# haasoscope_pro_fpga_board_-_v1_0.net
KiCad netlist of a schematic drawn in EAGLE
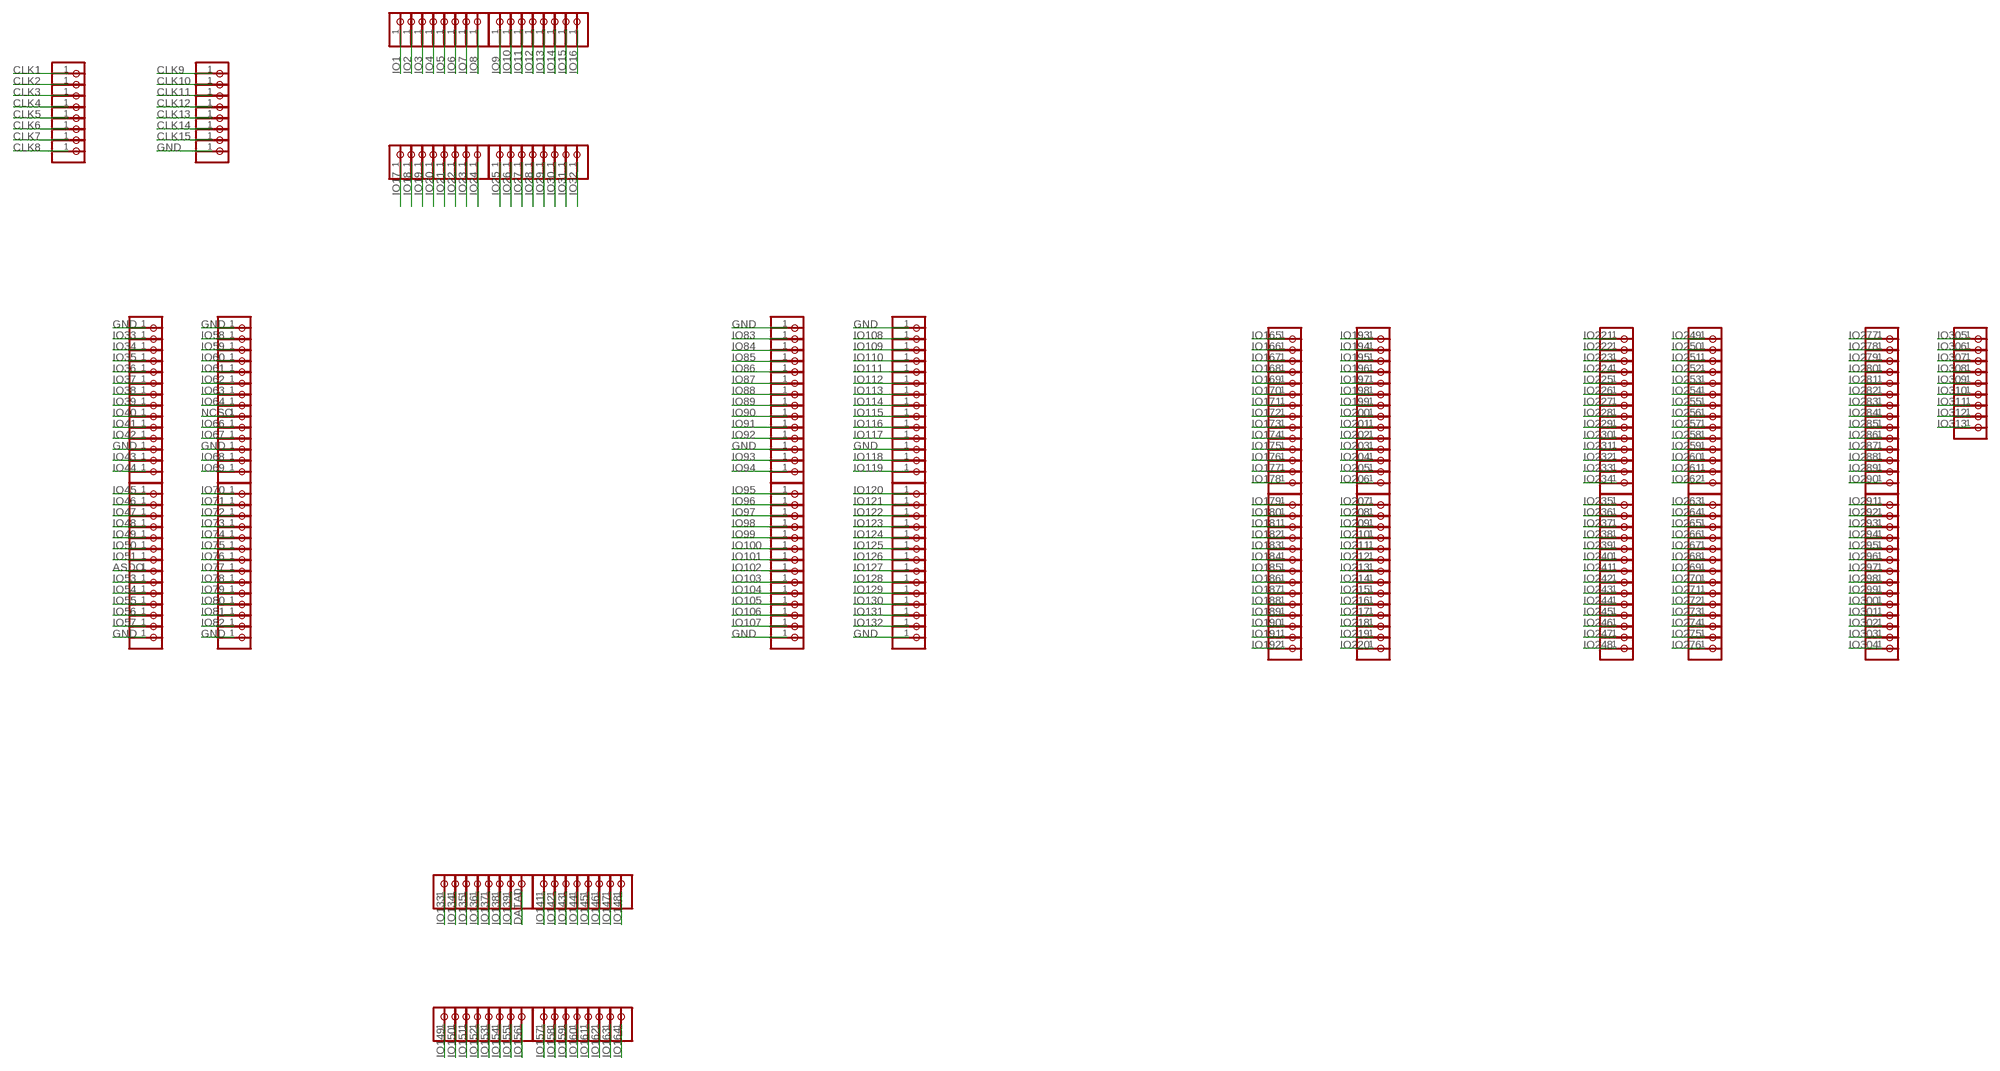
[diagram p0: schematic, sheet 1]
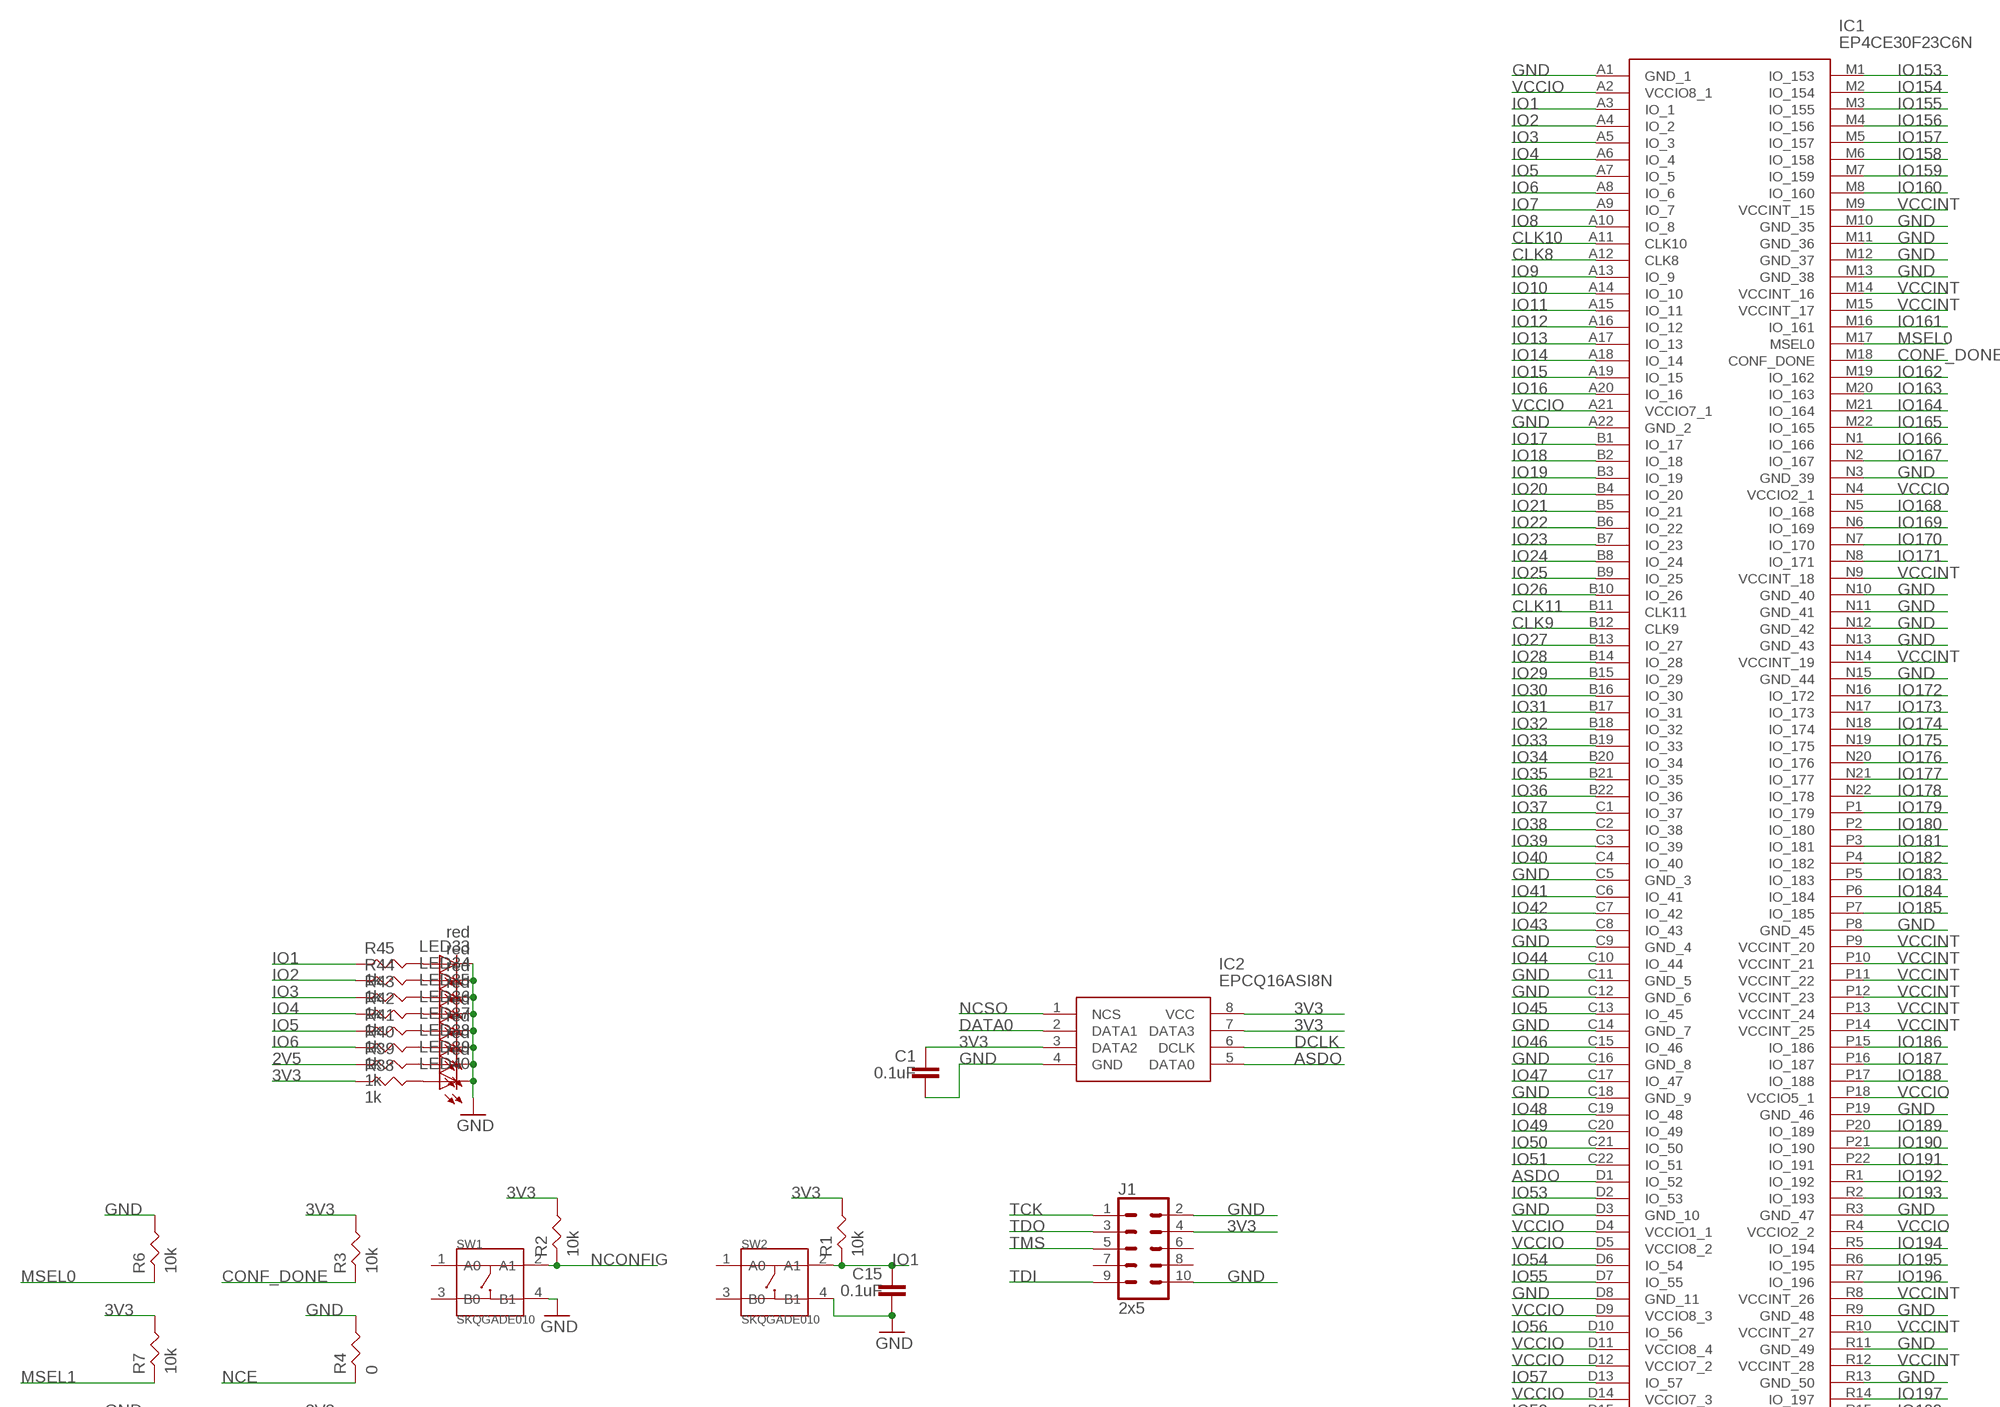
[diagram p1: schematic, sheet 2, part 1 of 2]
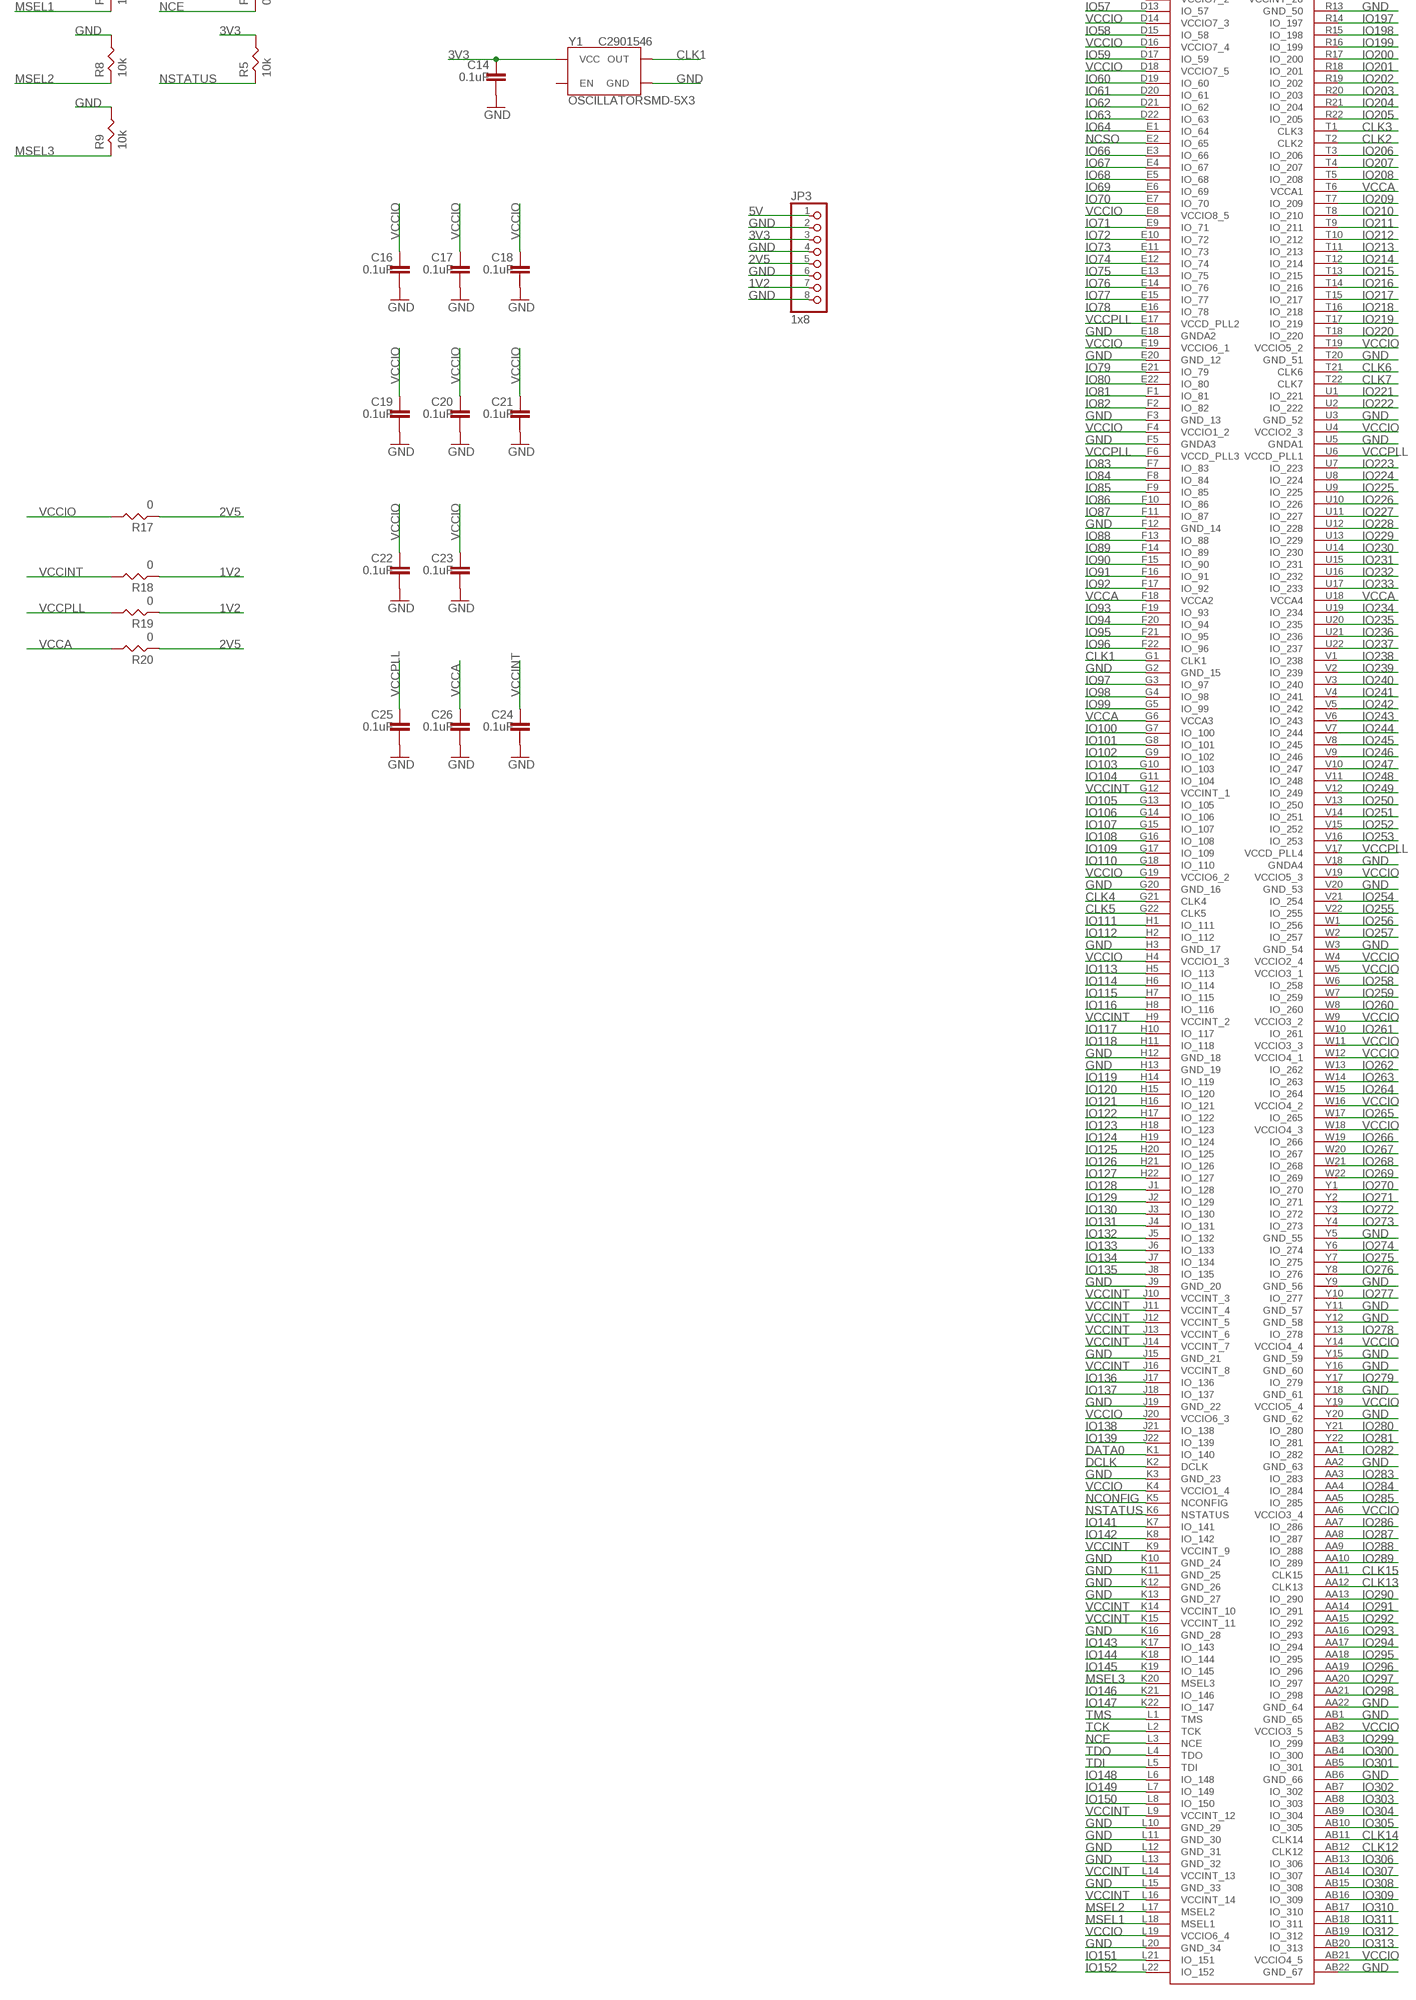
[diagram p2: schematic, sheet 2, part 2 of 2]
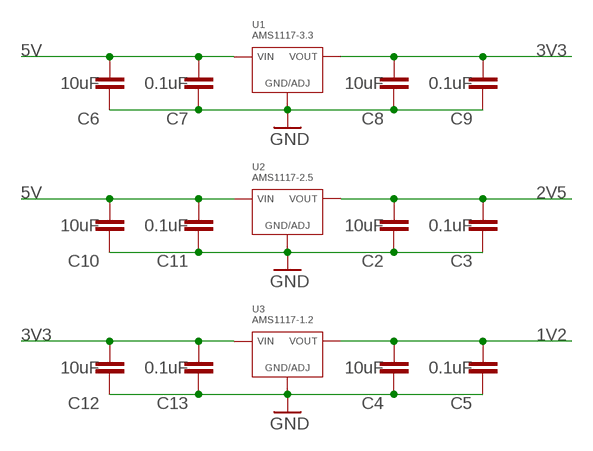
[diagram p3: schematic, sheet 3]

(export (version "E")
  (design (tool "Eeschema 10.0.6"))
  (components
    (comp (ref "JP1")
      (value "1")
      (footprint "eagle-import:1X01")
      (libsource (lib "eagle-import") (part "PINHD-1X1"))
    )
    (comp (ref "JP2")
      (value "1")
      (footprint "eagle-import:1X01")
      (libsource (lib "eagle-import") (part "PINHD-1X1"))
    )
    (comp (ref "JP4")
      (value "1")
      (footprint "eagle-import:1X01")
      (libsource (lib "eagle-import") (part "PINHD-1X1"))
    )
    (comp (ref "JP5")
      (value "1")
      (footprint "eagle-import:1X01")
      (libsource (lib "eagle-import") (part "PINHD-1X1"))
    )
    (comp (ref "JP6")
      (value "1")
      (footprint "eagle-import:1X01")
      (libsource (lib "eagle-import") (part "PINHD-1X1"))
    )
    (comp (ref "JP7")
      (value "1")
      (footprint "eagle-import:1X01")
      (libsource (lib "eagle-import") (part "PINHD-1X1"))
    )
    (comp (ref "JP8")
      (value "1")
      (footprint "eagle-import:1X01")
      (libsource (lib "eagle-import") (part "PINHD-1X1"))
    )
    (comp (ref "JP9")
      (value "1")
      (footprint "eagle-import:1X01")
      (libsource (lib "eagle-import") (part "PINHD-1X1"))
    )
    (comp (ref "JP10")
      (value "1")
      (footprint "eagle-import:1X01")
      (libsource (lib "eagle-import") (part "PINHD-1X1"))
    )
    (comp (ref "JP11")
      (value "1")
      (footprint "eagle-import:1X01")
      (libsource (lib "eagle-import") (part "PINHD-1X1"))
    )
    (comp (ref "JP12")
      (value "1")
      (footprint "eagle-import:1X01")
      (libsource (lib "eagle-import") (part "PINHD-1X1"))
    )
    (comp (ref "JP13")
      (value "1")
      (footprint "eagle-import:1X01")
      (libsource (lib "eagle-import") (part "PINHD-1X1"))
    )
    (comp (ref "JP14")
      (value "1")
      (footprint "eagle-import:1X01")
      (libsource (lib "eagle-import") (part "PINHD-1X1"))
    )
    (comp (ref "JP15")
      (value "1")
      (footprint "eagle-import:1X01")
      (libsource (lib "eagle-import") (part "PINHD-1X1"))
    )
    (comp (ref "JP16")
      (value "1")
      (footprint "eagle-import:1X01")
      (libsource (lib "eagle-import") (part "PINHD-1X1"))
    )
    (comp (ref "JP17")
      (value "1")
      (footprint "eagle-import:1X01")
      (libsource (lib "eagle-import") (part "PINHD-1X1"))
    )
    (comp (ref "JP18")
      (value "1")
      (footprint "eagle-import:1X01")
      (libsource (lib "eagle-import") (part "PINHD-1X1"))
    )
    (comp (ref "JP19")
      (value "1")
      (footprint "eagle-import:1X01")
      (libsource (lib "eagle-import") (part "PINHD-1X1"))
    )
    (comp (ref "JP20")
      (value "1")
      (footprint "eagle-import:1X01")
      (libsource (lib "eagle-import") (part "PINHD-1X1"))
    )
    (comp (ref "JP21")
      (value "1")
      (footprint "eagle-import:1X01")
      (libsource (lib "eagle-import") (part "PINHD-1X1"))
    )
    (comp (ref "JP22")
      (value "1")
      (footprint "eagle-import:1X01")
      (libsource (lib "eagle-import") (part "PINHD-1X1"))
    )
    (comp (ref "JP23")
      (value "1")
      (footprint "eagle-import:1X01")
      (libsource (lib "eagle-import") (part "PINHD-1X1"))
    )
    (comp (ref "JP24")
      (value "1")
      (footprint "eagle-import:1X01")
      (libsource (lib "eagle-import") (part "PINHD-1X1"))
    )
    (comp (ref "JP25")
      (value "1")
      (footprint "eagle-import:1X01")
      (libsource (lib "eagle-import") (part "PINHD-1X1"))
    )
    (comp (ref "JP26")
      (value "1")
      (footprint "eagle-import:1X01")
      (libsource (lib "eagle-import") (part "PINHD-1X1"))
    )
    (comp (ref "JP27")
      (value "1")
      (footprint "eagle-import:1X01")
      (libsource (lib "eagle-import") (part "PINHD-1X1"))
    )
    (comp (ref "JP28")
      (value "1")
      (footprint "eagle-import:1X01")
      (libsource (lib "eagle-import") (part "PINHD-1X1"))
    )
    (comp (ref "JP29")
      (value "1")
      (footprint "eagle-import:1X01")
      (libsource (lib "eagle-import") (part "PINHD-1X1"))
    )
    (comp (ref "JP30")
      (value "1")
      (footprint "eagle-import:1X01")
      (libsource (lib "eagle-import") (part "PINHD-1X1"))
    )
    (comp (ref "JP31")
      (value "1")
      (footprint "eagle-import:1X01")
      (libsource (lib "eagle-import") (part "PINHD-1X1"))
    )
    (comp (ref "JP32")
      (value "1")
      (footprint "eagle-import:1X01")
      (libsource (lib "eagle-import") (part "PINHD-1X1"))
    )
    (comp (ref "JP33")
      (value "1")
      (footprint "eagle-import:1X01")
      (libsource (lib "eagle-import") (part "PINHD-1X1"))
    )
    (comp (ref "JP34")
      (value "1")
      (footprint "eagle-import:1X01")
      (libsource (lib "eagle-import") (part "PINHD-1X1"))
    )
    (comp (ref "JP35")
      (value "1")
      (footprint "eagle-import:1X01")
      (libsource (lib "eagle-import") (part "PINHD-1X1"))
    )
    (comp (ref "JP36")
      (value "1")
      (footprint "eagle-import:1X01")
      (libsource (lib "eagle-import") (part "PINHD-1X1"))
    )
    (comp (ref "JP37")
      (value "1")
      (footprint "eagle-import:1X01")
      (libsource (lib "eagle-import") (part "PINHD-1X1"))
    )
    (comp (ref "JP38")
      (value "1")
      (footprint "eagle-import:1X01")
      (libsource (lib "eagle-import") (part "PINHD-1X1"))
    )
    (comp (ref "JP39")
      (value "1")
      (footprint "eagle-import:1X01")
      (libsource (lib "eagle-import") (part "PINHD-1X1"))
    )
    (comp (ref "JP40")
      (value "1")
      (footprint "eagle-import:1X01")
      (libsource (lib "eagle-import") (part "PINHD-1X1"))
    )
    (comp (ref "JP41")
      (value "1")
      (footprint "eagle-import:1X01")
      (libsource (lib "eagle-import") (part "PINHD-1X1"))
    )
    (comp (ref "JP42")
      (value "1")
      (footprint "eagle-import:1X01")
      (libsource (lib "eagle-import") (part "PINHD-1X1"))
    )
    (comp (ref "JP43")
      (value "1")
      (footprint "eagle-import:1X01")
      (libsource (lib "eagle-import") (part "PINHD-1X1"))
    )
    (comp (ref "JP44")
      (value "1")
      (footprint "eagle-import:1X01")
      (libsource (lib "eagle-import") (part "PINHD-1X1"))
    )
    (comp (ref "JP45")
      (value "1")
      (footprint "eagle-import:1X01")
      (libsource (lib "eagle-import") (part "PINHD-1X1"))
    )
    (comp (ref "JP46")
      (value "1")
      (footprint "eagle-import:1X01")
      (libsource (lib "eagle-import") (part "PINHD-1X1"))
    )
    (comp (ref "JP47")
      (value "1")
      (footprint "eagle-import:1X01")
      (libsource (lib "eagle-import") (part "PINHD-1X1"))
    )
    (comp (ref "JP48")
      (value "1")
      (footprint "eagle-import:1X01")
      (libsource (lib "eagle-import") (part "PINHD-1X1"))
    )
    (comp (ref "JP49")
      (value "1")
      (footprint "eagle-import:1X01")
      (libsource (lib "eagle-import") (part "PINHD-1X1"))
    )
    (comp (ref "JP50")
      (value "1")
      (footprint "eagle-import:1X01")
      (libsource (lib "eagle-import") (part "PINHD-1X1"))
    )
    (comp (ref "JP51")
      (value "1")
      (footprint "eagle-import:1X01")
      (libsource (lib "eagle-import") (part "PINHD-1X1"))
    )
    (comp (ref "JP52")
      (value "1")
      (footprint "eagle-import:1X01")
      (libsource (lib "eagle-import") (part "PINHD-1X1"))
    )
    (comp (ref "JP53")
      (value "1")
      (footprint "eagle-import:1X01")
      (libsource (lib "eagle-import") (part "PINHD-1X1"))
    )
    (comp (ref "JP54")
      (value "1")
      (footprint "eagle-import:1X01")
      (libsource (lib "eagle-import") (part "PINHD-1X1"))
    )
    (comp (ref "JP55")
      (value "1")
      (footprint "eagle-import:1X01")
      (libsource (lib "eagle-import") (part "PINHD-1X1"))
    )
    (comp (ref "JP56")
      (value "1")
      (footprint "eagle-import:1X01")
      (libsource (lib "eagle-import") (part "PINHD-1X1"))
    )
    (comp (ref "JP57")
      (value "1")
      (footprint "eagle-import:1X01")
      (libsource (lib "eagle-import") (part "PINHD-1X1"))
    )
    (comp (ref "JP58")
      (value "1")
      (footprint "eagle-import:1X01")
      (libsource (lib "eagle-import") (part "PINHD-1X1"))
    )
    (comp (ref "JP59")
      (value "1")
      (footprint "eagle-import:1X01")
      (libsource (lib "eagle-import") (part "PINHD-1X1"))
    )
    (comp (ref "JP60")
      (value "1")
      (footprint "eagle-import:1X01")
      (libsource (lib "eagle-import") (part "PINHD-1X1"))
    )
    (comp (ref "JP61")
      (value "1")
      (footprint "eagle-import:1X01")
      (libsource (lib "eagle-import") (part "PINHD-1X1"))
    )
    (comp (ref "JP62")
      (value "1")
      (footprint "eagle-import:1X01")
      (libsource (lib "eagle-import") (part "PINHD-1X1"))
    )
    (comp (ref "JP63")
      (value "1")
      (footprint "eagle-import:1X01")
      (libsource (lib "eagle-import") (part "PINHD-1X1"))
    )
    (comp (ref "JP64")
      (value "1")
      (footprint "eagle-import:1X01")
      (libsource (lib "eagle-import") (part "PINHD-1X1"))
    )
    (comp (ref "JP65")
      (value "1")
      (footprint "eagle-import:1X01")
      (libsource (lib "eagle-import") (part "PINHD-1X1"))
    )
    (comp (ref "JP66")
      (value "1")
      (footprint "eagle-import:1X01")
      (libsource (lib "eagle-import") (part "PINHD-1X1"))
    )
    (comp (ref "JP67")
      (value "1")
      (footprint "eagle-import:1X01")
      (libsource (lib "eagle-import") (part "PINHD-1X1"))
    )
    (comp (ref "JP68")
      (value "1")
      (footprint "eagle-import:1X01")
      (libsource (lib "eagle-import") (part "PINHD-1X1"))
    )
    (comp (ref "JP69")
      (value "1")
      (footprint "eagle-import:1X01")
      (libsource (lib "eagle-import") (part "PINHD-1X1"))
    )
    (comp (ref "JP70")
      (value "1")
      (footprint "eagle-import:1X01")
      (libsource (lib "eagle-import") (part "PINHD-1X1"))
    )
    (comp (ref "JP71")
      (value "1")
      (footprint "eagle-import:1X01")
      (libsource (lib "eagle-import") (part "PINHD-1X1"))
    )
    (comp (ref "JP72")
      (value "1")
      (footprint "eagle-import:1X01")
      (libsource (lib "eagle-import") (part "PINHD-1X1"))
    )
    (comp (ref "JP73")
      (value "1")
      (footprint "eagle-import:1X01")
      (libsource (lib "eagle-import") (part "PINHD-1X1"))
    )
    (comp (ref "JP74")
      (value "1")
      (footprint "eagle-import:1X01")
      (libsource (lib "eagle-import") (part "PINHD-1X1"))
    )
    (comp (ref "JP75")
      (value "1")
      (footprint "eagle-import:1X01")
      (libsource (lib "eagle-import") (part "PINHD-1X1"))
    )
    (comp (ref "JP76")
      (value "1")
      (footprint "eagle-import:1X01")
      (libsource (lib "eagle-import") (part "PINHD-1X1"))
    )
    (comp (ref "JP77")
      (value "1")
      (footprint "eagle-import:1X01")
      (libsource (lib "eagle-import") (part "PINHD-1X1"))
    )
    (comp (ref "JP78")
      (value "1")
      (footprint "eagle-import:1X01")
      (libsource (lib "eagle-import") (part "PINHD-1X1"))
    )
    (comp (ref "JP79")
      (value "1")
      (footprint "eagle-import:1X01")
      (libsource (lib "eagle-import") (part "PINHD-1X1"))
    )
    (comp (ref "JP80")
      (value "1")
      (footprint "eagle-import:1X01")
      (libsource (lib "eagle-import") (part "PINHD-1X1"))
    )
    (comp (ref "JP81")
      (value "1")
      (footprint "eagle-import:1X01")
      (libsource (lib "eagle-import") (part "PINHD-1X1"))
    )
    (comp (ref "JP82")
      (value "1")
      (footprint "eagle-import:1X01")
      (libsource (lib "eagle-import") (part "PINHD-1X1"))
    )
    (comp (ref "JP83")
      (value "1")
      (footprint "eagle-import:1X01")
      (libsource (lib "eagle-import") (part "PINHD-1X1"))
    )
    (comp (ref "JP84")
      (value "1")
      (footprint "eagle-import:1X01")
      (libsource (lib "eagle-import") (part "PINHD-1X1"))
    )
    (comp (ref "JP85")
      (value "1")
      (footprint "eagle-import:1X01")
      (libsource (lib "eagle-import") (part "PINHD-1X1"))
    )
    (comp (ref "JP86")
      (value "1")
      (footprint "eagle-import:1X01")
      (libsource (lib "eagle-import") (part "PINHD-1X1"))
    )
    (comp (ref "JP87")
      (value "1")
      (footprint "eagle-import:1X01")
      (libsource (lib "eagle-import") (part "PINHD-1X1"))
    )
    (comp (ref "JP88")
      (value "1")
      (footprint "eagle-import:1X01")
      (libsource (lib "eagle-import") (part "PINHD-1X1"))
    )
    (comp (ref "JP89")
      (value "1")
      (footprint "eagle-import:1X01")
      (libsource (lib "eagle-import") (part "PINHD-1X1"))
    )
    (comp (ref "JP90")
      (value "1")
      (footprint "eagle-import:1X01")
      (libsource (lib "eagle-import") (part "PINHD-1X1"))
    )
    (comp (ref "JP91")
      (value "1")
      (footprint "eagle-import:1X01")
      (libsource (lib "eagle-import") (part "PINHD-1X1"))
    )
    (comp (ref "JP92")
      (value "1")
      (footprint "eagle-import:1X01")
      (libsource (lib "eagle-import") (part "PINHD-1X1"))
    )
    (comp (ref "JP93")
      (value "1")
      (footprint "eagle-import:1X01")
      (libsource (lib "eagle-import") (part "PINHD-1X1"))
    )
    (comp (ref "JP94")
      (value "1")
      (footprint "eagle-import:1X01")
      (libsource (lib "eagle-import") (part "PINHD-1X1"))
    )
    (comp (ref "JP95")
      (value "1")
      (footprint "eagle-import:1X01")
      (libsource (lib "eagle-import") (part "PINHD-1X1"))
    )
    (comp (ref "JP96")
      (value "1")
      (footprint "eagle-import:1X01")
      (libsource (lib "eagle-import") (part "PINHD-1X1"))
    )
    (comp (ref "JP97")
      (value "1")
      (footprint "eagle-import:1X01")
      (libsource (lib "eagle-import") (part "PINHD-1X1"))
    )
    (comp (ref "JP98")
      (value "1")
      (footprint "eagle-import:1X01")
      (libsource (lib "eagle-import") (part "PINHD-1X1"))
    )
    (comp (ref "JP99")
      (value "1")
      (footprint "eagle-import:1X01")
      (libsource (lib "eagle-import") (part "PINHD-1X1"))
    )
    (comp (ref "JP100")
      (value "1")
      (footprint "eagle-import:1X01")
      (libsource (lib "eagle-import") (part "PINHD-1X1"))
    )
    (comp (ref "JP101")
      (value "1")
      (footprint "eagle-import:1X01")
      (libsource (lib "eagle-import") (part "PINHD-1X1"))
    )
    (comp (ref "JP102")
      (value "1")
      (footprint "eagle-import:1X01")
      (libsource (lib "eagle-import") (part "PINHD-1X1"))
    )
    (comp (ref "JP103")
      (value "1")
      (footprint "eagle-import:1X01")
      (libsource (lib "eagle-import") (part "PINHD-1X1"))
    )
    (comp (ref "JP104")
      (value "1")
      (footprint "eagle-import:1X01")
      (libsource (lib "eagle-import") (part "PINHD-1X1"))
    )
    (comp (ref "JP105")
      (value "1")
      (footprint "eagle-import:1X01")
      (libsource (lib "eagle-import") (part "PINHD-1X1"))
    )
    (comp (ref "JP106")
      (value "1")
      (footprint "eagle-import:1X01")
      (libsource (lib "eagle-import") (part "PINHD-1X1"))
    )
    (comp (ref "JP107")
      (value "1")
      (footprint "eagle-import:1X01")
      (libsource (lib "eagle-import") (part "PINHD-1X1"))
    )
    (comp (ref "JP108")
      (value "1")
      (footprint "eagle-import:1X01")
      (libsource (lib "eagle-import") (part "PINHD-1X1"))
    )
    (comp (ref "JP109")
      (value "1")
      (footprint "eagle-import:1X01")
      (libsource (lib "eagle-import") (part "PINHD-1X1"))
    )
    (comp (ref "JP110")
      (value "1")
      (footprint "eagle-import:1X01")
      (libsource (lib "eagle-import") (part "PINHD-1X1"))
    )
    (comp (ref "JP111")
      (value "1")
      (footprint "eagle-import:1X01")
      (libsource (lib "eagle-import") (part "PINHD-1X1"))
    )
    (comp (ref "JP112")
      (value "1")
      (footprint "eagle-import:1X01")
      (libsource (lib "eagle-import") (part "PINHD-1X1"))
    )
    (comp (ref "JP113")
      (value "1")
      (footprint "eagle-import:1X01")
      (libsource (lib "eagle-import") (part "PINHD-1X1"))
    )
    (comp (ref "JP114")
      (value "1")
      (footprint "eagle-import:1X01")
      (libsource (lib "eagle-import") (part "PINHD-1X1"))
    )
    (comp (ref "JP115")
      (value "1")
      (footprint "eagle-import:1X01")
      (libsource (lib "eagle-import") (part "PINHD-1X1"))
    )
    (comp (ref "JP116")
      (value "1")
      (footprint "eagle-import:1X01")
      (libsource (lib "eagle-import") (part "PINHD-1X1"))
    )
    (comp (ref "JP117")
      (value "1")
      (footprint "eagle-import:1X01")
      (libsource (lib "eagle-import") (part "PINHD-1X1"))
    )
    (comp (ref "JP118")
      (value "1")
      (footprint "eagle-import:1X01")
      (libsource (lib "eagle-import") (part "PINHD-1X1"))
    )
    (comp (ref "JP119")
      (value "1")
      (footprint "eagle-import:1X01")
      (libsource (lib "eagle-import") (part "PINHD-1X1"))
    )
    (comp (ref "JP120")
      (value "1")
      (footprint "eagle-import:1X01")
      (libsource (lib "eagle-import") (part "PINHD-1X1"))
    )
    (comp (ref "JP121")
      (value "1")
      (footprint "eagle-import:1X01")
      (libsource (lib "eagle-import") (part "PINHD-1X1"))
    )
    (comp (ref "JP122")
      (value "1")
      (footprint "eagle-import:1X01")
      (libsource (lib "eagle-import") (part "PINHD-1X1"))
    )
    (comp (ref "JP123")
      (value "1")
      (footprint "eagle-import:1X01")
      (libsource (lib "eagle-import") (part "PINHD-1X1"))
    )
    (comp (ref "JP124")
      (value "1")
      (footprint "eagle-import:1X01")
      (libsource (lib "eagle-import") (part "PINHD-1X1"))
    )
    (comp (ref "JP125")
      (value "1")
      (footprint "eagle-import:1X01")
      (libsource (lib "eagle-import") (part "PINHD-1X1"))
    )
    (comp (ref "JP126")
      (value "1")
      (footprint "eagle-import:1X01")
      (libsource (lib "eagle-import") (part "PINHD-1X1"))
    )
    (comp (ref "JP127")
      (value "1")
      (footprint "eagle-import:1X01")
      (libsource (lib "eagle-import") (part "PINHD-1X1"))
    )
    (comp (ref "JP128")
      (value "1")
      (footprint "eagle-import:1X01")
      (libsource (lib "eagle-import") (part "PINHD-1X1"))
    )
    (comp (ref "JP129")
      (value "1")
      (footprint "eagle-import:1X01")
      (libsource (lib "eagle-import") (part "PINHD-1X1"))
    )
    (comp (ref "JP130")
      (value "1")
      (footprint "eagle-import:1X01")
      (libsource (lib "eagle-import") (part "PINHD-1X1"))
    )
    (comp (ref "JP131")
      (value "1")
      (footprint "eagle-import:1X01")
      (libsource (lib "eagle-import") (part "PINHD-1X1"))
    )
    (comp (ref "JP132")
      (value "1")
      (footprint "eagle-import:1X01")
      (libsource (lib "eagle-import") (part "PINHD-1X1"))
    )
    (comp (ref "JP133")
      (value "1")
      (footprint "eagle-import:1X01")
      (libsource (lib "eagle-import") (part "PINHD-1X1"))
    )
    (comp (ref "JP134")
      (value "1")
      (footprint "eagle-import:1X01")
      (libsource (lib "eagle-import") (part "PINHD-1X1"))
    )
    (comp (ref "JP135")
      (value "1")
      (footprint "eagle-import:1X01")
      (libsource (lib "eagle-import") (part "PINHD-1X1"))
    )
    (comp (ref "JP136")
      (value "1")
      (footprint "eagle-import:1X01")
      (libsource (lib "eagle-import") (part "PINHD-1X1"))
    )
    (comp (ref "JP137")
      (value "1")
      (footprint "eagle-import:1X01")
      (libsource (lib "eagle-import") (part "PINHD-1X1"))
    )
    (comp (ref "JP138")
      (value "1")
      (footprint "eagle-import:1X01")
      (libsource (lib "eagle-import") (part "PINHD-1X1"))
    )
    (comp (ref "JP139")
      (value "1")
      (footprint "eagle-import:1X01")
      (libsource (lib "eagle-import") (part "PINHD-1X1"))
    )
    (comp (ref "JP140")
      (value "1")
      (footprint "eagle-import:1X01")
      (libsource (lib "eagle-import") (part "PINHD-1X1"))
    )
    (comp (ref "JP141")
      (value "1")
      (footprint "eagle-import:1X01")
      (libsource (lib "eagle-import") (part "PINHD-1X1"))
    )
    (comp (ref "JP142")
      (value "1")
      (footprint "eagle-import:1X01")
      (libsource (lib "eagle-import") (part "PINHD-1X1"))
    )
    (comp (ref "JP143")
      (value "1")
      (footprint "eagle-import:1X01")
      (libsource (lib "eagle-import") (part "PINHD-1X1"))
    )
    (comp (ref "JP144")
      (value "1")
      (footprint "eagle-import:1X01")
      (libsource (lib "eagle-import") (part "PINHD-1X1"))
    )
    (comp (ref "JP145")
      (value "1")
      (footprint "eagle-import:1X01")
      (libsource (lib "eagle-import") (part "PINHD-1X1"))
    )
    (comp (ref "JP146")
      (value "1")
      (footprint "eagle-import:1X01")
      (libsource (lib "eagle-import") (part "PINHD-1X1"))
    )
    (comp (ref "JP147")
      (value "1")
      (footprint "eagle-import:1X01")
      (libsource (lib "eagle-import") (part "PINHD-1X1"))
    )
    (comp (ref "JP148")
      (value "1")
      (footprint "eagle-import:1X01")
      (libsource (lib "eagle-import") (part "PINHD-1X1"))
    )
    (comp (ref "JP149")
      (value "1")
      (footprint "eagle-import:1X01")
      (libsource (lib "eagle-import") (part "PINHD-1X1"))
    )
    (comp (ref "JP150")
      (value "1")
      (footprint "eagle-import:1X01")
      (libsource (lib "eagle-import") (part "PINHD-1X1"))
    )
    (comp (ref "JP151")
      (value "1")
      (footprint "eagle-import:1X01")
      (libsource (lib "eagle-import") (part "PINHD-1X1"))
    )
    (comp (ref "JP152")
      (value "1")
      (footprint "eagle-import:1X01")
      (libsource (lib "eagle-import") (part "PINHD-1X1"))
    )
    (comp (ref "JP153")
      (value "1")
      (footprint "eagle-import:1X01")
      (libsource (lib "eagle-import") (part "PINHD-1X1"))
    )
    (comp (ref "JP154")
      (value "1")
      (footprint "eagle-import:1X01")
      (libsource (lib "eagle-import") (part "PINHD-1X1"))
    )
    (comp (ref "JP155")
      (value "1")
      (footprint "eagle-import:1X01")
      (libsource (lib "eagle-import") (part "PINHD-1X1"))
    )
    (comp (ref "JP156")
      (value "1")
      (footprint "eagle-import:1X01")
      (libsource (lib "eagle-import") (part "PINHD-1X1"))
    )
    (comp (ref "JP157")
      (value "1")
      (footprint "eagle-import:1X01")
      (libsource (lib "eagle-import") (part "PINHD-1X1"))
    )
    (comp (ref "JP158")
      (value "1")
      (footprint "eagle-import:1X01")
      (libsource (lib "eagle-import") (part "PINHD-1X1"))
    )
    (comp (ref "JP159")
      (value "1")
      (footprint "eagle-import:1X01")
      (libsource (lib "eagle-import") (part "PINHD-1X1"))
    )
    (comp (ref "JP160")
      (value "1")
      (footprint "eagle-import:1X01")
      (libsource (lib "eagle-import") (part "PINHD-1X1"))
    )
    (comp (ref "JP161")
      (value "1")
      (footprint "eagle-import:1X01")
      (libsource (lib "eagle-import") (part "PINHD-1X1"))
    )
    (comp (ref "JP162")
      (value "1")
      (footprint "eagle-import:1X01")
      (libsource (lib "eagle-import") (part "PINHD-1X1"))
    )
    (comp (ref "JP163")
      (value "1")
      (footprint "eagle-import:1X01")
      (libsource (lib "eagle-import") (part "PINHD-1X1"))
    )
    (comp (ref "JP164")
      (value "1")
      (footprint "eagle-import:1X01")
      (libsource (lib "eagle-import") (part "PINHD-1X1"))
    )
    (comp (ref "JP165")
      (value "1")
      (footprint "eagle-import:1X01")
      (libsource (lib "eagle-import") (part "PINHD-1X1"))
    )
    (comp (ref "JP166")
      (value "1")
      (footprint "eagle-import:1X01")
      (libsource (lib "eagle-import") (part "PINHD-1X1"))
    )
    (comp (ref "JP167")
      (value "1")
      (footprint "eagle-import:1X01")
      (libsource (lib "eagle-import") (part "PINHD-1X1"))
    )
    (comp (ref "JP168")
      (value "1")
      (footprint "eagle-import:1X01")
      (libsource (lib "eagle-import") (part "PINHD-1X1"))
    )
    (comp (ref "JP169")
      (value "1")
      (footprint "eagle-import:1X01")
      (libsource (lib "eagle-import") (part "PINHD-1X1"))
    )
    (comp (ref "JP170")
      (value "1")
      (footprint "eagle-import:1X01")
      (libsource (lib "eagle-import") (part "PINHD-1X1"))
    )
    (comp (ref "JP171")
      (value "1")
      (footprint "eagle-import:1X01")
      (libsource (lib "eagle-import") (part "PINHD-1X1"))
    )
    (comp (ref "JP172")
      (value "1")
      (footprint "eagle-import:1X01")
      (libsource (lib "eagle-import") (part "PINHD-1X1"))
    )
    (comp (ref "JP173")
      (value "1")
      (footprint "eagle-import:1X01")
      (libsource (lib "eagle-import") (part "PINHD-1X1"))
    )
    (comp (ref "JP174")
      (value "1")
      (footprint "eagle-import:1X01")
      (libsource (lib "eagle-import") (part "PINHD-1X1"))
    )
    (comp (ref "JP175")
      (value "1")
      (footprint "eagle-import:1X01")
      (libsource (lib "eagle-import") (part "PINHD-1X1"))
    )
    (comp (ref "JP176")
      (value "1")
      (footprint "eagle-import:1X01")
      (libsource (lib "eagle-import") (part "PINHD-1X1"))
    )
    (comp (ref "JP177")
      (value "1")
      (footprint "eagle-import:1X01")
      (libsource (lib "eagle-import") (part "PINHD-1X1"))
    )
    (comp (ref "JP178")
      (value "1")
      (footprint "eagle-import:1X01")
      (libsource (lib "eagle-import") (part "PINHD-1X1"))
    )
    (comp (ref "JP179")
      (value "1")
      (footprint "eagle-import:1X01")
      (libsource (lib "eagle-import") (part "PINHD-1X1"))
    )
    (comp (ref "JP180")
      (value "1")
      (footprint "eagle-import:1X01")
      (libsource (lib "eagle-import") (part "PINHD-1X1"))
    )
    (comp (ref "JP181")
      (value "1")
      (footprint "eagle-import:1X01")
      (libsource (lib "eagle-import") (part "PINHD-1X1"))
    )
    (comp (ref "JP182")
      (value "1")
      (footprint "eagle-import:1X01")
      (libsource (lib "eagle-import") (part "PINHD-1X1"))
    )
    (comp (ref "JP183")
      (value "1")
      (footprint "eagle-import:1X01")
      (libsource (lib "eagle-import") (part "PINHD-1X1"))
    )
    (comp (ref "JP184")
      (value "1")
      (footprint "eagle-import:1X01")
      (libsource (lib "eagle-import") (part "PINHD-1X1"))
    )
    (comp (ref "JP185")
      (value "1")
      (footprint "eagle-import:1X01")
      (libsource (lib "eagle-import") (part "PINHD-1X1"))
    )
    (comp (ref "JP186")
      (value "1")
      (footprint "eagle-import:1X01")
      (libsource (lib "eagle-import") (part "PINHD-1X1"))
    )
    (comp (ref "JP187")
      (value "1")
      (footprint "eagle-import:1X01")
      (libsource (lib "eagle-import") (part "PINHD-1X1"))
    )
    (comp (ref "JP188")
      (value "1")
      (footprint "eagle-import:1X01")
      (libsource (lib "eagle-import") (part "PINHD-1X1"))
    )
    (comp (ref "JP189")
      (value "1")
      (footprint "eagle-import:1X01")
      (libsource (lib "eagle-import") (part "PINHD-1X1"))
    )
    (comp (ref "JP190")
      (value "1")
      (footprint "eagle-import:1X01")
      (libsource (lib "eagle-import") (part "PINHD-1X1"))
    )
    (comp (ref "JP191")
      (value "1")
      (footprint "eagle-import:1X01")
      (libsource (lib "eagle-import") (part "PINHD-1X1"))
    )
    (comp (ref "JP192")
      (value "1")
      (footprint "eagle-import:1X01")
      (libsource (lib "eagle-import") (part "PINHD-1X1"))
    )
    (comp (ref "JP193")
      (value "1")
      (footprint "eagle-import:1X01")
      (libsource (lib "eagle-import") (part "PINHD-1X1"))
    )
    (comp (ref "JP194")
      (value "1")
      (footprint "eagle-import:1X01")
      (libsource (lib "eagle-import") (part "PINHD-1X1"))
    )
    (comp (ref "JP195")
      (value "1")
      (footprint "eagle-import:1X01")
      (libsource (lib "eagle-import") (part "PINHD-1X1"))
    )
    (comp (ref "JP196")
      (value "1")
      (footprint "eagle-import:1X01")
      (libsource (lib "eagle-import") (part "PINHD-1X1"))
    )
    (comp (ref "JP197")
      (value "1")
      (footprint "eagle-import:1X01")
      (libsource (lib "eagle-import") (part "PINHD-1X1"))
    )
    (comp (ref "JP198")
      (value "1")
      (footprint "eagle-import:1X01")
      (libsource (lib "eagle-import") (part "PINHD-1X1"))
    )
    (comp (ref "JP199")
      (value "1")
      (footprint "eagle-import:1X01")
      (libsource (lib "eagle-import") (part "PINHD-1X1"))
    )
    (comp (ref "JP200")
      (value "1")
      (footprint "eagle-import:1X01")
      (libsource (lib "eagle-import") (part "PINHD-1X1"))
    )
    (comp (ref "JP201")
      (value "1")
      (footprint "eagle-import:1X01")
      (libsource (lib "eagle-import") (part "PINHD-1X1"))
    )
    (comp (ref "JP202")
      (value "1")
      (footprint "eagle-import:1X01")
      (libsource (lib "eagle-import") (part "PINHD-1X1"))
    )
    (comp (ref "JP203")
      (value "1")
      (footprint "eagle-import:1X01")
      (libsource (lib "eagle-import") (part "PINHD-1X1"))
    )
    (comp (ref "JP204")
      (value "1")
      (footprint "eagle-import:1X01")
      (libsource (lib "eagle-import") (part "PINHD-1X1"))
    )
    (comp (ref "JP205")
      (value "1")
      (footprint "eagle-import:1X01")
      (libsource (lib "eagle-import") (part "PINHD-1X1"))
    )
    (comp (ref "JP206")
      (value "1")
      (footprint "eagle-import:1X01")
      (libsource (lib "eagle-import") (part "PINHD-1X1"))
    )
    (comp (ref "JP207")
      (value "1")
      (footprint "eagle-import:1X01")
      (libsource (lib "eagle-import") (part "PINHD-1X1"))
    )
    (comp (ref "JP208")
      (value "1")
      (footprint "eagle-import:1X01")
      (libsource (lib "eagle-import") (part "PINHD-1X1"))
    )
    (comp (ref "JP209")
      (value "1")
      (footprint "eagle-import:1X01")
      (libsource (lib "eagle-import") (part "PINHD-1X1"))
    )
    (comp (ref "JP210")
      (value "1")
      (footprint "eagle-import:1X01")
      (libsource (lib "eagle-import") (part "PINHD-1X1"))
    )
    (comp (ref "JP211")
      (value "1")
      (footprint "eagle-import:1X01")
      (libsource (lib "eagle-import") (part "PINHD-1X1"))
    )
    (comp (ref "JP212")
      (value "1")
      (footprint "eagle-import:1X01")
      (libsource (lib "eagle-import") (part "PINHD-1X1"))
    )
    (comp (ref "JP213")
      (value "1")
      (footprint "eagle-import:1X01")
      (libsource (lib "eagle-import") (part "PINHD-1X1"))
    )
    (comp (ref "JP214")
      (value "1")
      (footprint "eagle-import:1X01")
      (libsource (lib "eagle-import") (part "PINHD-1X1"))
    )
    (comp (ref "JP215")
      (value "1")
      (footprint "eagle-import:1X01")
      (libsource (lib "eagle-import") (part "PINHD-1X1"))
    )
    (comp (ref "JP216")
      (value "1")
      (footprint "eagle-import:1X01")
      (libsource (lib "eagle-import") (part "PINHD-1X1"))
    )
    (comp (ref "JP217")
      (value "1")
      (footprint "eagle-import:1X01")
      (libsource (lib "eagle-import") (part "PINHD-1X1"))
    )
    (comp (ref "JP218")
      (value "1")
      (footprint "eagle-import:1X01")
      (libsource (lib "eagle-import") (part "PINHD-1X1"))
    )
    (comp (ref "JP219")
      (value "1")
      (footprint "eagle-import:1X01")
      (libsource (lib "eagle-import") (part "PINHD-1X1"))
    )
    (comp (ref "JP220")
      (value "1")
      (footprint "eagle-import:1X01")
      (libsource (lib "eagle-import") (part "PINHD-1X1"))
    )
    (comp (ref "JP221")
      (value "1")
      (footprint "eagle-import:1X01")
      (libsource (lib "eagle-import") (part "PINHD-1X1"))
    )
    (comp (ref "JP222")
      (value "1")
      (footprint "eagle-import:1X01")
      (libsource (lib "eagle-import") (part "PINHD-1X1"))
    )
    (comp (ref "JP223")
      (value "1")
      (footprint "eagle-import:1X01")
      (libsource (lib "eagle-import") (part "PINHD-1X1"))
    )
    (comp (ref "JP224")
      (value "1")
      (footprint "eagle-import:1X01")
      (libsource (lib "eagle-import") (part "PINHD-1X1"))
    )
    (comp (ref "JP225")
      (value "1")
      (footprint "eagle-import:1X01")
      (libsource (lib "eagle-import") (part "PINHD-1X1"))
    )
    (comp (ref "JP226")
      (value "1")
      (footprint "eagle-import:1X01")
      (libsource (lib "eagle-import") (part "PINHD-1X1"))
    )
    (comp (ref "JP227")
      (value "1")
      (footprint "eagle-import:1X01")
      (libsource (lib "eagle-import") (part "PINHD-1X1"))
    )
    (comp (ref "JP228")
      (value "1")
      (footprint "eagle-import:1X01")
      (libsource (lib "eagle-import") (part "PINHD-1X1"))
    )
    (comp (ref "JP229")
      (value "1")
      (footprint "eagle-import:1X01")
      (libsource (lib "eagle-import") (part "PINHD-1X1"))
    )
    (comp (ref "JP230")
      (value "1")
      (footprint "eagle-import:1X01")
      (libsource (lib "eagle-import") (part "PINHD-1X1"))
    )
    (comp (ref "JP231")
      (value "1")
      (footprint "eagle-import:1X01")
      (libsource (lib "eagle-import") (part "PINHD-1X1"))
    )
    (comp (ref "JP232")
      (value "1")
      (footprint "eagle-import:1X01")
      (libsource (lib "eagle-import") (part "PINHD-1X1"))
    )
    (comp (ref "JP233")
      (value "1")
      (footprint "eagle-import:1X01")
      (libsource (lib "eagle-import") (part "PINHD-1X1"))
    )
    (comp (ref "JP234")
      (value "1")
      (footprint "eagle-import:1X01")
      (libsource (lib "eagle-import") (part "PINHD-1X1"))
    )
    (comp (ref "JP235")
      (value "1")
      (footprint "eagle-import:1X01")
      (libsource (lib "eagle-import") (part "PINHD-1X1"))
    )
    (comp (ref "JP236")
      (value "1")
      (footprint "eagle-import:1X01")
      (libsource (lib "eagle-import") (part "PINHD-1X1"))
    )
    (comp (ref "JP237")
      (value "1")
      (footprint "eagle-import:1X01")
      (libsource (lib "eagle-import") (part "PINHD-1X1"))
    )
    (comp (ref "JP238")
      (value "1")
      (footprint "eagle-import:1X01")
      (libsource (lib "eagle-import") (part "PINHD-1X1"))
    )
    (comp (ref "JP239")
      (value "1")
      (footprint "eagle-import:1X01")
      (libsource (lib "eagle-import") (part "PINHD-1X1"))
    )
    (comp (ref "JP240")
      (value "1")
      (footprint "eagle-import:1X01")
      (libsource (lib "eagle-import") (part "PINHD-1X1"))
    )
    (comp (ref "JP241")
      (value "1")
      (footprint "eagle-import:1X01")
      (libsource (lib "eagle-import") (part "PINHD-1X1"))
    )
    (comp (ref "JP242")
      (value "1")
      (footprint "eagle-import:1X01")
      (libsource (lib "eagle-import") (part "PINHD-1X1"))
    )
    (comp (ref "JP243")
      (value "1")
      (footprint "eagle-import:1X01")
      (libsource (lib "eagle-import") (part "PINHD-1X1"))
    )
    (comp (ref "JP244")
      (value "1")
      (footprint "eagle-import:1X01")
      (libsource (lib "eagle-import") (part "PINHD-1X1"))
    )
    (comp (ref "JP245")
      (value "1")
      (footprint "eagle-import:1X01")
      (libsource (lib "eagle-import") (part "PINHD-1X1"))
    )
    (comp (ref "JP246")
      (value "1")
      (footprint "eagle-import:1X01")
      (libsource (lib "eagle-import") (part "PINHD-1X1"))
    )
    (comp (ref "JP247")
      (value "1")
      (footprint "eagle-import:1X01")
      (libsource (lib "eagle-import") (part "PINHD-1X1"))
    )
    (comp (ref "JP248")
      (value "1")
      (footprint "eagle-import:1X01")
      (libsource (lib "eagle-import") (part "PINHD-1X1"))
    )
    (comp (ref "JP249")
      (value "1")
      (footprint "eagle-import:1X01")
      (libsource (lib "eagle-import") (part "PINHD-1X1"))
    )
    (comp (ref "JP250")
      (value "1")
      (footprint "eagle-import:1X01")
      (libsource (lib "eagle-import") (part "PINHD-1X1"))
    )
    (comp (ref "JP251")
      (value "1")
      (footprint "eagle-import:1X01")
      (libsource (lib "eagle-import") (part "PINHD-1X1"))
    )
    (comp (ref "JP252")
      (value "1")
      (footprint "eagle-import:1X01")
      (libsource (lib "eagle-import") (part "PINHD-1X1"))
    )
    (comp (ref "JP253")
      (value "1")
      (footprint "eagle-import:1X01")
      (libsource (lib "eagle-import") (part "PINHD-1X1"))
    )
    (comp (ref "JP254")
      (value "1")
      (footprint "eagle-import:1X01")
      (libsource (lib "eagle-import") (part "PINHD-1X1"))
    )
    (comp (ref "JP255")
      (value "1")
      (footprint "eagle-import:1X01")
      (libsource (lib "eagle-import") (part "PINHD-1X1"))
    )
    (comp (ref "JP256")
      (value "1")
      (footprint "eagle-import:1X01")
      (libsource (lib "eagle-import") (part "PINHD-1X1"))
    )
    (comp (ref "JP257")
      (value "1")
      (footprint "eagle-import:1X01")
      (libsource (lib "eagle-import") (part "PINHD-1X1"))
    )
    (comp (ref "JP258")
      (value "1")
      (footprint "eagle-import:1X01")
      (libsource (lib "eagle-import") (part "PINHD-1X1"))
    )
    (comp (ref "JP259")
      (value "1")
      (footprint "eagle-import:1X01")
      (libsource (lib "eagle-import") (part "PINHD-1X1"))
    )
    (comp (ref "JP260")
      (value "1")
      (footprint "eagle-import:1X01")
      (libsource (lib "eagle-import") (part "PINHD-1X1"))
    )
    (comp (ref "JP261")
      (value "1")
      (footprint "eagle-import:1X01")
      (libsource (lib "eagle-import") (part "PINHD-1X1"))
    )
    (comp (ref "JP262")
      (value "1")
      (footprint "eagle-import:1X01")
      (libsource (lib "eagle-import") (part "PINHD-1X1"))
    )
    (comp (ref "JP263")
      (value "1")
      (footprint "eagle-import:1X01")
      (libsource (lib "eagle-import") (part "PINHD-1X1"))
    )
    (comp (ref "JP264")
      (value "1")
      (footprint "eagle-import:1X01")
      (libsource (lib "eagle-import") (part "PINHD-1X1"))
    )
    (comp (ref "JP265")
      (value "1")
      (footprint "eagle-import:1X01")
      (libsource (lib "eagle-import") (part "PINHD-1X1"))
    )
    (comp (ref "JP266")
      (value "1")
      (footprint "eagle-import:1X01")
      (libsource (lib "eagle-import") (part "PINHD-1X1"))
    )
    (comp (ref "JP267")
      (value "1")
      (footprint "eagle-import:1X01")
      (libsource (lib "eagle-import") (part "PINHD-1X1"))
    )
    (comp (ref "JP268")
      (value "1")
      (footprint "eagle-import:1X01")
      (libsource (lib "eagle-import") (part "PINHD-1X1"))
    )
    (comp (ref "JP269")
      (value "1")
      (footprint "eagle-import:1X01")
      (libsource (lib "eagle-import") (part "PINHD-1X1"))
    )
    (comp (ref "JP270")
      (value "1")
      (footprint "eagle-import:1X01")
      (libsource (lib "eagle-import") (part "PINHD-1X1"))
    )
    (comp (ref "JP271")
      (value "1")
      (footprint "eagle-import:1X01")
      (libsource (lib "eagle-import") (part "PINHD-1X1"))
    )
    (comp (ref "JP272")
      (value "1")
      (footprint "eagle-import:1X01")
      (libsource (lib "eagle-import") (part "PINHD-1X1"))
    )
    (comp (ref "JP273")
      (value "1")
      (footprint "eagle-import:1X01")
      (libsource (lib "eagle-import") (part "PINHD-1X1"))
    )
    (comp (ref "JP274")
      (value "1")
      (footprint "eagle-import:1X01")
      (libsource (lib "eagle-import") (part "PINHD-1X1"))
    )
    (comp (ref "JP275")
      (value "1")
      (footprint "eagle-import:1X01")
      (libsource (lib "eagle-import") (part "PINHD-1X1"))
    )
    (comp (ref "JP276")
      (value "1")
      (footprint "eagle-import:1X01")
      (libsource (lib "eagle-import") (part "PINHD-1X1"))
    )
    (comp (ref "JP277")
      (value "1")
      (footprint "eagle-import:1X01")
      (libsource (lib "eagle-import") (part "PINHD-1X1"))
    )
    (comp (ref "JP278")
      (value "1")
      (footprint "eagle-import:1X01")
      (libsource (lib "eagle-import") (part "PINHD-1X1"))
    )
    (comp (ref "JP279")
      (value "1")
      (footprint "eagle-import:1X01")
      (libsource (lib "eagle-import") (part "PINHD-1X1"))
    )
    (comp (ref "JP280")
      (value "1")
      (footprint "eagle-import:1X01")
      (libsource (lib "eagle-import") (part "PINHD-1X1"))
    )
    (comp (ref "JP281")
      (value "1")
      (footprint "eagle-import:1X01")
      (libsource (lib "eagle-import") (part "PINHD-1X1"))
    )
    (comp (ref "JP282")
      (value "1")
      (footprint "eagle-import:1X01")
      (libsource (lib "eagle-import") (part "PINHD-1X1"))
    )
    (comp (ref "JP283")
      (value "1")
      (footprint "eagle-import:1X01")
      (libsource (lib "eagle-import") (part "PINHD-1X1"))
    )
    (comp (ref "JP284")
      (value "1")
      (footprint "eagle-import:1X01")
      (libsource (lib "eagle-import") (part "PINHD-1X1"))
    )
    (comp (ref "JP285")
      (value "1")
      (footprint "eagle-import:1X01")
      (libsource (lib "eagle-import") (part "PINHD-1X1"))
    )
    (comp (ref "JP286")
      (value "1")
      (footprint "eagle-import:1X01")
      (libsource (lib "eagle-import") (part "PINHD-1X1"))
    )
    (comp (ref "JP287")
      (value "1")
      (footprint "eagle-import:1X01")
      (libsource (lib "eagle-import") (part "PINHD-1X1"))
    )
    (comp (ref "JP288")
      (value "1")
      (footprint "eagle-import:1X01")
      (libsource (lib "eagle-import") (part "PINHD-1X1"))
    )
    (comp (ref "JP289")
      (value "1")
      (footprint "eagle-import:1X01")
      (libsource (lib "eagle-import") (part "PINHD-1X1"))
    )
    (comp (ref "JP290")
      (value "1")
      (footprint "eagle-import:1X01")
      (libsource (lib "eagle-import") (part "PINHD-1X1"))
    )
    (comp (ref "JP291")
      (value "1")
      (footprint "eagle-import:1X01")
      (libsource (lib "eagle-import") (part "PINHD-1X1"))
    )
    (comp (ref "JP292")
      (value "1")
      (footprint "eagle-import:1X01")
      (libsource (lib "eagle-import") (part "PINHD-1X1"))
    )
    (comp (ref "JP293")
      (value "1")
      (footprint "eagle-import:1X01")
      (libsource (lib "eagle-import") (part "PINHD-1X1"))
    )
    (comp (ref "JP294")
      (value "1")
      (footprint "eagle-import:1X01")
      (libsource (lib "eagle-import") (part "PINHD-1X1"))
    )
    (comp (ref "JP295")
      (value "1")
      (footprint "eagle-import:1X01")
      (libsource (lib "eagle-import") (part "PINHD-1X1"))
    )
    (comp (ref "JP296")
      (value "1")
      (footprint "eagle-import:1X01")
      (libsource (lib "eagle-import") (part "PINHD-1X1"))
    )
    (comp (ref "JP297")
      (value "1")
      (footprint "eagle-import:1X01")
      (libsource (lib "eagle-import") (part "PINHD-1X1"))
    )
    (comp (ref "JP298")
      (value "1")
      (footprint "eagle-import:1X01")
      (libsource (lib "eagle-import") (part "PINHD-1X1"))
    )
    (comp (ref "JP299")
      (value "1")
      (footprint "eagle-import:1X01")
      (libsource (lib "eagle-import") (part "PINHD-1X1"))
    )
    (comp (ref "JP300")
      (value "1")
      (footprint "eagle-import:1X01")
      (libsource (lib "eagle-import") (part "PINHD-1X1"))
    )
    (comp (ref "JP301")
      (value "1")
      (footprint "eagle-import:1X01")
      (libsource (lib "eagle-import") (part "PINHD-1X1"))
    )
    (comp (ref "JP302")
      (value "1")
      (footprint "eagle-import:1X01")
      (libsource (lib "eagle-import") (part "PINHD-1X1"))
    )
    (comp (ref "JP303")
      (value "1")
      (footprint "eagle-import:1X01")
      (libsource (lib "eagle-import") (part "PINHD-1X1"))
    )
    (comp (ref "JP304")
      (value "1")
      (footprint "eagle-import:1X01")
      (libsource (lib "eagle-import") (part "PINHD-1X1"))
    )
    (comp (ref "JP305")
      (value "1")
      (footprint "eagle-import:1X01")
      (libsource (lib "eagle-import") (part "PINHD-1X1"))
    )
    (comp (ref "JP306")
      (value "1")
      (footprint "eagle-import:1X01")
      (libsource (lib "eagle-import") (part "PINHD-1X1"))
    )
    (comp (ref "JP307")
      (value "1")
      (footprint "eagle-import:1X01")
      (libsource (lib "eagle-import") (part "PINHD-1X1"))
    )
    (comp (ref "JP308")
      (value "1")
      (footprint "eagle-import:1X01")
      (libsource (lib "eagle-import") (part "PINHD-1X1"))
    )
    (comp (ref "JP309")
      (value "1")
      (footprint "eagle-import:1X01")
      (libsource (lib "eagle-import") (part "PINHD-1X1"))
    )
    (comp (ref "JP310")
      (value "1")
      (footprint "eagle-import:1X01")
      (libsource (lib "eagle-import") (part "PINHD-1X1"))
    )
    (comp (ref "JP311")
      (value "1")
      (footprint "eagle-import:1X01")
      (libsource (lib "eagle-import") (part "PINHD-1X1"))
    )
    (comp (ref "JP312")
      (value "1")
      (footprint "eagle-import:1X01")
      (libsource (lib "eagle-import") (part "PINHD-1X1"))
    )
    (comp (ref "JP313")
      (value "1")
      (footprint "eagle-import:1X01")
      (libsource (lib "eagle-import") (part "PINHD-1X1"))
    )
    (comp (ref "JP314")
      (value "1")
      (footprint "eagle-import:1X01")
      (libsource (lib "eagle-import") (part "PINHD-1X1"))
    )
    (comp (ref "JP315")
      (value "1")
      (footprint "eagle-import:1X01")
      (libsource (lib "eagle-import") (part "PINHD-1X1"))
    )
    (comp (ref "JP316")
      (value "1")
      (footprint "eagle-import:1X01")
      (libsource (lib "eagle-import") (part "PINHD-1X1"))
    )
    (comp (ref "JP317")
      (value "1")
      (footprint "eagle-import:1X01")
      (libsource (lib "eagle-import") (part "PINHD-1X1"))
    )
    (comp (ref "JP318")
      (value "1")
      (footprint "eagle-import:1X01")
      (libsource (lib "eagle-import") (part "PINHD-1X1"))
    )
    (comp (ref "JP319")
      (value "1")
      (footprint "eagle-import:1X01")
      (libsource (lib "eagle-import") (part "PINHD-1X1"))
    )
    (comp (ref "JP320")
      (value "1")
      (footprint "eagle-import:1X01")
      (libsource (lib "eagle-import") (part "PINHD-1X1"))
    )
    (comp (ref "JP321")
      (value "1")
      (footprint "eagle-import:1X01")
      (libsource (lib "eagle-import") (part "PINHD-1X1"))
    )
    (comp (ref "JP322")
      (value "1")
      (footprint "eagle-import:1X01")
      (libsource (lib "eagle-import") (part "PINHD-1X1"))
    )
    (comp (ref "JP323")
      (value "1")
      (footprint "eagle-import:1X01")
      (libsource (lib "eagle-import") (part "PINHD-1X1"))
    )
    (comp (ref "JP324")
      (value "1")
      (footprint "eagle-import:1X01")
      (libsource (lib "eagle-import") (part "PINHD-1X1"))
    )
    (comp (ref "JP325")
      (value "1")
      (footprint "eagle-import:1X01")
      (libsource (lib "eagle-import") (part "PINHD-1X1"))
    )
    (comp (ref "JP326")
      (value "1")
      (footprint "eagle-import:1X01")
      (libsource (lib "eagle-import") (part "PINHD-1X1"))
    )
    (comp (ref "JP327")
      (value "1")
      (footprint "eagle-import:1X01")
      (libsource (lib "eagle-import") (part "PINHD-1X1"))
    )
    (comp (ref "JP328")
      (value "1")
      (footprint "eagle-import:1X01")
      (libsource (lib "eagle-import") (part "PINHD-1X1"))
    )
    (comp (ref "JP329")
      (value "1")
      (footprint "eagle-import:1X01")
      (libsource (lib "eagle-import") (part "PINHD-1X1"))
    )
    (comp (ref "JP330")
      (value "1")
      (footprint "eagle-import:1X01")
      (libsource (lib "eagle-import") (part "PINHD-1X1"))
    )
    (comp (ref "JP331")
      (value "1")
      (footprint "eagle-import:1X01")
      (libsource (lib "eagle-import") (part "PINHD-1X1"))
    )
    (comp (ref "JP332")
      (value "1")
      (footprint "eagle-import:1X01")
      (libsource (lib "eagle-import") (part "PINHD-1X1"))
    )
    (comp (ref "JP333")
      (value "1")
      (footprint "eagle-import:1X01")
      (libsource (lib "eagle-import") (part "PINHD-1X1"))
    )
    (comp (ref "JP334")
      (value "1")
      (footprint "eagle-import:1X01")
      (libsource (lib "eagle-import") (part "PINHD-1X1"))
    )
    (comp (ref "JP335")
      (value "1")
      (footprint "eagle-import:1X01")
      (libsource (lib "eagle-import") (part "PINHD-1X1"))
    )
    (comp (ref "JP336")
      (value "1")
      (footprint "eagle-import:1X01")
      (libsource (lib "eagle-import") (part "PINHD-1X1"))
    )
    (comp (ref "JP337")
      (value "1")
      (footprint "eagle-import:1X01")
      (libsource (lib "eagle-import") (part "PINHD-1X1"))
    )
    (comp (ref "JP338")
      (value "1")
      (footprint "eagle-import:1X01")
      (libsource (lib "eagle-import") (part "PINHD-1X1"))
    )
    (comp (ref "JP339")
      (value "1")
      (footprint "eagle-import:1X01")
      (libsource (lib "eagle-import") (part "PINHD-1X1"))
    )
    (comp (ref "JP340")
      (value "1")
      (footprint "eagle-import:1X01")
      (libsource (lib "eagle-import") (part "PINHD-1X1"))
    )
    (comp (ref "JP341")
      (value "1")
      (footprint "eagle-import:1X01")
      (libsource (lib "eagle-import") (part "PINHD-1X1"))
    )
    (comp (ref "JP342")
      (value "1")
      (footprint "eagle-import:1X01")
      (libsource (lib "eagle-import") (part "PINHD-1X1"))
    )
    (comp (ref "C2")
      (value "10uF")
      (footprint "eagle-import:RESC0805_N")
      (libsource (lib "eagle-import") (part "CAPACITOR_0805_N"))
    )
    (comp (ref "C3")
      (value "0.1uF")
      (footprint "eagle-import:RESC0402_N")
      (libsource (lib "eagle-import") (part "CAPACITOR_0402_N"))
    )
    (comp (ref "C4")
      (value "10uF")
      (footprint "eagle-import:RESC0805_N")
      (libsource (lib "eagle-import") (part "CAPACITOR_0805_N"))
    )
    (comp (ref "C5")
      (value "0.1uF")
      (footprint "eagle-import:RESC0402_N")
      (libsource (lib "eagle-import") (part "CAPACITOR_0402_N"))
    )
    (comp (ref "C6")
      (value "10uF")
      (footprint "eagle-import:RESC0805_N")
      (libsource (lib "eagle-import") (part "CAPACITOR_0805_N"))
    )
    (comp (ref "C7")
      (value "0.1uF")
      (footprint "eagle-import:RESC0402_N")
      (libsource (lib "eagle-import") (part "CAPACITOR_0402_N"))
    )
    (comp (ref "C8")
      (value "10uF")
      (footprint "eagle-import:RESC0805_N")
      (libsource (lib "eagle-import") (part "CAPACITOR_0805_N"))
    )
    (comp (ref "C9")
      (value "0.1uF")
      (footprint "eagle-import:RESC0402_N")
      (libsource (lib "eagle-import") (part "CAPACITOR_0402_N"))
    )
    (comp (ref "C10")
      (value "10uF")
      (footprint "eagle-import:RESC0805_N")
      (libsource (lib "eagle-import") (part "CAPACITOR_0805_N"))
    )
    (comp (ref "C11")
      (value "0.1uF")
      (footprint "eagle-import:RESC0402_N")
      (libsource (lib "eagle-import") (part "CAPACITOR_0402_N"))
    )
    (comp (ref "C12")
      (value "10uF")
      (footprint "eagle-import:RESC0805_N")
      (libsource (lib "eagle-import") (part "CAPACITOR_0805_N"))
    )
    (comp (ref "C13")
      (value "0.1uF")
      (footprint "eagle-import:RESC0402_N")
      (libsource (lib "eagle-import") (part "CAPACITOR_0402_N"))
    )
    (comp (ref "U1")
      (value "AMS1117-3.3")
      (footprint "eagle-import:SOT-223-3")
      (fields
        (field (name "HOUSEPART") "NO")
        (field (name "MPN") "NCP1117LPST33T3G")
        (field (name "MPN_1") "AMS1117-3.3")
      )
      (libsource (lib "eagle-import") (part "NCP1117LPST33T3G"))
    )
    (comp (ref "U2")
      (value "AMS1117-2.5")
      (footprint "eagle-import:SOT-223-3")
      (fields
        (field (name "HOUSEPART") "NO")
        (field (name "MPN") "NCP1117LPST33T3G")
        (field (name "MPN_1") "AMS1117-2.5")
      )
      (libsource (lib "eagle-import") (part "NCP1117LPST33T3G"))
    )
    (comp (ref "U3")
      (value "AMS1117-1.2")
      (footprint "eagle-import:SOT-223-3")
      (fields
        (field (name "HOUSEPART") "NO")
        (field (name "MPN") "NCP1117LPST33T3G")
        (field (name "MPN_1") "AMS1117-1.2")
      )
      (libsource (lib "eagle-import") (part "NCP1117LPST33T3G"))
    )
    (comp (ref "C1")
      (value "0.1uF")
      (footprint "eagle-import:RESC0402_N")
      (libsource (lib "eagle-import") (part "CAPACITOR_0402_N"))
    )
    (comp (ref "C14")
      (value "0.1uF")
      (footprint "eagle-import:RESC0402_N")
      (libsource (lib "eagle-import") (part "CAPACITOR_0402_N"))
    )
    (comp (ref "C15")
      (value "0.1uF")
      (footprint "eagle-import:RESC0402_N")
      (libsource (lib "eagle-import") (part "CAPACITOR_0402_N"))
    )
    (comp (ref "C16")
      (value "0.1uF")
      (footprint "eagle-import:RESC0402_N")
      (libsource (lib "eagle-import") (part "CAPACITOR_0402_N"))
    )
    (comp (ref "C17")
      (value "0.1uF")
      (footprint "eagle-import:RESC0402_N")
      (libsource (lib "eagle-import") (part "CAPACITOR_0402_N"))
    )
    (comp (ref "C18")
      (value "0.1uF")
      (footprint "eagle-import:RESC0402_N")
      (libsource (lib "eagle-import") (part "CAPACITOR_0402_N"))
    )
    (comp (ref "C19")
      (value "0.1uF")
      (footprint "eagle-import:RESC0402_N")
      (libsource (lib "eagle-import") (part "CAPACITOR_0402_N"))
    )
    (comp (ref "C20")
      (value "0.1uF")
      (footprint "eagle-import:RESC0402_N")
      (libsource (lib "eagle-import") (part "CAPACITOR_0402_N"))
    )
    (comp (ref "C21")
      (value "0.1uF")
      (footprint "eagle-import:RESC0402_N")
      (libsource (lib "eagle-import") (part "CAPACITOR_0402_N"))
    )
    (comp (ref "C22")
      (value "0.1uF")
      (footprint "eagle-import:RESC0402_N")
      (libsource (lib "eagle-import") (part "CAPACITOR_0402_N"))
    )
    (comp (ref "C23")
      (value "0.1uF")
      (footprint "eagle-import:RESC0402_N")
      (libsource (lib "eagle-import") (part "CAPACITOR_0402_N"))
    )
    (comp (ref "C24")
      (value "0.1uF")
      (footprint "eagle-import:RESC0402_N")
      (libsource (lib "eagle-import") (part "CAPACITOR_0402_N"))
    )
    (comp (ref "C25")
      (value "0.1uF")
      (footprint "eagle-import:RESC0402_N")
      (libsource (lib "eagle-import") (part "CAPACITOR_0402_N"))
    )
    (comp (ref "C26")
      (value "0.1uF")
      (footprint "eagle-import:RESC0402_N")
      (libsource (lib "eagle-import") (part "CAPACITOR_0402_N"))
    )
    (comp (ref "IC1")
      (value "EP4CE30F23C6N")
      (footprint "eagle-import:BGA484C100P22X22_2300X2300X240")
      (fields (field (name "MOUSER_PART_NUMBER") "989-EP4CE30F23C6N"))
      (libsource (lib "eagle-import") (part "EP4CE30F23C6N"))
    )
    (comp (ref "IC2")
      (value "EPCQ16ASI8N")
      (footprint "eagle-import:SOIC127P600X175-8N")
      (fields (field (name "MOUSER_PART_NUMBER") "989-EPCQ16ASI8N"))
      (libsource (lib "eagle-import") (part "EPCQ16ASI8N"))
    )
    (comp (ref "J1")
      (value "2x5")
      (footprint "eagle-import:2X5-SHROUDED")
      (libsource (lib "eagle-import") (part "CONN_05X2SHD"))
    )
    (comp (ref "JP3")
      (value "1x8")
      (footprint "eagle-import:1X08")
      (libsource (lib "eagle-import") (part "PINHD-1X8"))
    )
    (comp (ref "LED33")
      (value "red")
      (footprint "eagle-import:CHIP-LED0603")
      (libsource (lib "eagle-import") (part "LEDCHIP-LED0603"))
    )
    (comp (ref "LED34")
      (value "red")
      (footprint "eagle-import:CHIP-LED0603")
      (libsource (lib "eagle-import") (part "LEDCHIP-LED0603"))
    )
    (comp (ref "LED35")
      (value "red")
      (footprint "eagle-import:CHIP-LED0603")
      (libsource (lib "eagle-import") (part "LEDCHIP-LED0603"))
    )
    (comp (ref "LED36")
      (value "red")
      (footprint "eagle-import:CHIP-LED0603")
      (libsource (lib "eagle-import") (part "LEDCHIP-LED0603"))
    )
    (comp (ref "LED37")
      (value "red")
      (footprint "eagle-import:CHIP-LED0603")
      (libsource (lib "eagle-import") (part "LEDCHIP-LED0603"))
    )
    (comp (ref "LED38")
      (value "red")
      (footprint "eagle-import:CHIP-LED0603")
      (libsource (lib "eagle-import") (part "LEDCHIP-LED0603"))
    )
    (comp (ref "LED39")
      (value "red")
      (footprint "eagle-import:CHIP-LED0603")
      (libsource (lib "eagle-import") (part "LEDCHIP-LED0603"))
    )
    (comp (ref "LED40")
      (value "red")
      (footprint "eagle-import:CHIP-LED0603")
      (libsource (lib "eagle-import") (part "LEDCHIP-LED0603"))
    )
    (comp (ref "R1")
      (value "10k")
      (footprint "eagle-import:RES-0402")
      (libsource (lib "eagle-import") (part "RES-0402"))
    )
    (comp (ref "R2")
      (value "10k")
      (footprint "eagle-import:RES-0402")
      (libsource (lib "eagle-import") (part "RES-0402"))
    )
    (comp (ref "R3")
      (value "10k")
      (footprint "eagle-import:RES-0402")
      (libsource (lib "eagle-import") (part "RES-0402"))
    )
    (comp (ref "R4")
      (value "0")
      (footprint "eagle-import:RES-0402")
      (libsource (lib "eagle-import") (part "RES-0402"))
    )
    (comp (ref "R5")
      (value "10k")
      (footprint "eagle-import:RES-0402")
      (libsource (lib "eagle-import") (part "RES-0402"))
    )
    (comp (ref "R6")
      (value "10k")
      (footprint "eagle-import:RES-0402")
      (libsource (lib "eagle-import") (part "RES-0402"))
    )
    (comp (ref "R7")
      (value "10k")
      (footprint "eagle-import:RES-0402")
      (libsource (lib "eagle-import") (part "RES-0402"))
    )
    (comp (ref "R8")
      (value "10k")
      (footprint "eagle-import:RES-0402")
      (libsource (lib "eagle-import") (part "RES-0402"))
    )
    (comp (ref "R9")
      (value "10k")
      (footprint "eagle-import:RES-0402")
      (libsource (lib "eagle-import") (part "RES-0402"))
    )
    (comp (ref "R17")
      (value "0")
      (footprint "eagle-import:RES-0402")
      (libsource (lib "eagle-import") (part "RES-0402"))
    )
    (comp (ref "R18")
      (value "0")
      (footprint "eagle-import:RES-0402")
      (libsource (lib "eagle-import") (part "RES-0402"))
    )
    (comp (ref "R19")
      (value "0")
      (footprint "eagle-import:RES-0402")
      (libsource (lib "eagle-import") (part "RES-0402"))
    )
    (comp (ref "R20")
      (value "0")
      (footprint "eagle-import:RES-0402")
      (libsource (lib "eagle-import") (part "RES-0402"))
    )
    (comp (ref "R38")
      (value "1k")
      (footprint "eagle-import:RES-0402")
      (libsource (lib "eagle-import") (part "RES-0402"))
    )
    (comp (ref "R39")
      (value "1k")
      (footprint "eagle-import:RES-0402")
      (libsource (lib "eagle-import") (part "RES-0402"))
    )
    (comp (ref "R40")
      (value "1k")
      (footprint "eagle-import:RES-0402")
      (libsource (lib "eagle-import") (part "RES-0402"))
    )
    (comp (ref "R41")
      (value "1k")
      (footprint "eagle-import:RES-0402")
      (libsource (lib "eagle-import") (part "RES-0402"))
    )
    (comp (ref "R42")
      (value "1k")
      (footprint "eagle-import:RES-0402")
      (libsource (lib "eagle-import") (part "RES-0402"))
    )
    (comp (ref "R43")
      (value "1k")
      (footprint "eagle-import:RES-0402")
      (libsource (lib "eagle-import") (part "RES-0402"))
    )
    (comp (ref "R44")
      (value "1k")
      (footprint "eagle-import:RES-0402")
      (libsource (lib "eagle-import") (part "RES-0402"))
    )
    (comp (ref "R45")
      (value "1k")
      (footprint "eagle-import:RES-0402")
      (libsource (lib "eagle-import") (part "RES-0402"))
    )
    (comp (ref "SW1")
      (value "SKQGADE010")
      (footprint "eagle-import:SW4-SMD-5.2X5.2X1.5MM")
      (libsource (lib "eagle-import") (part "SMD-BUTTON(4P-5.2X5.2X1.5MM-SKQGADE010)-SKQGADE010"))
    )
    (comp (ref "SW2")
      (value "SKQGADE010")
      (footprint "eagle-import:SW4-SMD-5.2X5.2X1.5MM")
      (libsource (lib "eagle-import") (part "SMD-BUTTON(4P-5.2X5.2X1.5MM-SKQGADE010)-SKQGADE010"))
    )
    (comp (ref "Y1")
      (value "OSCILLATORSMD-5X3")
      (footprint "eagle-import:OSCILLATOR-SMD-5X3.2")
      (fields (field (name "LCSC") "C2901546"))
      (libsource (lib "eagle-import") (part "OSCILLATORSMD-5X3"))
    )
  )
  (nets
    (net (code "1") (name "1V2") (class "Default")
      (node (ref "C4") (pin "2") (pinfunction "2_2") (pintype "passive"))
      (node (ref "C5") (pin "2") (pinfunction "2_2") (pintype "passive"))
      (node (ref "JP3") (pin "7") (pinfunction "7_7") (pintype "passive"))
      (node (ref "R18") (pin "P$1") (pinfunction "P$1_P$1") (pintype "bidirectional"))
      (node (ref "R19") (pin "P$1") (pinfunction "P$1_P$1") (pintype "bidirectional"))
      (node (ref "U3") (pin "P$1") (pinfunction "VOUT_P$1") (pintype "bidirectional"))
      (node (ref "U3") (pin "P$3") (pinfunction "VOUT_P$3") (pintype "bidirectional"))
    )
    (net (code "2") (name "2V5") (class "Default")
      (node (ref "C2") (pin "2") (pinfunction "2_2") (pintype "passive"))
      (node (ref "C3") (pin "2") (pinfunction "2_2") (pintype "passive"))
      (node (ref "JP3") (pin "5") (pinfunction "5_5") (pintype "passive"))
      (node (ref "R17") (pin "P$1") (pinfunction "P$1_P$1") (pintype "bidirectional"))
      (node (ref "R20") (pin "P$1") (pinfunction "P$1_P$1") (pintype "bidirectional"))
      (node (ref "R39") (pin "P$1") (pinfunction "P$1_P$1") (pintype "bidirectional"))
      (node (ref "U2") (pin "P$1") (pinfunction "VOUT_P$1") (pintype "bidirectional"))
      (node (ref "U2") (pin "P$3") (pinfunction "VOUT_P$3") (pintype "bidirectional"))
    )
    (net (code "3") (name "3V3") (class "Default")
      (node (ref "C1") (pin "2") (pinfunction "2_2") (pintype "passive"))
      (node (ref "C12") (pin "2") (pinfunction "2_2") (pintype "passive"))
      (node (ref "C13") (pin "2") (pinfunction "2_2") (pintype "passive"))
      (node (ref "C14") (pin "2") (pinfunction "2_2") (pintype "passive"))
      (node (ref "C8") (pin "2") (pinfunction "2_2") (pintype "passive"))
      (node (ref "C9") (pin "2") (pinfunction "2_2") (pintype "passive"))
      (node (ref "IC2") (pin "3") (pinfunction "DATA2_3") (pintype "bidirectional"))
      (node (ref "IC2") (pin "7") (pinfunction "DATA3_7") (pintype "bidirectional"))
      (node (ref "IC2") (pin "8") (pinfunction "VCC_8") (pintype "bidirectional"))
      (node (ref "J1") (pin "4") (pinfunction "4_4") (pintype "passive"))
      (node (ref "JP3") (pin "3") (pinfunction "3_3") (pintype "passive"))
      (node (ref "R1") (pin "P$2") (pinfunction "P$2_P$2") (pintype "bidirectional"))
      (node (ref "R2") (pin "P$2") (pinfunction "P$2_P$2") (pintype "bidirectional"))
      (node (ref "R3") (pin "P$2") (pinfunction "P$2_P$2") (pintype "bidirectional"))
      (node (ref "R38") (pin "P$1") (pinfunction "P$1_P$1") (pintype "bidirectional"))
      (node (ref "R5") (pin "P$2") (pinfunction "P$2_P$2") (pintype "bidirectional"))
      (node (ref "R7") (pin "P$2") (pinfunction "P$2_P$2") (pintype "bidirectional"))
      (node (ref "U1") (pin "P$1") (pinfunction "VOUT_P$1") (pintype "bidirectional"))
      (node (ref "U1") (pin "P$3") (pinfunction "VOUT_P$3") (pintype "bidirectional"))
      (node (ref "U3") (pin "P$4") (pinfunction "VIN_P$4") (pintype "bidirectional"))
      (node (ref "Y1") (pin "4") (pinfunction "VCC_4") (pintype "bidirectional"))
    )
    (net (code "4") (name "5V") (class "Default")
      (node (ref "C10") (pin "2") (pinfunction "2_2") (pintype "passive"))
      (node (ref "C11") (pin "2") (pinfunction "2_2") (pintype "passive"))
      (node (ref "C6") (pin "2") (pinfunction "2_2") (pintype "passive"))
      (node (ref "C7") (pin "2") (pinfunction "2_2") (pintype "passive"))
      (node (ref "JP3") (pin "1") (pinfunction "1_1") (pintype "passive"))
      (node (ref "U1") (pin "P$4") (pinfunction "VIN_P$4") (pintype "bidirectional"))
      (node (ref "U2") (pin "P$4") (pinfunction "VIN_P$4") (pintype "bidirectional"))
    )
    (net (code "5") (name "ASDO") (class "Default")
      (node (ref "IC1") (pin "D1") (pinfunction "IO_52_D1") (pintype "bidirectional"))
      (node (ref "IC2") (pin "5") (pinfunction "DATA0_5") (pintype "bidirectional"))
      (node (ref "JP39") (pin "1") (pinfunction "1_1") (pintype "passive"))
    )
    (net (code "6") (name "CLK1") (class "Default")
      (node (ref "IC1") (pin "G1") (pinfunction "CLK1_G1") (pintype "bidirectional"))
      (node (ref "JP16") (pin "1") (pinfunction "1_1") (pintype "passive"))
      (node (ref "Y1") (pin "3") (pinfunction "OUT_3") (pintype "bidirectional"))
    )
    (net (code "7") (name "CLK2") (class "Default")
      (node (ref "IC1") (pin "T2") (pinfunction "CLK2_T2") (pintype "bidirectional"))
      (node (ref "JP18") (pin "1") (pinfunction "1_1") (pintype "passive"))
    )
    (net (code "8") (name "CLK3") (class "Default")
      (node (ref "IC1") (pin "T1") (pinfunction "CLK3_T1") (pintype "bidirectional"))
      (node (ref "JP17") (pin "1") (pinfunction "1_1") (pintype "passive"))
    )
    (net (code "9") (name "CLK4") (class "Default")
      (node (ref "IC1") (pin "G21") (pinfunction "CLK4_G21") (pintype "bidirectional"))
      (node (ref "JP19") (pin "1") (pinfunction "1_1") (pintype "passive"))
    )
    (net (code "10") (name "CLK5") (class "Default")
      (node (ref "IC1") (pin "G22") (pinfunction "CLK5_G22") (pintype "bidirectional"))
      (node (ref "JP20") (pin "1") (pinfunction "1_1") (pintype "passive"))
    )
    (net (code "11") (name "CLK6") (class "Default")
      (node (ref "IC1") (pin "T21") (pinfunction "CLK6_T21") (pintype "bidirectional"))
      (node (ref "JP22") (pin "1") (pinfunction "1_1") (pintype "passive"))
    )
    (net (code "12") (name "CLK7") (class "Default")
      (node (ref "IC1") (pin "T22") (pinfunction "CLK7_T22") (pintype "bidirectional"))
      (node (ref "JP21") (pin "1") (pinfunction "1_1") (pintype "passive"))
    )
    (net (code "13") (name "CLK8") (class "Default")
      (node (ref "IC1") (pin "A12") (pinfunction "CLK8_A12") (pintype "bidirectional"))
      (node (ref "JP23") (pin "1") (pinfunction "1_1") (pintype "passive"))
    )
    (net (code "14") (name "CLK9") (class "Default")
      (node (ref "IC1") (pin "B12") (pinfunction "CLK9_B12") (pintype "bidirectional"))
      (node (ref "JP24") (pin "1") (pinfunction "1_1") (pintype "passive"))
    )
    (net (code "15") (name "CLK10") (class "Default")
      (node (ref "IC1") (pin "A11") (pinfunction "CLK10_A11") (pintype "bidirectional"))
      (node (ref "JP26") (pin "1") (pinfunction "1_1") (pintype "passive"))
    )
    (net (code "16") (name "CLK11") (class "Default")
      (node (ref "IC1") (pin "B11") (pinfunction "CLK11_B11") (pintype "bidirectional"))
      (node (ref "JP25") (pin "1") (pinfunction "1_1") (pintype "passive"))
    )
    (net (code "17") (name "CLK12") (class "Default")
      (node (ref "IC1") (pin "AB12") (pinfunction "CLK12_AB12") (pintype "bidirectional"))
      (node (ref "JP27") (pin "1") (pinfunction "1_1") (pintype "passive"))
    )
    (net (code "18") (name "CLK13") (class "Default")
      (node (ref "IC1") (pin "AA12") (pinfunction "CLK13_AA12") (pintype "bidirectional"))
      (node (ref "JP28") (pin "1") (pinfunction "1_1") (pintype "passive"))
    )
    (net (code "19") (name "CLK14") (class "Default")
      (node (ref "IC1") (pin "AB11") (pinfunction "CLK14_AB11") (pintype "bidirectional"))
      (node (ref "JP30") (pin "1") (pinfunction "1_1") (pintype "passive"))
    )
    (net (code "20") (name "CLK15") (class "Default")
      (node (ref "IC1") (pin "AA11") (pinfunction "CLK15_AA11") (pintype "bidirectional"))
      (node (ref "JP29") (pin "1") (pinfunction "1_1") (pintype "passive"))
    )
    (net (code "21") (name "CONF_DONE") (class "Default")
      (node (ref "IC1") (pin "M18") (pinfunction "CONF_DONE_M18") (pintype "bidirectional"))
      (node (ref "R3") (pin "P$1") (pinfunction "P$1_P$1") (pintype "bidirectional"))
    )
    (net (code "22") (name "DATA0") (class "Default")
      (node (ref "IC1") (pin "K1") (pinfunction "IO_140_K1") (pintype "bidirectional"))
      (node (ref "IC2") (pin "2") (pinfunction "DATA1_2") (pintype "bidirectional"))
      (node (ref "JP113") (pin "1") (pinfunction "1_1") (pintype "passive"))
    )
    (net (code "23") (name "DCLK") (class "Default")
      (node (ref "IC1") (pin "K2") (pinfunction "DCLK_K2") (pintype "bidirectional"))
      (node (ref "IC2") (pin "6") (pinfunction "DCLK_6") (pintype "bidirectional"))
    )
    (net (code "24") (name "GND") (class "Default")
      (node (ref "C1") (pin "1") (pinfunction "1_1") (pintype "passive"))
      (node (ref "C10") (pin "1") (pinfunction "1_1") (pintype "passive"))
      (node (ref "C11") (pin "1") (pinfunction "1_1") (pintype "passive"))
      (node (ref "C12") (pin "1") (pinfunction "1_1") (pintype "passive"))
      (node (ref "C13") (pin "1") (pinfunction "1_1") (pintype "passive"))
      (node (ref "C14") (pin "1") (pinfunction "1_1") (pintype "passive"))
      (node (ref "C15") (pin "1") (pinfunction "1_1") (pintype "passive"))
      (node (ref "C16") (pin "1") (pinfunction "1_1") (pintype "passive"))
      (node (ref "C17") (pin "1") (pinfunction "1_1") (pintype "passive"))
      (node (ref "C18") (pin "1") (pinfunction "1_1") (pintype "passive"))
      (node (ref "C19") (pin "1") (pinfunction "1_1") (pintype "passive"))
      (node (ref "C2") (pin "1") (pinfunction "1_1") (pintype "passive"))
      (node (ref "C20") (pin "1") (pinfunction "1_1") (pintype "passive"))
      (node (ref "C21") (pin "1") (pinfunction "1_1") (pintype "passive"))
      (node (ref "C22") (pin "1") (pinfunction "1_1") (pintype "passive"))
      (node (ref "C23") (pin "1") (pinfunction "1_1") (pintype "passive"))
      (node (ref "C24") (pin "1") (pinfunction "1_1") (pintype "passive"))
      (node (ref "C25") (pin "1") (pinfunction "1_1") (pintype "passive"))
      (node (ref "C26") (pin "1") (pinfunction "1_1") (pintype "passive"))
      (node (ref "C3") (pin "1") (pinfunction "1_1") (pintype "passive"))
      (node (ref "C4") (pin "1") (pinfunction "1_1") (pintype "passive"))
      (node (ref "C5") (pin "1") (pinfunction "1_1") (pintype "passive"))
      (node (ref "C6") (pin "1") (pinfunction "1_1") (pintype "passive"))
      (node (ref "C7") (pin "1") (pinfunction "1_1") (pintype "passive"))
      (node (ref "C8") (pin "1") (pinfunction "1_1") (pintype "passive"))
      (node (ref "C9") (pin "1") (pinfunction "1_1") (pintype "passive"))
      (node (ref "IC1") (pin "A1") (pinfunction "GND_1_A1") (pintype "bidirectional"))
      (node (ref "IC1") (pin "A22") (pinfunction "GND_2_A22") (pintype "bidirectional"))
      (node (ref "IC1") (pin "AA2") (pinfunction "GND_63_AA2") (pintype "bidirectional"))
      (node (ref "IC1") (pin "AA22") (pinfunction "GND_64_AA22") (pintype "bidirectional"))
      (node (ref "IC1") (pin "AB1") (pinfunction "GND_65_AB1") (pintype "bidirectional"))
      (node (ref "IC1") (pin "AB22") (pinfunction "GND_67_AB22") (pintype "bidirectional"))
      (node (ref "IC1") (pin "AB6") (pinfunction "GND_66_AB6") (pintype "bidirectional"))
      (node (ref "IC1") (pin "C11") (pinfunction "GND_5_C11") (pintype "bidirectional"))
      (node (ref "IC1") (pin "C12") (pinfunction "GND_6_C12") (pintype "bidirectional"))
      (node (ref "IC1") (pin "C14") (pinfunction "GND_7_C14") (pintype "bidirectional"))
      (node (ref "IC1") (pin "C16") (pinfunction "GND_8_C16") (pintype "bidirectional"))
      (node (ref "IC1") (pin "C18") (pinfunction "GND_9_C18") (pintype "bidirectional"))
      (node (ref "IC1") (pin "C5") (pinfunction "GND_3_C5") (pintype "bidirectional"))
      (node (ref "IC1") (pin "C9") (pinfunction "GND_4_C9") (pintype "bidirectional"))
      (node (ref "IC1") (pin "D3") (pinfunction "GND_10_D3") (pintype "bidirectional"))
      (node (ref "IC1") (pin "D8") (pinfunction "GND_11_D8") (pintype "bidirectional"))
      (node (ref "IC1") (pin "E18") (pinfunction "GNDA2_E18") (pintype "bidirectional"))
      (node (ref "IC1") (pin "E20") (pinfunction "GND_12_E20") (pintype "bidirectional"))
      (node (ref "IC1") (pin "F12") (pinfunction "GND_14_F12") (pintype "bidirectional"))
      (node (ref "IC1") (pin "F3") (pinfunction "GND_13_F3") (pintype "bidirectional"))
      (node (ref "IC1") (pin "F5") (pinfunction "GNDA3_F5") (pintype "bidirectional"))
      (node (ref "IC1") (pin "G2") (pinfunction "GND_15_G2") (pintype "bidirectional"))
      (node (ref "IC1") (pin "G20") (pinfunction "GND_16_G20") (pintype "bidirectional"))
      (node (ref "IC1") (pin "H12") (pinfunction "GND_18_H12") (pintype "bidirectional"))
      (node (ref "IC1") (pin "H13") (pinfunction "GND_19_H13") (pintype "bidirectional"))
      (node (ref "IC1") (pin "H3") (pinfunction "GND_17_H3") (pintype "bidirectional"))
      (node (ref "IC1") (pin "J15") (pinfunction "GND_21_J15") (pintype "bidirectional"))
      (node (ref "IC1") (pin "J19") (pinfunction "GND_22_J19") (pintype "bidirectional"))
      (node (ref "IC1") (pin "J9") (pinfunction "GND_20_J9") (pintype "bidirectional"))
      (node (ref "IC1") (pin "K10") (pinfunction "GND_24_K10") (pintype "bidirectional"))
      (node (ref "IC1") (pin "K11") (pinfunction "GND_25_K11") (pintype "bidirectional"))
      (node (ref "IC1") (pin "K12") (pinfunction "GND_26_K12") (pintype "bidirectional"))
      (node (ref "IC1") (pin "K13") (pinfunction "GND_27_K13") (pintype "bidirectional"))
      (node (ref "IC1") (pin "K16") (pinfunction "GND_28_K16") (pintype "bidirectional"))
      (node (ref "IC1") (pin "K3") (pinfunction "GND_23_K3") (pintype "bidirectional"))
      (node (ref "IC1") (pin "L10") (pinfunction "GND_29_L10") (pintype "bidirectional"))
      (node (ref "IC1") (pin "L11") (pinfunction "GND_30_L11") (pintype "bidirectional"))
      (node (ref "IC1") (pin "L12") (pinfunction "GND_31_L12") (pintype "bidirectional"))
      (node (ref "IC1") (pin "L13") (pinfunction "GND_32_L13") (pintype "bidirectional"))
      (node (ref "IC1") (pin "L15") (pinfunction "GND_33_L15") (pintype "bidirectional"))
      (node (ref "IC1") (pin "L20") (pinfunction "GND_34_L20") (pintype "bidirectional"))
      (node (ref "IC1") (pin "M10") (pinfunction "GND_35_M10") (pintype "bidirectional"))
      (node (ref "IC1") (pin "M11") (pinfunction "GND_36_M11") (pintype "bidirectional"))
      (node (ref "IC1") (pin "M12") (pinfunction "GND_37_M12") (pintype "bidirectional"))
      (node (ref "IC1") (pin "M13") (pinfunction "GND_38_M13") (pintype "bidirectional"))
      (node (ref "IC1") (pin "N10") (pinfunction "GND_40_N10") (pintype "bidirectional"))
      (node (ref "IC1") (pin "N11") (pinfunction "GND_41_N11") (pintype "bidirectional"))
      (node (ref "IC1") (pin "N12") (pinfunction "GND_42_N12") (pintype "bidirectional"))
      (node (ref "IC1") (pin "N13") (pinfunction "GND_43_N13") (pintype "bidirectional"))
      (node (ref "IC1") (pin "N15") (pinfunction "GND_44_N15") (pintype "bidirectional"))
      (node (ref "IC1") (pin "N3") (pinfunction "GND_39_N3") (pintype "bidirectional"))
      (node (ref "IC1") (pin "P19") (pinfunction "GND_46_P19") (pintype "bidirectional"))
      (node (ref "IC1") (pin "P8") (pinfunction "GND_45_P8") (pintype "bidirectional"))
      (node (ref "IC1") (pin "R11") (pinfunction "GND_49_R11") (pintype "bidirectional"))
      (node (ref "IC1") (pin "R13") (pinfunction "GND_50_R13") (pintype "bidirectional"))
      (node (ref "IC1") (pin "R3") (pinfunction "GND_47_R3") (pintype "bidirectional"))
      (node (ref "IC1") (pin "R9") (pinfunction "GND_48_R9") (pintype "bidirectional"))
      (node (ref "IC1") (pin "T20") (pinfunction "GND_51_T20") (pintype "bidirectional"))
      (node (ref "IC1") (pin "U3") (pinfunction "GND_52_U3") (pintype "bidirectional"))
      (node (ref "IC1") (pin "U5") (pinfunction "GNDA1_U5") (pintype "bidirectional"))
      (node (ref "IC1") (pin "V18") (pinfunction "GNDA4_V18") (pintype "bidirectional"))
      (node (ref "IC1") (pin "V20") (pinfunction "GND_53_V20") (pintype "bidirectional"))
      (node (ref "IC1") (pin "W3") (pinfunction "GND_54_W3") (pintype "bidirectional"))
      (node (ref "IC1") (pin "Y11") (pinfunction "GND_57_Y11") (pintype "bidirectional"))
      (node (ref "IC1") (pin "Y12") (pinfunction "GND_58_Y12") (pintype "bidirectional"))
      (node (ref "IC1") (pin "Y15") (pinfunction "GND_59_Y15") (pintype "bidirectional"))
      (node (ref "IC1") (pin "Y16") (pinfunction "GND_60_Y16") (pintype "bidirectional"))
      (node (ref "IC1") (pin "Y18") (pinfunction "GND_61_Y18") (pintype "bidirectional"))
      (node (ref "IC1") (pin "Y20") (pinfunction "GND_62_Y20") (pintype "bidirectional"))
      (node (ref "IC1") (pin "Y5") (pinfunction "GND_55_Y5") (pintype "bidirectional"))
      (node (ref "IC1") (pin "Y9") (pinfunction "GND_56_Y9") (pintype "bidirectional"))
      (node (ref "IC2") (pin "4") (pinfunction "GND_4") (pintype "bidirectional"))
      (node (ref "J1") (pin "10") (pinfunction "10_10") (pintype "passive"))
      (node (ref "J1") (pin "2") (pinfunction "2_2") (pintype "passive"))
      (node (ref "JP1") (pin "1") (pinfunction "1_1") (pintype "passive"))
      (node (ref "JP13") (pin "1") (pinfunction "1_1") (pintype "passive"))
      (node (ref "JP138") (pin "1") (pinfunction "1_1") (pintype "passive"))
      (node (ref "JP149") (pin "1") (pinfunction "1_1") (pintype "passive"))
      (node (ref "JP165") (pin "1") (pinfunction "1_1") (pintype "passive"))
      (node (ref "JP166") (pin "1") (pinfunction "1_1") (pintype "passive"))
      (node (ref "JP177") (pin "1") (pinfunction "1_1") (pintype "passive"))
      (node (ref "JP193") (pin "1") (pinfunction "1_1") (pintype "passive"))
      (node (ref "JP3") (pin "2") (pinfunction "2_2") (pintype "passive"))
      (node (ref "JP3") (pin "4") (pinfunction "4_4") (pintype "passive"))
      (node (ref "JP3") (pin "6") (pinfunction "6_6") (pintype "passive"))
      (node (ref "JP3") (pin "8") (pinfunction "8_8") (pintype "passive"))
      (node (ref "JP31") (pin "1") (pinfunction "1_1") (pintype "passive"))
      (node (ref "JP45") (pin "1") (pinfunction "1_1") (pintype "passive"))
      (node (ref "JP46") (pin "1") (pinfunction "1_1") (pintype "passive"))
      (node (ref "JP57") (pin "1") (pinfunction "1_1") (pintype "passive"))
      (node (ref "JP73") (pin "1") (pinfunction "1_1") (pintype "passive"))
      (node (ref "LED33") (pin "C") (pinfunction "C_C") (pintype "passive"))
      (node (ref "LED34") (pin "C") (pinfunction "C_C") (pintype "passive"))
      (node (ref "LED35") (pin "C") (pinfunction "C_C") (pintype "passive"))
      (node (ref "LED36") (pin "C") (pinfunction "C_C") (pintype "passive"))
      (node (ref "LED37") (pin "C") (pinfunction "C_C") (pintype "passive"))
      (node (ref "LED38") (pin "C") (pinfunction "C_C") (pintype "passive"))
      (node (ref "LED39") (pin "C") (pinfunction "C_C") (pintype "passive"))
      (node (ref "LED40") (pin "C") (pinfunction "C_C") (pintype "passive"))
      (node (ref "R4") (pin "P$2") (pinfunction "P$2_P$2") (pintype "bidirectional"))
      (node (ref "R6") (pin "P$2") (pinfunction "P$2_P$2") (pintype "bidirectional"))
      (node (ref "R8") (pin "P$2") (pinfunction "P$2_P$2") (pintype "bidirectional"))
      (node (ref "R9") (pin "P$2") (pinfunction "P$2_P$2") (pintype "bidirectional"))
      (node (ref "SW1") (pin "4") (pinfunction "B1_4") (pintype "bidirectional"))
      (node (ref "SW2") (pin "4") (pinfunction "B1_4") (pintype "bidirectional"))
      (node (ref "U1") (pin "P$2") (pinfunction "GND/ADJ_P$2") (pintype "bidirectional"))
      (node (ref "U2") (pin "P$2") (pinfunction "GND/ADJ_P$2") (pintype "bidirectional"))
      (node (ref "U3") (pin "P$2") (pinfunction "GND/ADJ_P$2") (pintype "bidirectional"))
      (node (ref "Y1") (pin "2") (pinfunction "GND_2") (pintype "bidirectional"))
    )
    (net (code "25") (name "IO1") (class "Default")
      (node (ref "C15") (pin "2") (pinfunction "2_2") (pintype "passive"))
      (node (ref "IC1") (pin "A3") (pinfunction "IO_1_A3") (pintype "bidirectional"))
      (node (ref "JP74") (pin "1") (pinfunction "1_1") (pintype "passive"))
      (node (ref "R1") (pin "P$1") (pinfunction "P$1_P$1") (pintype "bidirectional"))
      (node (ref "R45") (pin "P$1") (pinfunction "P$1_P$1") (pintype "bidirectional"))
      (node (ref "SW2") (pin "2") (pinfunction "A1_2") (pintype "bidirectional"))
    )
    (net (code "26") (name "IO2") (class "Default")
      (node (ref "IC1") (pin "A4") (pinfunction "IO_2_A4") (pintype "bidirectional"))
      (node (ref "JP76") (pin "1") (pinfunction "1_1") (pintype "passive"))
      (node (ref "R44") (pin "P$1") (pinfunction "P$1_P$1") (pintype "bidirectional"))
    )
    (net (code "27") (name "IO3") (class "Default")
      (node (ref "IC1") (pin "A5") (pinfunction "IO_3_A5") (pintype "bidirectional"))
      (node (ref "JP75") (pin "1") (pinfunction "1_1") (pintype "passive"))
      (node (ref "R43") (pin "P$1") (pinfunction "P$1_P$1") (pintype "bidirectional"))
    )
    (net (code "28") (name "IO4") (class "Default")
      (node (ref "IC1") (pin "A6") (pinfunction "IO_4_A6") (pintype "bidirectional"))
      (node (ref "JP77") (pin "1") (pinfunction "1_1") (pintype "passive"))
      (node (ref "R42") (pin "P$1") (pinfunction "P$1_P$1") (pintype "bidirectional"))
    )
    (net (code "29") (name "IO5") (class "Default")
      (node (ref "IC1") (pin "A7") (pinfunction "IO_5_A7") (pintype "bidirectional"))
      (node (ref "JP78") (pin "1") (pinfunction "1_1") (pintype "passive"))
      (node (ref "R41") (pin "P$1") (pinfunction "P$1_P$1") (pintype "bidirectional"))
    )
    (net (code "30") (name "IO6") (class "Default")
      (node (ref "IC1") (pin "A8") (pinfunction "IO_6_A8") (pintype "bidirectional"))
      (node (ref "JP80") (pin "1") (pinfunction "1_1") (pintype "passive"))
      (node (ref "R40") (pin "P$1") (pinfunction "P$1_P$1") (pintype "bidirectional"))
    )
    (net (code "31") (name "IO7") (class "Default")
      (node (ref "IC1") (pin "A9") (pinfunction "IO_7_A9") (pintype "bidirectional"))
      (node (ref "JP79") (pin "1") (pinfunction "1_1") (pintype "passive"))
    )
    (net (code "32") (name "IO8") (class "Default")
      (node (ref "IC1") (pin "A10") (pinfunction "IO_8_A10") (pintype "bidirectional"))
      (node (ref "JP81") (pin "1") (pinfunction "1_1") (pintype "passive"))
    )
    (net (code "33") (name "IO9") (class "Default")
      (node (ref "IC1") (pin "A13") (pinfunction "IO_9_A13") (pintype "bidirectional"))
      (node (ref "JP82") (pin "1") (pinfunction "1_1") (pintype "passive"))
    )
    (net (code "34") (name "IO10") (class "Default")
      (node (ref "IC1") (pin "A14") (pinfunction "IO_10_A14") (pintype "bidirectional"))
      (node (ref "JP84") (pin "1") (pinfunction "1_1") (pintype "passive"))
    )
    (net (code "35") (name "IO11") (class "Default")
      (node (ref "IC1") (pin "A15") (pinfunction "IO_11_A15") (pintype "bidirectional"))
      (node (ref "JP83") (pin "1") (pinfunction "1_1") (pintype "passive"))
    )
    (net (code "36") (name "IO12") (class "Default")
      (node (ref "IC1") (pin "A16") (pinfunction "IO_12_A16") (pintype "bidirectional"))
      (node (ref "JP85") (pin "1") (pinfunction "1_1") (pintype "passive"))
    )
    (net (code "37") (name "IO13") (class "Default")
      (node (ref "IC1") (pin "A17") (pinfunction "IO_13_A17") (pintype "bidirectional"))
      (node (ref "JP86") (pin "1") (pinfunction "1_1") (pintype "passive"))
    )
    (net (code "38") (name "IO14") (class "Default")
      (node (ref "IC1") (pin "A18") (pinfunction "IO_14_A18") (pintype "bidirectional"))
      (node (ref "JP88") (pin "1") (pinfunction "1_1") (pintype "passive"))
    )
    (net (code "39") (name "IO15") (class "Default")
      (node (ref "IC1") (pin "A19") (pinfunction "IO_15_A19") (pintype "bidirectional"))
      (node (ref "JP87") (pin "1") (pinfunction "1_1") (pintype "passive"))
    )
    (net (code "40") (name "IO16") (class "Default")
      (node (ref "IC1") (pin "A20") (pinfunction "IO_16_A20") (pintype "bidirectional"))
      (node (ref "JP89") (pin "1") (pinfunction "1_1") (pintype "passive"))
    )
    (net (code "41") (name "IO17") (class "Default")
      (node (ref "IC1") (pin "B1") (pinfunction "IO_17_B1") (pintype "bidirectional"))
      (node (ref "JP90") (pin "1") (pinfunction "1_1") (pintype "passive"))
    )
    (net (code "42") (name "IO18") (class "Default")
      (node (ref "IC1") (pin "B2") (pinfunction "IO_18_B2") (pintype "bidirectional"))
      (node (ref "JP92") (pin "1") (pinfunction "1_1") (pintype "passive"))
    )
    (net (code "43") (name "IO19") (class "Default")
      (node (ref "IC1") (pin "B3") (pinfunction "IO_19_B3") (pintype "bidirectional"))
      (node (ref "JP91") (pin "1") (pinfunction "1_1") (pintype "passive"))
    )
    (net (code "44") (name "IO20") (class "Default")
      (node (ref "IC1") (pin "B4") (pinfunction "IO_20_B4") (pintype "bidirectional"))
      (node (ref "JP93") (pin "1") (pinfunction "1_1") (pintype "passive"))
    )
    (net (code "45") (name "IO21") (class "Default")
      (node (ref "IC1") (pin "B5") (pinfunction "IO_21_B5") (pintype "bidirectional"))
      (node (ref "JP94") (pin "1") (pinfunction "1_1") (pintype "passive"))
    )
    (net (code "46") (name "IO22") (class "Default")
      (node (ref "IC1") (pin "B6") (pinfunction "IO_22_B6") (pintype "bidirectional"))
      (node (ref "JP96") (pin "1") (pinfunction "1_1") (pintype "passive"))
    )
    (net (code "47") (name "IO23") (class "Default")
      (node (ref "IC1") (pin "B7") (pinfunction "IO_23_B7") (pintype "bidirectional"))
      (node (ref "JP95") (pin "1") (pinfunction "1_1") (pintype "passive"))
    )
    (net (code "48") (name "IO24") (class "Default")
      (node (ref "IC1") (pin "B8") (pinfunction "IO_24_B8") (pintype "bidirectional"))
      (node (ref "JP97") (pin "1") (pinfunction "1_1") (pintype "passive"))
    )
    (net (code "49") (name "IO25") (class "Default")
      (node (ref "IC1") (pin "B9") (pinfunction "IO_25_B9") (pintype "bidirectional"))
      (node (ref "JP98") (pin "1") (pinfunction "1_1") (pintype "passive"))
    )
    (net (code "50") (name "IO26") (class "Default")
      (node (ref "IC1") (pin "B10") (pinfunction "IO_26_B10") (pintype "bidirectional"))
      (node (ref "JP100") (pin "1") (pinfunction "1_1") (pintype "passive"))
    )
    (net (code "51") (name "IO27") (class "Default")
      (node (ref "IC1") (pin "B13") (pinfunction "IO_27_B13") (pintype "bidirectional"))
      (node (ref "JP99") (pin "1") (pinfunction "1_1") (pintype "passive"))
    )
    (net (code "52") (name "IO28") (class "Default")
      (node (ref "IC1") (pin "B14") (pinfunction "IO_28_B14") (pintype "bidirectional"))
      (node (ref "JP101") (pin "1") (pinfunction "1_1") (pintype "passive"))
    )
    (net (code "53") (name "IO29") (class "Default")
      (node (ref "IC1") (pin "B15") (pinfunction "IO_29_B15") (pintype "bidirectional"))
      (node (ref "JP102") (pin "1") (pinfunction "1_1") (pintype "passive"))
    )
    (net (code "54") (name "IO30") (class "Default")
      (node (ref "IC1") (pin "B16") (pinfunction "IO_30_B16") (pintype "bidirectional"))
      (node (ref "JP104") (pin "1") (pinfunction "1_1") (pintype "passive"))
    )
    (net (code "55") (name "IO31") (class "Default")
      (node (ref "IC1") (pin "B17") (pinfunction "IO_31_B17") (pintype "bidirectional"))
      (node (ref "JP103") (pin "1") (pinfunction "1_1") (pintype "passive"))
    )
    (net (code "56") (name "IO32") (class "Default")
      (node (ref "IC1") (pin "B18") (pinfunction "IO_32_B18") (pintype "bidirectional"))
      (node (ref "JP105") (pin "1") (pinfunction "1_1") (pintype "passive"))
    )
    (net (code "57") (name "IO33") (class "Default")
      (node (ref "IC1") (pin "B19") (pinfunction "IO_33_B19") (pintype "bidirectional"))
      (node (ref "JP4") (pin "1") (pinfunction "1_1") (pintype "passive"))
    )
    (net (code "58") (name "IO34") (class "Default")
      (node (ref "IC1") (pin "B20") (pinfunction "IO_34_B20") (pintype "bidirectional"))
      (node (ref "JP2") (pin "1") (pinfunction "1_1") (pintype "passive"))
    )
    (net (code "59") (name "IO35") (class "Default")
      (node (ref "IC1") (pin "B21") (pinfunction "IO_35_B21") (pintype "bidirectional"))
      (node (ref "JP5") (pin "1") (pinfunction "1_1") (pintype "passive"))
    )
    (net (code "60") (name "IO36") (class "Default")
      (node (ref "IC1") (pin "B22") (pinfunction "IO_36_B22") (pintype "bidirectional"))
      (node (ref "JP6") (pin "1") (pinfunction "1_1") (pintype "passive"))
    )
    (net (code "61") (name "IO37") (class "Default")
      (node (ref "IC1") (pin "C1") (pinfunction "IO_37_C1") (pintype "bidirectional"))
      (node (ref "JP8") (pin "1") (pinfunction "1_1") (pintype "passive"))
    )
    (net (code "62") (name "IO38") (class "Default")
      (node (ref "IC1") (pin "C2") (pinfunction "IO_38_C2") (pintype "bidirectional"))
      (node (ref "JP7") (pin "1") (pinfunction "1_1") (pintype "passive"))
    )
    (net (code "63") (name "IO39") (class "Default")
      (node (ref "IC1") (pin "C3") (pinfunction "IO_39_C3") (pintype "bidirectional"))
      (node (ref "JP9") (pin "1") (pinfunction "1_1") (pintype "passive"))
    )
    (net (code "64") (name "IO40") (class "Default")
      (node (ref "IC1") (pin "C4") (pinfunction "IO_40_C4") (pintype "bidirectional"))
      (node (ref "JP10") (pin "1") (pinfunction "1_1") (pintype "passive"))
    )
    (net (code "65") (name "IO41") (class "Default")
      (node (ref "IC1") (pin "C6") (pinfunction "IO_41_C6") (pintype "bidirectional"))
      (node (ref "JP12") (pin "1") (pinfunction "1_1") (pintype "passive"))
    )
    (net (code "66") (name "IO42") (class "Default")
      (node (ref "IC1") (pin "C7") (pinfunction "IO_42_C7") (pintype "bidirectional"))
      (node (ref "JP11") (pin "1") (pinfunction "1_1") (pintype "passive"))
    )
    (net (code "67") (name "IO43") (class "Default")
      (node (ref "IC1") (pin "C8") (pinfunction "IO_43_C8") (pintype "bidirectional"))
      (node (ref "JP14") (pin "1") (pinfunction "1_1") (pintype "passive"))
    )
    (net (code "68") (name "IO44") (class "Default")
      (node (ref "IC1") (pin "C10") (pinfunction "IO_44_C10") (pintype "bidirectional"))
      (node (ref "JP15") (pin "1") (pinfunction "1_1") (pintype "passive"))
    )
    (net (code "69") (name "IO45") (class "Default")
      (node (ref "IC1") (pin "C13") (pinfunction "IO_45_C13") (pintype "bidirectional"))
      (node (ref "JP32") (pin "1") (pinfunction "1_1") (pintype "passive"))
    )
    (net (code "70") (name "IO46") (class "Default")
      (node (ref "IC1") (pin "C15") (pinfunction "IO_46_C15") (pintype "bidirectional"))
      (node (ref "JP34") (pin "1") (pinfunction "1_1") (pintype "passive"))
    )
    (net (code "71") (name "IO47") (class "Default")
      (node (ref "IC1") (pin "C17") (pinfunction "IO_47_C17") (pintype "bidirectional"))
      (node (ref "JP33") (pin "1") (pinfunction "1_1") (pintype "passive"))
    )
    (net (code "72") (name "IO48") (class "Default")
      (node (ref "IC1") (pin "C19") (pinfunction "IO_48_C19") (pintype "bidirectional"))
      (node (ref "JP35") (pin "1") (pinfunction "1_1") (pintype "passive"))
    )
    (net (code "73") (name "IO49") (class "Default")
      (node (ref "IC1") (pin "C20") (pinfunction "IO_49_C20") (pintype "bidirectional"))
      (node (ref "JP36") (pin "1") (pinfunction "1_1") (pintype "passive"))
    )
    (net (code "74") (name "IO50") (class "Default")
      (node (ref "IC1") (pin "C21") (pinfunction "IO_50_C21") (pintype "bidirectional"))
      (node (ref "JP38") (pin "1") (pinfunction "1_1") (pintype "passive"))
    )
    (net (code "75") (name "IO51") (class "Default")
      (node (ref "IC1") (pin "C22") (pinfunction "IO_51_C22") (pintype "bidirectional"))
      (node (ref "JP37") (pin "1") (pinfunction "1_1") (pintype "passive"))
    )
    (net (code "76") (name "IO53") (class "Default")
      (node (ref "IC1") (pin "D2") (pinfunction "IO_53_D2") (pintype "bidirectional"))
      (node (ref "JP40") (pin "1") (pinfunction "1_1") (pintype "passive"))
    )
    (net (code "77") (name "IO54") (class "Default")
      (node (ref "IC1") (pin "D6") (pinfunction "IO_54_D6") (pintype "bidirectional"))
      (node (ref "JP42") (pin "1") (pinfunction "1_1") (pintype "passive"))
    )
    (net (code "78") (name "IO55") (class "Default")
      (node (ref "IC1") (pin "D7") (pinfunction "IO_55_D7") (pintype "bidirectional"))
      (node (ref "JP41") (pin "1") (pinfunction "1_1") (pintype "passive"))
    )
    (net (code "79") (name "IO56") (class "Default")
      (node (ref "IC1") (pin "D10") (pinfunction "IO_56_D10") (pintype "bidirectional"))
      (node (ref "JP43") (pin "1") (pinfunction "1_1") (pintype "passive"))
    )
    (net (code "80") (name "IO57") (class "Default")
      (node (ref "IC1") (pin "D13") (pinfunction "IO_57_D13") (pintype "bidirectional"))
      (node (ref "JP44") (pin "1") (pinfunction "1_1") (pintype "passive"))
    )
    (net (code "81") (name "IO58") (class "Default")
      (node (ref "IC1") (pin "D15") (pinfunction "IO_58_D15") (pintype "bidirectional"))
      (node (ref "JP48") (pin "1") (pinfunction "1_1") (pintype "passive"))
    )
    (net (code "82") (name "IO59") (class "Default")
      (node (ref "IC1") (pin "D17") (pinfunction "IO_59_D17") (pintype "bidirectional"))
      (node (ref "JP47") (pin "1") (pinfunction "1_1") (pintype "passive"))
    )
    (net (code "83") (name "IO60") (class "Default")
      (node (ref "IC1") (pin "D19") (pinfunction "IO_60_D19") (pintype "bidirectional"))
      (node (ref "JP49") (pin "1") (pinfunction "1_1") (pintype "passive"))
    )
    (net (code "84") (name "IO61") (class "Default")
      (node (ref "IC1") (pin "D20") (pinfunction "IO_61_D20") (pintype "bidirectional"))
      (node (ref "JP50") (pin "1") (pinfunction "1_1") (pintype "passive"))
    )
    (net (code "85") (name "IO62") (class "Default")
      (node (ref "IC1") (pin "D21") (pinfunction "IO_62_D21") (pintype "bidirectional"))
      (node (ref "JP52") (pin "1") (pinfunction "1_1") (pintype "passive"))
    )
    (net (code "86") (name "IO63") (class "Default")
      (node (ref "IC1") (pin "D22") (pinfunction "IO_63_D22") (pintype "bidirectional"))
      (node (ref "JP51") (pin "1") (pinfunction "1_1") (pintype "passive"))
    )
    (net (code "87") (name "IO64") (class "Default")
      (node (ref "IC1") (pin "E1") (pinfunction "IO_64_E1") (pintype "bidirectional"))
      (node (ref "JP53") (pin "1") (pinfunction "1_1") (pintype "passive"))
    )
    (net (code "88") (name "IO66") (class "Default")
      (node (ref "IC1") (pin "E3") (pinfunction "IO_66_E3") (pintype "bidirectional"))
      (node (ref "JP56") (pin "1") (pinfunction "1_1") (pintype "passive"))
    )
    (net (code "89") (name "IO67") (class "Default")
      (node (ref "IC1") (pin "E4") (pinfunction "IO_67_E4") (pintype "bidirectional"))
      (node (ref "JP55") (pin "1") (pinfunction "1_1") (pintype "passive"))
    )
    (net (code "90") (name "IO68") (class "Default")
      (node (ref "IC1") (pin "E5") (pinfunction "IO_68_E5") (pintype "bidirectional"))
      (node (ref "JP58") (pin "1") (pinfunction "1_1") (pintype "passive"))
    )
    (net (code "91") (name "IO69") (class "Default")
      (node (ref "IC1") (pin "E6") (pinfunction "IO_69_E6") (pintype "bidirectional"))
      (node (ref "JP59") (pin "1") (pinfunction "1_1") (pintype "passive"))
    )
    (net (code "92") (name "IO70") (class "Default")
      (node (ref "IC1") (pin "E7") (pinfunction "IO_70_E7") (pintype "bidirectional"))
      (node (ref "JP60") (pin "1") (pinfunction "1_1") (pintype "passive"))
    )
    (net (code "93") (name "IO71") (class "Default")
      (node (ref "IC1") (pin "E9") (pinfunction "IO_71_E9") (pintype "bidirectional"))
      (node (ref "JP62") (pin "1") (pinfunction "1_1") (pintype "passive"))
    )
    (net (code "94") (name "IO72") (class "Default")
      (node (ref "IC1") (pin "E10") (pinfunction "IO_72_E10") (pintype "bidirectional"))
      (node (ref "JP61") (pin "1") (pinfunction "1_1") (pintype "passive"))
    )
    (net (code "95") (name "IO73") (class "Default")
      (node (ref "IC1") (pin "E11") (pinfunction "IO_73_E11") (pintype "bidirectional"))
      (node (ref "JP63") (pin "1") (pinfunction "1_1") (pintype "passive"))
    )
    (net (code "96") (name "IO74") (class "Default")
      (node (ref "IC1") (pin "E12") (pinfunction "IO_74_E12") (pintype "bidirectional"))
      (node (ref "JP64") (pin "1") (pinfunction "1_1") (pintype "passive"))
    )
    (net (code "97") (name "IO75") (class "Default")
      (node (ref "IC1") (pin "E13") (pinfunction "IO_75_E13") (pintype "bidirectional"))
      (node (ref "JP66") (pin "1") (pinfunction "1_1") (pintype "passive"))
    )
    (net (code "98") (name "IO76") (class "Default")
      (node (ref "IC1") (pin "E14") (pinfunction "IO_76_E14") (pintype "bidirectional"))
      (node (ref "JP65") (pin "1") (pinfunction "1_1") (pintype "passive"))
    )
    (net (code "99") (name "IO77") (class "Default")
      (node (ref "IC1") (pin "E15") (pinfunction "IO_77_E15") (pintype "bidirectional"))
      (node (ref "JP67") (pin "1") (pinfunction "1_1") (pintype "passive"))
    )
    (net (code "100") (name "IO78") (class "Default")
      (node (ref "IC1") (pin "E16") (pinfunction "IO_78_E16") (pintype "bidirectional"))
      (node (ref "JP68") (pin "1") (pinfunction "1_1") (pintype "passive"))
    )
    (net (code "101") (name "IO79") (class "Default")
      (node (ref "IC1") (pin "E21") (pinfunction "IO_79_E21") (pintype "bidirectional"))
      (node (ref "JP70") (pin "1") (pinfunction "1_1") (pintype "passive"))
    )
    (net (code "102") (name "IO80") (class "Default")
      (node (ref "IC1") (pin "E22") (pinfunction "IO_80_E22") (pintype "bidirectional"))
      (node (ref "JP69") (pin "1") (pinfunction "1_1") (pintype "passive"))
    )
    (net (code "103") (name "IO81") (class "Default")
      (node (ref "IC1") (pin "F1") (pinfunction "IO_81_F1") (pintype "bidirectional"))
      (node (ref "JP71") (pin "1") (pinfunction "1_1") (pintype "passive"))
    )
    (net (code "104") (name "IO82") (class "Default")
      (node (ref "IC1") (pin "F2") (pinfunction "IO_82_F2") (pintype "bidirectional"))
      (node (ref "JP72") (pin "1") (pinfunction "1_1") (pintype "passive"))
    )
    (net (code "105") (name "IO83") (class "Default")
      (node (ref "IC1") (pin "F7") (pinfunction "IO_83_F7") (pintype "bidirectional"))
      (node (ref "JP140") (pin "1") (pinfunction "1_1") (pintype "passive"))
    )
    (net (code "106") (name "IO84") (class "Default")
      (node (ref "IC1") (pin "F8") (pinfunction "IO_84_F8") (pintype "bidirectional"))
      (node (ref "JP139") (pin "1") (pinfunction "1_1") (pintype "passive"))
    )
    (net (code "107") (name "IO85") (class "Default")
      (node (ref "IC1") (pin "F9") (pinfunction "IO_85_F9") (pintype "bidirectional"))
      (node (ref "JP141") (pin "1") (pinfunction "1_1") (pintype "passive"))
    )
    (net (code "108") (name "IO86") (class "Default")
      (node (ref "IC1") (pin "F10") (pinfunction "IO_86_F10") (pintype "bidirectional"))
      (node (ref "JP142") (pin "1") (pinfunction "1_1") (pintype "passive"))
    )
    (net (code "109") (name "IO87") (class "Default")
      (node (ref "IC1") (pin "F11") (pinfunction "IO_87_F11") (pintype "bidirectional"))
      (node (ref "JP144") (pin "1") (pinfunction "1_1") (pintype "passive"))
    )
    (net (code "110") (name "IO88") (class "Default")
      (node (ref "IC1") (pin "F13") (pinfunction "IO_88_F13") (pintype "bidirectional"))
      (node (ref "JP143") (pin "1") (pinfunction "1_1") (pintype "passive"))
    )
    (net (code "111") (name "IO89") (class "Default")
      (node (ref "IC1") (pin "F14") (pinfunction "IO_89_F14") (pintype "bidirectional"))
      (node (ref "JP145") (pin "1") (pinfunction "1_1") (pintype "passive"))
    )
    (net (code "112") (name "IO90") (class "Default")
      (node (ref "IC1") (pin "F15") (pinfunction "IO_90_F15") (pintype "bidirectional"))
      (node (ref "JP146") (pin "1") (pinfunction "1_1") (pintype "passive"))
    )
    (net (code "113") (name "IO91") (class "Default")
      (node (ref "IC1") (pin "F16") (pinfunction "IO_91_F16") (pintype "bidirectional"))
      (node (ref "JP148") (pin "1") (pinfunction "1_1") (pintype "passive"))
    )
    (net (code "114") (name "IO92") (class "Default")
      (node (ref "IC1") (pin "F17") (pinfunction "IO_92_F17") (pintype "bidirectional"))
      (node (ref "JP147") (pin "1") (pinfunction "1_1") (pintype "passive"))
    )
    (net (code "115") (name "IO93") (class "Default")
      (node (ref "IC1") (pin "F19") (pinfunction "IO_93_F19") (pintype "bidirectional"))
      (node (ref "JP150") (pin "1") (pinfunction "1_1") (pintype "passive"))
    )
    (net (code "116") (name "IO94") (class "Default")
      (node (ref "IC1") (pin "F20") (pinfunction "IO_94_F20") (pintype "bidirectional"))
      (node (ref "JP151") (pin "1") (pinfunction "1_1") (pintype "passive"))
    )
    (net (code "117") (name "IO95") (class "Default")
      (node (ref "IC1") (pin "F21") (pinfunction "IO_95_F21") (pintype "bidirectional"))
      (node (ref "JP152") (pin "1") (pinfunction "1_1") (pintype "passive"))
    )
    (net (code "118") (name "IO96") (class "Default")
      (node (ref "IC1") (pin "F22") (pinfunction "IO_96_F22") (pintype "bidirectional"))
      (node (ref "JP154") (pin "1") (pinfunction "1_1") (pintype "passive"))
    )
    (net (code "119") (name "IO97") (class "Default")
      (node (ref "IC1") (pin "G3") (pinfunction "IO_97_G3") (pintype "bidirectional"))
      (node (ref "JP153") (pin "1") (pinfunction "1_1") (pintype "passive"))
    )
    (net (code "120") (name "IO98") (class "Default")
      (node (ref "IC1") (pin "G4") (pinfunction "IO_98_G4") (pintype "bidirectional"))
      (node (ref "JP155") (pin "1") (pinfunction "1_1") (pintype "passive"))
    )
    (net (code "121") (name "IO99") (class "Default")
      (node (ref "IC1") (pin "G5") (pinfunction "IO_99_G5") (pintype "bidirectional"))
      (node (ref "JP156") (pin "1") (pinfunction "1_1") (pintype "passive"))
    )
    (net (code "122") (name "IO100") (class "Default")
      (node (ref "IC1") (pin "G7") (pinfunction "IO_100_G7") (pintype "bidirectional"))
      (node (ref "JP158") (pin "1") (pinfunction "1_1") (pintype "passive"))
    )
    (net (code "123") (name "IO101") (class "Default")
      (node (ref "IC1") (pin "G8") (pinfunction "IO_101_G8") (pintype "bidirectional"))
      (node (ref "JP157") (pin "1") (pinfunction "1_1") (pintype "passive"))
    )
    (net (code "124") (name "IO102") (class "Default")
      (node (ref "IC1") (pin "G9") (pinfunction "IO_102_G9") (pintype "bidirectional"))
      (node (ref "JP159") (pin "1") (pinfunction "1_1") (pintype "passive"))
    )
    (net (code "125") (name "IO103") (class "Default")
      (node (ref "IC1") (pin "G10") (pinfunction "IO_103_G10") (pintype "bidirectional"))
      (node (ref "JP160") (pin "1") (pinfunction "1_1") (pintype "passive"))
    )
    (net (code "126") (name "IO104") (class "Default")
      (node (ref "IC1") (pin "G11") (pinfunction "IO_104_G11") (pintype "bidirectional"))
      (node (ref "JP162") (pin "1") (pinfunction "1_1") (pintype "passive"))
    )
    (net (code "127") (name "IO105") (class "Default")
      (node (ref "IC1") (pin "G13") (pinfunction "IO_105_G13") (pintype "bidirectional"))
      (node (ref "JP161") (pin "1") (pinfunction "1_1") (pintype "passive"))
    )
    (net (code "128") (name "IO106") (class "Default")
      (node (ref "IC1") (pin "G14") (pinfunction "IO_106_G14") (pintype "bidirectional"))
      (node (ref "JP163") (pin "1") (pinfunction "1_1") (pintype "passive"))
    )
    (net (code "129") (name "IO107") (class "Default")
      (node (ref "IC1") (pin "G15") (pinfunction "IO_107_G15") (pintype "bidirectional"))
      (node (ref "JP164") (pin "1") (pinfunction "1_1") (pintype "passive"))
    )
    (net (code "130") (name "IO108") (class "Default")
      (node (ref "IC1") (pin "G16") (pinfunction "IO_108_G16") (pintype "bidirectional"))
      (node (ref "JP168") (pin "1") (pinfunction "1_1") (pintype "passive"))
    )
    (net (code "131") (name "IO109") (class "Default")
      (node (ref "IC1") (pin "G17") (pinfunction "IO_109_G17") (pintype "bidirectional"))
      (node (ref "JP167") (pin "1") (pinfunction "1_1") (pintype "passive"))
    )
    (net (code "132") (name "IO110") (class "Default")
      (node (ref "IC1") (pin "G18") (pinfunction "IO_110_G18") (pintype "bidirectional"))
      (node (ref "JP169") (pin "1") (pinfunction "1_1") (pintype "passive"))
    )
    (net (code "133") (name "IO111") (class "Default")
      (node (ref "IC1") (pin "H1") (pinfunction "IO_111_H1") (pintype "bidirectional"))
      (node (ref "JP170") (pin "1") (pinfunction "1_1") (pintype "passive"))
    )
    (net (code "134") (name "IO112") (class "Default")
      (node (ref "IC1") (pin "H2") (pinfunction "IO_112_H2") (pintype "bidirectional"))
      (node (ref "JP172") (pin "1") (pinfunction "1_1") (pintype "passive"))
    )
    (net (code "135") (name "IO113") (class "Default")
      (node (ref "IC1") (pin "H5") (pinfunction "IO_113_H5") (pintype "bidirectional"))
      (node (ref "JP171") (pin "1") (pinfunction "1_1") (pintype "passive"))
    )
    (net (code "136") (name "IO114") (class "Default")
      (node (ref "IC1") (pin "H6") (pinfunction "IO_114_H6") (pintype "bidirectional"))
      (node (ref "JP173") (pin "1") (pinfunction "1_1") (pintype "passive"))
    )
    (net (code "137") (name "IO115") (class "Default")
      (node (ref "IC1") (pin "H7") (pinfunction "IO_115_H7") (pintype "bidirectional"))
      (node (ref "JP174") (pin "1") (pinfunction "1_1") (pintype "passive"))
    )
    (net (code "138") (name "IO116") (class "Default")
      (node (ref "IC1") (pin "H8") (pinfunction "IO_116_H8") (pintype "bidirectional"))
      (node (ref "JP176") (pin "1") (pinfunction "1_1") (pintype "passive"))
    )
    (net (code "139") (name "IO117") (class "Default")
      (node (ref "IC1") (pin "H10") (pinfunction "IO_117_H10") (pintype "bidirectional"))
      (node (ref "JP175") (pin "1") (pinfunction "1_1") (pintype "passive"))
    )
    (net (code "140") (name "IO118") (class "Default")
      (node (ref "IC1") (pin "H11") (pinfunction "IO_118_H11") (pintype "bidirectional"))
      (node (ref "JP178") (pin "1") (pinfunction "1_1") (pintype "passive"))
    )
    (net (code "141") (name "IO119") (class "Default")
      (node (ref "IC1") (pin "H14") (pinfunction "IO_119_H14") (pintype "bidirectional"))
      (node (ref "JP179") (pin "1") (pinfunction "1_1") (pintype "passive"))
    )
    (net (code "142") (name "IO120") (class "Default")
      (node (ref "IC1") (pin "H15") (pinfunction "IO_120_H15") (pintype "bidirectional"))
      (node (ref "JP180") (pin "1") (pinfunction "1_1") (pintype "passive"))
    )
    (net (code "143") (name "IO121") (class "Default")
      (node (ref "IC1") (pin "H16") (pinfunction "IO_121_H16") (pintype "bidirectional"))
      (node (ref "JP182") (pin "1") (pinfunction "1_1") (pintype "passive"))
    )
    (net (code "144") (name "IO122") (class "Default")
      (node (ref "IC1") (pin "H17") (pinfunction "IO_122_H17") (pintype "bidirectional"))
      (node (ref "JP181") (pin "1") (pinfunction "1_1") (pintype "passive"))
    )
    (net (code "145") (name "IO123") (class "Default")
      (node (ref "IC1") (pin "H18") (pinfunction "IO_123_H18") (pintype "bidirectional"))
      (node (ref "JP183") (pin "1") (pinfunction "1_1") (pintype "passive"))
    )
    (net (code "146") (name "IO124") (class "Default")
      (node (ref "IC1") (pin "H19") (pinfunction "IO_124_H19") (pintype "bidirectional"))
      (node (ref "JP184") (pin "1") (pinfunction "1_1") (pintype "passive"))
    )
    (net (code "147") (name "IO125") (class "Default")
      (node (ref "IC1") (pin "H20") (pinfunction "IO_125_H20") (pintype "bidirectional"))
      (node (ref "JP186") (pin "1") (pinfunction "1_1") (pintype "passive"))
    )
    (net (code "148") (name "IO126") (class "Default")
      (node (ref "IC1") (pin "H21") (pinfunction "IO_126_H21") (pintype "bidirectional"))
      (node (ref "JP185") (pin "1") (pinfunction "1_1") (pintype "passive"))
    )
    (net (code "149") (name "IO127") (class "Default")
      (node (ref "IC1") (pin "H22") (pinfunction "IO_127_H22") (pintype "bidirectional"))
      (node (ref "JP187") (pin "1") (pinfunction "1_1") (pintype "passive"))
    )
    (net (code "150") (name "IO128") (class "Default")
      (node (ref "IC1") (pin "J1") (pinfunction "IO_128_J1") (pintype "bidirectional"))
      (node (ref "JP188") (pin "1") (pinfunction "1_1") (pintype "passive"))
    )
    (net (code "151") (name "IO129") (class "Default")
      (node (ref "IC1") (pin "J2") (pinfunction "IO_129_J2") (pintype "bidirectional"))
      (node (ref "JP190") (pin "1") (pinfunction "1_1") (pintype "passive"))
    )
    (net (code "152") (name "IO130") (class "Default")
      (node (ref "IC1") (pin "J3") (pinfunction "IO_130_J3") (pintype "bidirectional"))
      (node (ref "JP189") (pin "1") (pinfunction "1_1") (pintype "passive"))
    )
    (net (code "153") (name "IO131") (class "Default")
      (node (ref "IC1") (pin "J4") (pinfunction "IO_131_J4") (pintype "bidirectional"))
      (node (ref "JP191") (pin "1") (pinfunction "1_1") (pintype "passive"))
    )
    (net (code "154") (name "IO132") (class "Default")
      (node (ref "IC1") (pin "J5") (pinfunction "IO_132_J5") (pintype "bidirectional"))
      (node (ref "JP192") (pin "1") (pinfunction "1_1") (pintype "passive"))
    )
    (net (code "155") (name "IO133") (class "Default")
      (node (ref "IC1") (pin "J6") (pinfunction "IO_133_J6") (pintype "bidirectional"))
      (node (ref "JP106") (pin "1") (pinfunction "1_1") (pintype "passive"))
    )
    (net (code "156") (name "IO134") (class "Default")
      (node (ref "IC1") (pin "J7") (pinfunction "IO_134_J7") (pintype "bidirectional"))
      (node (ref "JP108") (pin "1") (pinfunction "1_1") (pintype "passive"))
    )
    (net (code "157") (name "IO135") (class "Default")
      (node (ref "IC1") (pin "J8") (pinfunction "IO_135_J8") (pintype "bidirectional"))
      (node (ref "JP107") (pin "1") (pinfunction "1_1") (pintype "passive"))
    )
    (net (code "158") (name "IO136") (class "Default")
      (node (ref "IC1") (pin "J17") (pinfunction "IO_136_J17") (pintype "bidirectional"))
      (node (ref "JP109") (pin "1") (pinfunction "1_1") (pintype "passive"))
    )
    (net (code "159") (name "IO137") (class "Default")
      (node (ref "IC1") (pin "J18") (pinfunction "IO_137_J18") (pintype "bidirectional"))
      (node (ref "JP110") (pin "1") (pinfunction "1_1") (pintype "passive"))
    )
    (net (code "160") (name "IO138") (class "Default")
      (node (ref "IC1") (pin "J21") (pinfunction "IO_138_J21") (pintype "bidirectional"))
      (node (ref "JP112") (pin "1") (pinfunction "1_1") (pintype "passive"))
    )
    (net (code "161") (name "IO139") (class "Default")
      (node (ref "IC1") (pin "J22") (pinfunction "IO_139_J22") (pintype "bidirectional"))
      (node (ref "JP111") (pin "1") (pinfunction "1_1") (pintype "passive"))
    )
    (net (code "162") (name "IO141") (class "Default")
      (node (ref "IC1") (pin "K7") (pinfunction "IO_141_K7") (pintype "bidirectional"))
      (node (ref "JP114") (pin "1") (pinfunction "1_1") (pintype "passive"))
    )
    (net (code "163") (name "IO142") (class "Default")
      (node (ref "IC1") (pin "K8") (pinfunction "IO_142_K8") (pintype "bidirectional"))
      (node (ref "JP116") (pin "1") (pinfunction "1_1") (pintype "passive"))
    )
    (net (code "164") (name "IO143") (class "Default")
      (node (ref "IC1") (pin "K17") (pinfunction "IO_143_K17") (pintype "bidirectional"))
      (node (ref "JP115") (pin "1") (pinfunction "1_1") (pintype "passive"))
    )
    (net (code "165") (name "IO144") (class "Default")
      (node (ref "IC1") (pin "K18") (pinfunction "IO_144_K18") (pintype "bidirectional"))
      (node (ref "JP117") (pin "1") (pinfunction "1_1") (pintype "passive"))
    )
    (net (code "166") (name "IO145") (class "Default")
      (node (ref "IC1") (pin "K19") (pinfunction "IO_145_K19") (pintype "bidirectional"))
      (node (ref "JP118") (pin "1") (pinfunction "1_1") (pintype "passive"))
    )
    (net (code "167") (name "IO146") (class "Default")
      (node (ref "IC1") (pin "K21") (pinfunction "IO_146_K21") (pintype "bidirectional"))
      (node (ref "JP120") (pin "1") (pinfunction "1_1") (pintype "passive"))
    )
    (net (code "168") (name "IO147") (class "Default")
      (node (ref "IC1") (pin "K22") (pinfunction "IO_147_K22") (pintype "bidirectional"))
      (node (ref "JP119") (pin "1") (pinfunction "1_1") (pintype "passive"))
    )
    (net (code "169") (name "IO148") (class "Default")
      (node (ref "IC1") (pin "L6") (pinfunction "IO_148_L6") (pintype "bidirectional"))
      (node (ref "JP121") (pin "1") (pinfunction "1_1") (pintype "passive"))
    )
    (net (code "170") (name "IO149") (class "Default")
      (node (ref "IC1") (pin "L7") (pinfunction "IO_149_L7") (pintype "bidirectional"))
      (node (ref "JP122") (pin "1") (pinfunction "1_1") (pintype "passive"))
    )
    (net (code "171") (name "IO150") (class "Default")
      (node (ref "IC1") (pin "L8") (pinfunction "IO_150_L8") (pintype "bidirectional"))
      (node (ref "JP124") (pin "1") (pinfunction "1_1") (pintype "passive"))
    )
    (net (code "172") (name "IO151") (class "Default")
      (node (ref "IC1") (pin "L21") (pinfunction "IO_151_L21") (pintype "bidirectional"))
      (node (ref "JP123") (pin "1") (pinfunction "1_1") (pintype "passive"))
    )
    (net (code "173") (name "IO152") (class "Default")
      (node (ref "IC1") (pin "L22") (pinfunction "IO_152_L22") (pintype "bidirectional"))
      (node (ref "JP125") (pin "1") (pinfunction "1_1") (pintype "passive"))
    )
    (net (code "174") (name "IO153") (class "Default")
      (node (ref "IC1") (pin "M1") (pinfunction "IO_153_M1") (pintype "bidirectional"))
      (node (ref "JP126") (pin "1") (pinfunction "1_1") (pintype "passive"))
    )
    (net (code "175") (name "IO154") (class "Default")
      (node (ref "IC1") (pin "M2") (pinfunction "IO_154_M2") (pintype "bidirectional"))
      (node (ref "JP128") (pin "1") (pinfunction "1_1") (pintype "passive"))
    )
    (net (code "176") (name "IO155") (class "Default")
      (node (ref "IC1") (pin "M3") (pinfunction "IO_155_M3") (pintype "bidirectional"))
      (node (ref "JP127") (pin "1") (pinfunction "1_1") (pintype "passive"))
    )
    (net (code "177") (name "IO156") (class "Default")
      (node (ref "IC1") (pin "M4") (pinfunction "IO_156_M4") (pintype "bidirectional"))
      (node (ref "JP129") (pin "1") (pinfunction "1_1") (pintype "passive"))
    )
    (net (code "178") (name "IO157") (class "Default")
      (node (ref "IC1") (pin "M5") (pinfunction "IO_157_M5") (pintype "bidirectional"))
      (node (ref "JP130") (pin "1") (pinfunction "1_1") (pintype "passive"))
    )
    (net (code "179") (name "IO158") (class "Default")
      (node (ref "IC1") (pin "M6") (pinfunction "IO_158_M6") (pintype "bidirectional"))
      (node (ref "JP132") (pin "1") (pinfunction "1_1") (pintype "passive"))
    )
    (net (code "180") (name "IO159") (class "Default")
      (node (ref "IC1") (pin "M7") (pinfunction "IO_159_M7") (pintype "bidirectional"))
      (node (ref "JP131") (pin "1") (pinfunction "1_1") (pintype "passive"))
    )
    (net (code "181") (name "IO160") (class "Default")
      (node (ref "IC1") (pin "M8") (pinfunction "IO_160_M8") (pintype "bidirectional"))
      (node (ref "JP133") (pin "1") (pinfunction "1_1") (pintype "passive"))
    )
    (net (code "182") (name "IO161") (class "Default")
      (node (ref "IC1") (pin "M16") (pinfunction "IO_161_M16") (pintype "bidirectional"))
      (node (ref "JP134") (pin "1") (pinfunction "1_1") (pintype "passive"))
    )
    (net (code "183") (name "IO162") (class "Default")
      (node (ref "IC1") (pin "M19") (pinfunction "IO_162_M19") (pintype "bidirectional"))
      (node (ref "JP136") (pin "1") (pinfunction "1_1") (pintype "passive"))
    )
    (net (code "184") (name "IO163") (class "Default")
      (node (ref "IC1") (pin "M20") (pinfunction "IO_163_M20") (pintype "bidirectional"))
      (node (ref "JP135") (pin "1") (pinfunction "1_1") (pintype "passive"))
    )
    (net (code "185") (name "IO164") (class "Default")
      (node (ref "IC1") (pin "M21") (pinfunction "IO_164_M21") (pintype "bidirectional"))
      (node (ref "JP137") (pin "1") (pinfunction "1_1") (pintype "passive"))
    )
    (net (code "186") (name "IO165") (class "Default")
      (node (ref "IC1") (pin "M22") (pinfunction "IO_165_M22") (pintype "bidirectional"))
      (node (ref "JP194") (pin "1") (pinfunction "1_1") (pintype "passive"))
    )
    (net (code "187") (name "IO166") (class "Default")
      (node (ref "IC1") (pin "N1") (pinfunction "IO_166_N1") (pintype "bidirectional"))
      (node (ref "JP196") (pin "1") (pinfunction "1_1") (pintype "passive"))
    )
    (net (code "188") (name "IO167") (class "Default")
      (node (ref "IC1") (pin "N2") (pinfunction "IO_167_N2") (pintype "bidirectional"))
      (node (ref "JP195") (pin "1") (pinfunction "1_1") (pintype "passive"))
    )
    (net (code "189") (name "IO168") (class "Default")
      (node (ref "IC1") (pin "N5") (pinfunction "IO_168_N5") (pintype "bidirectional"))
      (node (ref "JP197") (pin "1") (pinfunction "1_1") (pintype "passive"))
    )
    (net (code "190") (name "IO169") (class "Default")
      (node (ref "IC1") (pin "N6") (pinfunction "IO_169_N6") (pintype "bidirectional"))
      (node (ref "JP198") (pin "1") (pinfunction "1_1") (pintype "passive"))
    )
    (net (code "191") (name "IO170") (class "Default")
      (node (ref "IC1") (pin "N7") (pinfunction "IO_170_N7") (pintype "bidirectional"))
      (node (ref "JP200") (pin "1") (pinfunction "1_1") (pintype "passive"))
    )
    (net (code "192") (name "IO171") (class "Default")
      (node (ref "IC1") (pin "N8") (pinfunction "IO_171_N8") (pintype "bidirectional"))
      (node (ref "JP199") (pin "1") (pinfunction "1_1") (pintype "passive"))
    )
    (net (code "193") (name "IO172") (class "Default")
      (node (ref "IC1") (pin "N16") (pinfunction "IO_172_N16") (pintype "bidirectional"))
      (node (ref "JP201") (pin "1") (pinfunction "1_1") (pintype "passive"))
    )
    (net (code "194") (name "IO173") (class "Default")
      (node (ref "IC1") (pin "N17") (pinfunction "IO_173_N17") (pintype "bidirectional"))
      (node (ref "JP202") (pin "1") (pinfunction "1_1") (pintype "passive"))
    )
    (net (code "195") (name "IO174") (class "Default")
      (node (ref "IC1") (pin "N18") (pinfunction "IO_174_N18") (pintype "bidirectional"))
      (node (ref "JP204") (pin "1") (pinfunction "1_1") (pintype "passive"))
    )
    (net (code "196") (name "IO175") (class "Default")
      (node (ref "IC1") (pin "N19") (pinfunction "IO_175_N19") (pintype "bidirectional"))
      (node (ref "JP203") (pin "1") (pinfunction "1_1") (pintype "passive"))
    )
    (net (code "197") (name "IO176") (class "Default")
      (node (ref "IC1") (pin "N20") (pinfunction "IO_176_N20") (pintype "bidirectional"))
      (node (ref "JP205") (pin "1") (pinfunction "1_1") (pintype "passive"))
    )
    (net (code "198") (name "IO177") (class "Default")
      (node (ref "IC1") (pin "N21") (pinfunction "IO_177_N21") (pintype "bidirectional"))
      (node (ref "JP206") (pin "1") (pinfunction "1_1") (pintype "passive"))
    )
    (net (code "199") (name "IO178") (class "Default")
      (node (ref "IC1") (pin "N22") (pinfunction "IO_178_N22") (pintype "bidirectional"))
      (node (ref "JP207") (pin "1") (pinfunction "1_1") (pintype "passive"))
    )
    (net (code "200") (name "IO179") (class "Default")
      (node (ref "IC1") (pin "P1") (pinfunction "IO_179_P1") (pintype "bidirectional"))
      (node (ref "JP208") (pin "1") (pinfunction "1_1") (pintype "passive"))
    )
    (net (code "201") (name "IO180") (class "Default")
      (node (ref "IC1") (pin "P2") (pinfunction "IO_180_P2") (pintype "bidirectional"))
      (node (ref "JP210") (pin "1") (pinfunction "1_1") (pintype "passive"))
    )
    (net (code "202") (name "IO181") (class "Default")
      (node (ref "IC1") (pin "P3") (pinfunction "IO_181_P3") (pintype "bidirectional"))
      (node (ref "JP209") (pin "1") (pinfunction "1_1") (pintype "passive"))
    )
    (net (code "203") (name "IO182") (class "Default")
      (node (ref "IC1") (pin "P4") (pinfunction "IO_182_P4") (pintype "bidirectional"))
      (node (ref "JP211") (pin "1") (pinfunction "1_1") (pintype "passive"))
    )
    (net (code "204") (name "IO183") (class "Default")
      (node (ref "IC1") (pin "P5") (pinfunction "IO_183_P5") (pintype "bidirectional"))
      (node (ref "JP212") (pin "1") (pinfunction "1_1") (pintype "passive"))
    )
    (net (code "205") (name "IO184") (class "Default")
      (node (ref "IC1") (pin "P6") (pinfunction "IO_184_P6") (pintype "bidirectional"))
      (node (ref "JP214") (pin "1") (pinfunction "1_1") (pintype "passive"))
    )
    (net (code "206") (name "IO185") (class "Default")
      (node (ref "IC1") (pin "P7") (pinfunction "IO_185_P7") (pintype "bidirectional"))
      (node (ref "JP213") (pin "1") (pinfunction "1_1") (pintype "passive"))
    )
    (net (code "207") (name "IO186") (class "Default")
      (node (ref "IC1") (pin "P15") (pinfunction "IO_186_P15") (pintype "bidirectional"))
      (node (ref "JP215") (pin "1") (pinfunction "1_1") (pintype "passive"))
    )
    (net (code "208") (name "IO187") (class "Default")
      (node (ref "IC1") (pin "P16") (pinfunction "IO_187_P16") (pintype "bidirectional"))
      (node (ref "JP216") (pin "1") (pinfunction "1_1") (pintype "passive"))
    )
    (net (code "209") (name "IO188") (class "Default")
      (node (ref "IC1") (pin "P17") (pinfunction "IO_188_P17") (pintype "bidirectional"))
      (node (ref "JP218") (pin "1") (pinfunction "1_1") (pintype "passive"))
    )
    (net (code "210") (name "IO189") (class "Default")
      (node (ref "IC1") (pin "P20") (pinfunction "IO_189_P20") (pintype "bidirectional"))
      (node (ref "JP217") (pin "1") (pinfunction "1_1") (pintype "passive"))
    )
    (net (code "211") (name "IO190") (class "Default")
      (node (ref "IC1") (pin "P21") (pinfunction "IO_190_P21") (pintype "bidirectional"))
      (node (ref "JP219") (pin "1") (pinfunction "1_1") (pintype "passive"))
    )
    (net (code "212") (name "IO191") (class "Default")
      (node (ref "IC1") (pin "P22") (pinfunction "IO_191_P22") (pintype "bidirectional"))
      (node (ref "JP220") (pin "1") (pinfunction "1_1") (pintype "passive"))
    )
    (net (code "213") (name "IO192") (class "Default")
      (node (ref "IC1") (pin "R1") (pinfunction "IO_192_R1") (pintype "bidirectional"))
      (node (ref "JP221") (pin "1") (pinfunction "1_1") (pintype "passive"))
    )
    (net (code "214") (name "IO193") (class "Default")
      (node (ref "IC1") (pin "R2") (pinfunction "IO_193_R2") (pintype "bidirectional"))
      (node (ref "JP222") (pin "1") (pinfunction "1_1") (pintype "passive"))
    )
    (net (code "215") (name "IO194") (class "Default")
      (node (ref "IC1") (pin "R5") (pinfunction "IO_194_R5") (pintype "bidirectional"))
      (node (ref "JP224") (pin "1") (pinfunction "1_1") (pintype "passive"))
    )
    (net (code "216") (name "IO195") (class "Default")
      (node (ref "IC1") (pin "R6") (pinfunction "IO_195_R6") (pintype "bidirectional"))
      (node (ref "JP223") (pin "1") (pinfunction "1_1") (pintype "passive"))
    )
    (net (code "217") (name "IO196") (class "Default")
      (node (ref "IC1") (pin "R7") (pinfunction "IO_196_R7") (pintype "bidirectional"))
      (node (ref "JP225") (pin "1") (pinfunction "1_1") (pintype "passive"))
    )
    (net (code "218") (name "IO197") (class "Default")
      (node (ref "IC1") (pin "R14") (pinfunction "IO_197_R14") (pintype "bidirectional"))
      (node (ref "JP226") (pin "1") (pinfunction "1_1") (pintype "passive"))
    )
    (net (code "219") (name "IO198") (class "Default")
      (node (ref "IC1") (pin "R15") (pinfunction "IO_198_R15") (pintype "bidirectional"))
      (node (ref "JP228") (pin "1") (pinfunction "1_1") (pintype "passive"))
    )
    (net (code "220") (name "IO199") (class "Default")
      (node (ref "IC1") (pin "R16") (pinfunction "IO_199_R16") (pintype "bidirectional"))
      (node (ref "JP227") (pin "1") (pinfunction "1_1") (pintype "passive"))
    )
    (net (code "221") (name "IO200") (class "Default")
      (node (ref "IC1") (pin "R17") (pinfunction "IO_200_R17") (pintype "bidirectional"))
      (node (ref "JP229") (pin "1") (pinfunction "1_1") (pintype "passive"))
    )
    (net (code "222") (name "IO201") (class "Default")
      (node (ref "IC1") (pin "R18") (pinfunction "IO_201_R18") (pintype "bidirectional"))
      (node (ref "JP230") (pin "1") (pinfunction "1_1") (pintype "passive"))
    )
    (net (code "223") (name "IO202") (class "Default")
      (node (ref "IC1") (pin "R19") (pinfunction "IO_202_R19") (pintype "bidirectional"))
      (node (ref "JP232") (pin "1") (pinfunction "1_1") (pintype "passive"))
    )
    (net (code "224") (name "IO203") (class "Default")
      (node (ref "IC1") (pin "R20") (pinfunction "IO_203_R20") (pintype "bidirectional"))
      (node (ref "JP231") (pin "1") (pinfunction "1_1") (pintype "passive"))
    )
    (net (code "225") (name "IO204") (class "Default")
      (node (ref "IC1") (pin "R21") (pinfunction "IO_204_R21") (pintype "bidirectional"))
      (node (ref "JP233") (pin "1") (pinfunction "1_1") (pintype "passive"))
    )
    (net (code "226") (name "IO205") (class "Default")
      (node (ref "IC1") (pin "R22") (pinfunction "IO_205_R22") (pintype "bidirectional"))
      (node (ref "JP234") (pin "1") (pinfunction "1_1") (pintype "passive"))
    )
    (net (code "227") (name "IO206") (class "Default")
      (node (ref "IC1") (pin "T3") (pinfunction "IO_206_T3") (pintype "bidirectional"))
      (node (ref "JP235") (pin "1") (pinfunction "1_1") (pintype "passive"))
    )
    (net (code "228") (name "IO207") (class "Default")
      (node (ref "IC1") (pin "T4") (pinfunction "IO_207_T4") (pintype "bidirectional"))
      (node (ref "JP236") (pin "1") (pinfunction "1_1") (pintype "passive"))
    )
    (net (code "229") (name "IO208") (class "Default")
      (node (ref "IC1") (pin "T5") (pinfunction "IO_208_T5") (pintype "bidirectional"))
      (node (ref "JP238") (pin "1") (pinfunction "1_1") (pintype "passive"))
    )
    (net (code "230") (name "IO209") (class "Default")
      (node (ref "IC1") (pin "T7") (pinfunction "IO_209_T7") (pintype "bidirectional"))
      (node (ref "JP237") (pin "1") (pinfunction "1_1") (pintype "passive"))
    )
    (net (code "231") (name "IO210") (class "Default")
      (node (ref "IC1") (pin "T8") (pinfunction "IO_210_T8") (pintype "bidirectional"))
      (node (ref "JP239") (pin "1") (pinfunction "1_1") (pintype "passive"))
    )
    (net (code "232") (name "IO211") (class "Default")
      (node (ref "IC1") (pin "T9") (pinfunction "IO_211_T9") (pintype "bidirectional"))
      (node (ref "JP240") (pin "1") (pinfunction "1_1") (pintype "passive"))
    )
    (net (code "233") (name "IO212") (class "Default")
      (node (ref "IC1") (pin "T10") (pinfunction "IO_212_T10") (pintype "bidirectional"))
      (node (ref "JP242") (pin "1") (pinfunction "1_1") (pintype "passive"))
    )
    (net (code "234") (name "IO213") (class "Default")
      (node (ref "IC1") (pin "T11") (pinfunction "IO_213_T11") (pintype "bidirectional"))
      (node (ref "JP241") (pin "1") (pinfunction "1_1") (pintype "passive"))
    )
    (net (code "235") (name "IO214") (class "Default")
      (node (ref "IC1") (pin "T12") (pinfunction "IO_214_T12") (pintype "bidirectional"))
      (node (ref "JP243") (pin "1") (pinfunction "1_1") (pintype "passive"))
    )
    (net (code "236") (name "IO215") (class "Default")
      (node (ref "IC1") (pin "T13") (pinfunction "IO_215_T13") (pintype "bidirectional"))
      (node (ref "JP244") (pin "1") (pinfunction "1_1") (pintype "passive"))
    )
    (net (code "237") (name "IO216") (class "Default")
      (node (ref "IC1") (pin "T14") (pinfunction "IO_216_T14") (pintype "bidirectional"))
      (node (ref "JP246") (pin "1") (pinfunction "1_1") (pintype "passive"))
    )
    (net (code "238") (name "IO217") (class "Default")
      (node (ref "IC1") (pin "T15") (pinfunction "IO_217_T15") (pintype "bidirectional"))
      (node (ref "JP245") (pin "1") (pinfunction "1_1") (pintype "passive"))
    )
    (net (code "239") (name "IO218") (class "Default")
      (node (ref "IC1") (pin "T16") (pinfunction "IO_218_T16") (pintype "bidirectional"))
      (node (ref "JP247") (pin "1") (pinfunction "1_1") (pintype "passive"))
    )
    (net (code "240") (name "IO219") (class "Default")
      (node (ref "IC1") (pin "T17") (pinfunction "IO_219_T17") (pintype "bidirectional"))
      (node (ref "JP248") (pin "1") (pinfunction "1_1") (pintype "passive"))
    )
    (net (code "241") (name "IO220") (class "Default")
      (node (ref "IC1") (pin "T18") (pinfunction "IO_220_T18") (pintype "bidirectional"))
      (node (ref "JP249") (pin "1") (pinfunction "1_1") (pintype "passive"))
    )
    (net (code "242") (name "IO221") (class "Default")
      (node (ref "IC1") (pin "U1") (pinfunction "IO_221_U1") (pintype "bidirectional"))
      (node (ref "JP250") (pin "1") (pinfunction "1_1") (pintype "passive"))
    )
    (net (code "243") (name "IO222") (class "Default")
      (node (ref "IC1") (pin "U2") (pinfunction "IO_222_U2") (pintype "bidirectional"))
      (node (ref "JP252") (pin "1") (pinfunction "1_1") (pintype "passive"))
    )
    (net (code "244") (name "IO223") (class "Default")
      (node (ref "IC1") (pin "U7") (pinfunction "IO_223_U7") (pintype "bidirectional"))
      (node (ref "JP251") (pin "1") (pinfunction "1_1") (pintype "passive"))
    )
    (net (code "245") (name "IO224") (class "Default")
      (node (ref "IC1") (pin "U8") (pinfunction "IO_224_U8") (pintype "bidirectional"))
      (node (ref "JP253") (pin "1") (pinfunction "1_1") (pintype "passive"))
    )
    (net (code "246") (name "IO225") (class "Default")
      (node (ref "IC1") (pin "U9") (pinfunction "IO_225_U9") (pintype "bidirectional"))
      (node (ref "JP254") (pin "1") (pinfunction "1_1") (pintype "passive"))
    )
    (net (code "247") (name "IO226") (class "Default")
      (node (ref "IC1") (pin "U10") (pinfunction "IO_226_U10") (pintype "bidirectional"))
      (node (ref "JP256") (pin "1") (pinfunction "1_1") (pintype "passive"))
    )
    (net (code "248") (name "IO227") (class "Default")
      (node (ref "IC1") (pin "U11") (pinfunction "IO_227_U11") (pintype "bidirectional"))
      (node (ref "JP255") (pin "1") (pinfunction "1_1") (pintype "passive"))
    )
    (net (code "249") (name "IO228") (class "Default")
      (node (ref "IC1") (pin "U12") (pinfunction "IO_228_U12") (pintype "bidirectional"))
      (node (ref "JP257") (pin "1") (pinfunction "1_1") (pintype "passive"))
    )
    (net (code "250") (name "IO229") (class "Default")
      (node (ref "IC1") (pin "U13") (pinfunction "IO_229_U13") (pintype "bidirectional"))
      (node (ref "JP258") (pin "1") (pinfunction "1_1") (pintype "passive"))
    )
    (net (code "251") (name "IO230") (class "Default")
      (node (ref "IC1") (pin "U14") (pinfunction "IO_230_U14") (pintype "bidirectional"))
      (node (ref "JP260") (pin "1") (pinfunction "1_1") (pintype "passive"))
    )
    (net (code "252") (name "IO231") (class "Default")
      (node (ref "IC1") (pin "U15") (pinfunction "IO_231_U15") (pintype "bidirectional"))
      (node (ref "JP259") (pin "1") (pinfunction "1_1") (pintype "passive"))
    )
    (net (code "253") (name "IO232") (class "Default")
      (node (ref "IC1") (pin "U16") (pinfunction "IO_232_U16") (pintype "bidirectional"))
      (node (ref "JP261") (pin "1") (pinfunction "1_1") (pintype "passive"))
    )
    (net (code "254") (name "IO233") (class "Default")
      (node (ref "IC1") (pin "U17") (pinfunction "IO_233_U17") (pintype "bidirectional"))
      (node (ref "JP262") (pin "1") (pinfunction "1_1") (pintype "passive"))
    )
    (net (code "255") (name "IO234") (class "Default")
      (node (ref "IC1") (pin "U19") (pinfunction "IO_234_U19") (pintype "bidirectional"))
      (node (ref "JP263") (pin "1") (pinfunction "1_1") (pintype "passive"))
    )
    (net (code "256") (name "IO235") (class "Default")
      (node (ref "IC1") (pin "U20") (pinfunction "IO_235_U20") (pintype "bidirectional"))
      (node (ref "JP264") (pin "1") (pinfunction "1_1") (pintype "passive"))
    )
    (net (code "257") (name "IO236") (class "Default")
      (node (ref "IC1") (pin "U21") (pinfunction "IO_236_U21") (pintype "bidirectional"))
      (node (ref "JP266") (pin "1") (pinfunction "1_1") (pintype "passive"))
    )
    (net (code "258") (name "IO237") (class "Default")
      (node (ref "IC1") (pin "U22") (pinfunction "IO_237_U22") (pintype "bidirectional"))
      (node (ref "JP265") (pin "1") (pinfunction "1_1") (pintype "passive"))
    )
    (net (code "259") (name "IO238") (class "Default")
      (node (ref "IC1") (pin "V1") (pinfunction "IO_238_V1") (pintype "bidirectional"))
      (node (ref "JP267") (pin "1") (pinfunction "1_1") (pintype "passive"))
    )
    (net (code "260") (name "IO239") (class "Default")
      (node (ref "IC1") (pin "V2") (pinfunction "IO_239_V2") (pintype "bidirectional"))
      (node (ref "JP268") (pin "1") (pinfunction "1_1") (pintype "passive"))
    )
    (net (code "261") (name "IO240") (class "Default")
      (node (ref "IC1") (pin "V3") (pinfunction "IO_240_V3") (pintype "bidirectional"))
      (node (ref "JP270") (pin "1") (pinfunction "1_1") (pintype "passive"))
    )
    (net (code "262") (name "IO241") (class "Default")
      (node (ref "IC1") (pin "V4") (pinfunction "IO_241_V4") (pintype "bidirectional"))
      (node (ref "JP269") (pin "1") (pinfunction "1_1") (pintype "passive"))
    )
    (net (code "263") (name "IO242") (class "Default")
      (node (ref "IC1") (pin "V5") (pinfunction "IO_242_V5") (pintype "bidirectional"))
      (node (ref "JP271") (pin "1") (pinfunction "1_1") (pintype "passive"))
    )
    (net (code "264") (name "IO243") (class "Default")
      (node (ref "IC1") (pin "V6") (pinfunction "IO_243_V6") (pintype "bidirectional"))
      (node (ref "JP272") (pin "1") (pinfunction "1_1") (pintype "passive"))
    )
    (net (code "265") (name "IO244") (class "Default")
      (node (ref "IC1") (pin "V7") (pinfunction "IO_244_V7") (pintype "bidirectional"))
      (node (ref "JP274") (pin "1") (pinfunction "1_1") (pintype "passive"))
    )
    (net (code "266") (name "IO245") (class "Default")
      (node (ref "IC1") (pin "V8") (pinfunction "IO_245_V8") (pintype "bidirectional"))
      (node (ref "JP273") (pin "1") (pinfunction "1_1") (pintype "passive"))
    )
    (net (code "267") (name "IO246") (class "Default")
      (node (ref "IC1") (pin "V9") (pinfunction "IO_246_V9") (pintype "bidirectional"))
      (node (ref "JP275") (pin "1") (pinfunction "1_1") (pintype "passive"))
    )
    (net (code "268") (name "IO247") (class "Default")
      (node (ref "IC1") (pin "V10") (pinfunction "IO_247_V10") (pintype "bidirectional"))
      (node (ref "JP276") (pin "1") (pinfunction "1_1") (pintype "passive"))
    )
    (net (code "269") (name "IO248") (class "Default")
      (node (ref "IC1") (pin "V11") (pinfunction "IO_248_V11") (pintype "bidirectional"))
      (node (ref "JP277") (pin "1") (pinfunction "1_1") (pintype "passive"))
    )
    (net (code "270") (name "IO249") (class "Default")
      (node (ref "IC1") (pin "V12") (pinfunction "IO_249_V12") (pintype "bidirectional"))
      (node (ref "JP278") (pin "1") (pinfunction "1_1") (pintype "passive"))
    )
    (net (code "271") (name "IO250") (class "Default")
      (node (ref "IC1") (pin "V13") (pinfunction "IO_250_V13") (pintype "bidirectional"))
      (node (ref "JP280") (pin "1") (pinfunction "1_1") (pintype "passive"))
    )
    (net (code "272") (name "IO251") (class "Default")
      (node (ref "IC1") (pin "V14") (pinfunction "IO_251_V14") (pintype "bidirectional"))
      (node (ref "JP279") (pin "1") (pinfunction "1_1") (pintype "passive"))
    )
    (net (code "273") (name "IO252") (class "Default")
      (node (ref "IC1") (pin "V15") (pinfunction "IO_252_V15") (pintype "bidirectional"))
      (node (ref "JP281") (pin "1") (pinfunction "1_1") (pintype "passive"))
    )
    (net (code "274") (name "IO253") (class "Default")
      (node (ref "IC1") (pin "V16") (pinfunction "IO_253_V16") (pintype "bidirectional"))
      (node (ref "JP282") (pin "1") (pinfunction "1_1") (pintype "passive"))
    )
    (net (code "275") (name "IO254") (class "Default")
      (node (ref "IC1") (pin "V21") (pinfunction "IO_254_V21") (pintype "bidirectional"))
      (node (ref "JP284") (pin "1") (pinfunction "1_1") (pintype "passive"))
    )
    (net (code "276") (name "IO255") (class "Default")
      (node (ref "IC1") (pin "V22") (pinfunction "IO_255_V22") (pintype "bidirectional"))
      (node (ref "JP283") (pin "1") (pinfunction "1_1") (pintype "passive"))
    )
    (net (code "277") (name "IO256") (class "Default")
      (node (ref "IC1") (pin "W1") (pinfunction "IO_256_W1") (pintype "bidirectional"))
      (node (ref "JP285") (pin "1") (pinfunction "1_1") (pintype "passive"))
    )
    (net (code "278") (name "IO257") (class "Default")
      (node (ref "IC1") (pin "W2") (pinfunction "IO_257_W2") (pintype "bidirectional"))
      (node (ref "JP286") (pin "1") (pinfunction "1_1") (pintype "passive"))
    )
    (net (code "279") (name "IO258") (class "Default")
      (node (ref "IC1") (pin "W6") (pinfunction "IO_258_W6") (pintype "bidirectional"))
      (node (ref "JP288") (pin "1") (pinfunction "1_1") (pintype "passive"))
    )
    (net (code "280") (name "IO259") (class "Default")
      (node (ref "IC1") (pin "W7") (pinfunction "IO_259_W7") (pintype "bidirectional"))
      (node (ref "JP287") (pin "1") (pinfunction "1_1") (pintype "passive"))
    )
    (net (code "281") (name "IO260") (class "Default")
      (node (ref "IC1") (pin "W8") (pinfunction "IO_260_W8") (pintype "bidirectional"))
      (node (ref "JP289") (pin "1") (pinfunction "1_1") (pintype "passive"))
    )
    (net (code "282") (name "IO261") (class "Default")
      (node (ref "IC1") (pin "W10") (pinfunction "IO_261_W10") (pintype "bidirectional"))
      (node (ref "JP290") (pin "1") (pinfunction "1_1") (pintype "passive"))
    )
    (net (code "283") (name "IO262") (class "Default")
      (node (ref "IC1") (pin "W13") (pinfunction "IO_262_W13") (pintype "bidirectional"))
      (node (ref "JP291") (pin "1") (pinfunction "1_1") (pintype "passive"))
    )
    (net (code "284") (name "IO263") (class "Default")
      (node (ref "IC1") (pin "W14") (pinfunction "IO_263_W14") (pintype "bidirectional"))
      (node (ref "JP292") (pin "1") (pinfunction "1_1") (pintype "passive"))
    )
    (net (code "285") (name "IO264") (class "Default")
      (node (ref "IC1") (pin "W15") (pinfunction "IO_264_W15") (pintype "bidirectional"))
      (node (ref "JP294") (pin "1") (pinfunction "1_1") (pintype "passive"))
    )
    (net (code "286") (name "IO265") (class "Default")
      (node (ref "IC1") (pin "W17") (pinfunction "IO_265_W17") (pintype "bidirectional"))
      (node (ref "JP293") (pin "1") (pinfunction "1_1") (pintype "passive"))
    )
    (net (code "287") (name "IO266") (class "Default")
      (node (ref "IC1") (pin "W19") (pinfunction "IO_266_W19") (pintype "bidirectional"))
      (node (ref "JP295") (pin "1") (pinfunction "1_1") (pintype "passive"))
    )
    (net (code "288") (name "IO267") (class "Default")
      (node (ref "IC1") (pin "W20") (pinfunction "IO_267_W20") (pintype "bidirectional"))
      (node (ref "JP296") (pin "1") (pinfunction "1_1") (pintype "passive"))
    )
    (net (code "289") (name "IO268") (class "Default")
      (node (ref "IC1") (pin "W21") (pinfunction "IO_268_W21") (pintype "bidirectional"))
      (node (ref "JP298") (pin "1") (pinfunction "1_1") (pintype "passive"))
    )
    (net (code "290") (name "IO269") (class "Default")
      (node (ref "IC1") (pin "W22") (pinfunction "IO_269_W22") (pintype "bidirectional"))
      (node (ref "JP297") (pin "1") (pinfunction "1_1") (pintype "passive"))
    )
    (net (code "291") (name "IO270") (class "Default")
      (node (ref "IC1") (pin "Y1") (pinfunction "IO_270_Y1") (pintype "bidirectional"))
      (node (ref "JP299") (pin "1") (pinfunction "1_1") (pintype "passive"))
    )
    (net (code "292") (name "IO271") (class "Default")
      (node (ref "IC1") (pin "Y2") (pinfunction "IO_271_Y2") (pintype "bidirectional"))
      (node (ref "JP300") (pin "1") (pinfunction "1_1") (pintype "passive"))
    )
    (net (code "293") (name "IO272") (class "Default")
      (node (ref "IC1") (pin "Y3") (pinfunction "IO_272_Y3") (pintype "bidirectional"))
      (node (ref "JP302") (pin "1") (pinfunction "1_1") (pintype "passive"))
    )
    (net (code "294") (name "IO273") (class "Default")
      (node (ref "IC1") (pin "Y4") (pinfunction "IO_273_Y4") (pintype "bidirectional"))
      (node (ref "JP301") (pin "1") (pinfunction "1_1") (pintype "passive"))
    )
    (net (code "295") (name "IO274") (class "Default")
      (node (ref "IC1") (pin "Y6") (pinfunction "IO_274_Y6") (pintype "bidirectional"))
      (node (ref "JP303") (pin "1") (pinfunction "1_1") (pintype "passive"))
    )
    (net (code "296") (name "IO275") (class "Default")
      (node (ref "IC1") (pin "Y7") (pinfunction "IO_275_Y7") (pintype "bidirectional"))
      (node (ref "JP304") (pin "1") (pinfunction "1_1") (pintype "passive"))
    )
    (net (code "297") (name "IO276") (class "Default")
      (node (ref "IC1") (pin "Y8") (pinfunction "IO_276_Y8") (pintype "bidirectional"))
      (node (ref "JP305") (pin "1") (pinfunction "1_1") (pintype "passive"))
    )
    (net (code "298") (name "IO277") (class "Default")
      (node (ref "IC1") (pin "Y10") (pinfunction "IO_277_Y10") (pintype "bidirectional"))
      (node (ref "JP306") (pin "1") (pinfunction "1_1") (pintype "passive"))
    )
    (net (code "299") (name "IO278") (class "Default")
      (node (ref "IC1") (pin "Y13") (pinfunction "IO_278_Y13") (pintype "bidirectional"))
      (node (ref "JP308") (pin "1") (pinfunction "1_1") (pintype "passive"))
    )
    (net (code "300") (name "IO279") (class "Default")
      (node (ref "IC1") (pin "Y17") (pinfunction "IO_279_Y17") (pintype "bidirectional"))
      (node (ref "JP307") (pin "1") (pinfunction "1_1") (pintype "passive"))
    )
    (net (code "301") (name "IO280") (class "Default")
      (node (ref "IC1") (pin "Y21") (pinfunction "IO_280_Y21") (pintype "bidirectional"))
      (node (ref "JP309") (pin "1") (pinfunction "1_1") (pintype "passive"))
    )
    (net (code "302") (name "IO281") (class "Default")
      (node (ref "IC1") (pin "Y22") (pinfunction "IO_281_Y22") (pintype "bidirectional"))
      (node (ref "JP310") (pin "1") (pinfunction "1_1") (pintype "passive"))
    )
    (net (code "303") (name "IO282") (class "Default")
      (node (ref "IC1") (pin "AA1") (pinfunction "IO_282_AA1") (pintype "bidirectional"))
      (node (ref "JP312") (pin "1") (pinfunction "1_1") (pintype "passive"))
    )
    (net (code "304") (name "IO283") (class "Default")
      (node (ref "IC1") (pin "AA3") (pinfunction "IO_283_AA3") (pintype "bidirectional"))
      (node (ref "JP311") (pin "1") (pinfunction "1_1") (pintype "passive"))
    )
    (net (code "305") (name "IO284") (class "Default")
      (node (ref "IC1") (pin "AA4") (pinfunction "IO_284_AA4") (pintype "bidirectional"))
      (node (ref "JP313") (pin "1") (pinfunction "1_1") (pintype "passive"))
    )
    (net (code "306") (name "IO285") (class "Default")
      (node (ref "IC1") (pin "AA5") (pinfunction "IO_285_AA5") (pintype "bidirectional"))
      (node (ref "JP314") (pin "1") (pinfunction "1_1") (pintype "passive"))
    )
    (net (code "307") (name "IO286") (class "Default")
      (node (ref "IC1") (pin "AA7") (pinfunction "IO_286_AA7") (pintype "bidirectional"))
      (node (ref "JP316") (pin "1") (pinfunction "1_1") (pintype "passive"))
    )
    (net (code "308") (name "IO287") (class "Default")
      (node (ref "IC1") (pin "AA8") (pinfunction "IO_287_AA8") (pintype "bidirectional"))
      (node (ref "JP315") (pin "1") (pinfunction "1_1") (pintype "passive"))
    )
    (net (code "309") (name "IO288") (class "Default")
      (node (ref "IC1") (pin "AA9") (pinfunction "IO_288_AA9") (pintype "bidirectional"))
      (node (ref "JP317") (pin "1") (pinfunction "1_1") (pintype "passive"))
    )
    (net (code "310") (name "IO289") (class "Default")
      (node (ref "IC1") (pin "AA10") (pinfunction "IO_289_AA10") (pintype "bidirectional"))
      (node (ref "JP318") (pin "1") (pinfunction "1_1") (pintype "passive"))
    )
    (net (code "311") (name "IO290") (class "Default")
      (node (ref "IC1") (pin "AA13") (pinfunction "IO_290_AA13") (pintype "bidirectional"))
      (node (ref "JP319") (pin "1") (pinfunction "1_1") (pintype "passive"))
    )
    (net (code "312") (name "IO291") (class "Default")
      (node (ref "IC1") (pin "AA14") (pinfunction "IO_291_AA14") (pintype "bidirectional"))
      (node (ref "JP320") (pin "1") (pinfunction "1_1") (pintype "passive"))
    )
    (net (code "313") (name "IO292") (class "Default")
      (node (ref "IC1") (pin "AA15") (pinfunction "IO_292_AA15") (pintype "bidirectional"))
      (node (ref "JP322") (pin "1") (pinfunction "1_1") (pintype "passive"))
    )
    (net (code "314") (name "IO293") (class "Default")
      (node (ref "IC1") (pin "AA16") (pinfunction "IO_293_AA16") (pintype "bidirectional"))
      (node (ref "JP321") (pin "1") (pinfunction "1_1") (pintype "passive"))
    )
    (net (code "315") (name "IO294") (class "Default")
      (node (ref "IC1") (pin "AA17") (pinfunction "IO_294_AA17") (pintype "bidirectional"))
      (node (ref "JP323") (pin "1") (pinfunction "1_1") (pintype "passive"))
    )
    (net (code "316") (name "IO295") (class "Default")
      (node (ref "IC1") (pin "AA18") (pinfunction "IO_295_AA18") (pintype "bidirectional"))
      (node (ref "JP324") (pin "1") (pinfunction "1_1") (pintype "passive"))
    )
    (net (code "317") (name "IO296") (class "Default")
      (node (ref "IC1") (pin "AA19") (pinfunction "IO_296_AA19") (pintype "bidirectional"))
      (node (ref "JP326") (pin "1") (pinfunction "1_1") (pintype "passive"))
    )
    (net (code "318") (name "IO297") (class "Default")
      (node (ref "IC1") (pin "AA20") (pinfunction "IO_297_AA20") (pintype "bidirectional"))
      (node (ref "JP325") (pin "1") (pinfunction "1_1") (pintype "passive"))
    )
    (net (code "319") (name "IO298") (class "Default")
      (node (ref "IC1") (pin "AA21") (pinfunction "IO_298_AA21") (pintype "bidirectional"))
      (node (ref "JP327") (pin "1") (pinfunction "1_1") (pintype "passive"))
    )
    (net (code "320") (name "IO299") (class "Default")
      (node (ref "IC1") (pin "AB3") (pinfunction "IO_299_AB3") (pintype "bidirectional"))
      (node (ref "JP328") (pin "1") (pinfunction "1_1") (pintype "passive"))
    )
    (net (code "321") (name "IO300") (class "Default")
      (node (ref "IC1") (pin "AB4") (pinfunction "IO_300_AB4") (pintype "bidirectional"))
      (node (ref "JP330") (pin "1") (pinfunction "1_1") (pintype "passive"))
    )
    (net (code "322") (name "IO301") (class "Default")
      (node (ref "IC1") (pin "AB5") (pinfunction "IO_301_AB5") (pintype "bidirectional"))
      (node (ref "JP329") (pin "1") (pinfunction "1_1") (pintype "passive"))
    )
    (net (code "323") (name "IO302") (class "Default")
      (node (ref "IC1") (pin "AB7") (pinfunction "IO_302_AB7") (pintype "bidirectional"))
      (node (ref "JP331") (pin "1") (pinfunction "1_1") (pintype "passive"))
    )
    (net (code "324") (name "IO303") (class "Default")
      (node (ref "IC1") (pin "AB8") (pinfunction "IO_303_AB8") (pintype "bidirectional"))
      (node (ref "JP332") (pin "1") (pinfunction "1_1") (pintype "passive"))
    )
    (net (code "325") (name "IO304") (class "Default")
      (node (ref "IC1") (pin "AB9") (pinfunction "IO_304_AB9") (pintype "bidirectional"))
      (node (ref "JP333") (pin "1") (pinfunction "1_1") (pintype "passive"))
    )
    (net (code "326") (name "IO305") (class "Default")
      (node (ref "IC1") (pin "AB10") (pinfunction "IO_305_AB10") (pintype "bidirectional"))
      (node (ref "JP334") (pin "1") (pinfunction "1_1") (pintype "passive"))
    )
    (net (code "327") (name "IO306") (class "Default")
      (node (ref "IC1") (pin "AB13") (pinfunction "IO_306_AB13") (pintype "bidirectional"))
      (node (ref "JP336") (pin "1") (pinfunction "1_1") (pintype "passive"))
    )
    (net (code "328") (name "IO307") (class "Default")
      (node (ref "IC1") (pin "AB14") (pinfunction "IO_307_AB14") (pintype "bidirectional"))
      (node (ref "JP335") (pin "1") (pinfunction "1_1") (pintype "passive"))
    )
    (net (code "329") (name "IO308") (class "Default")
      (node (ref "IC1") (pin "AB15") (pinfunction "IO_308_AB15") (pintype "bidirectional"))
      (node (ref "JP337") (pin "1") (pinfunction "1_1") (pintype "passive"))
    )
    (net (code "330") (name "IO309") (class "Default")
      (node (ref "IC1") (pin "AB16") (pinfunction "IO_309_AB16") (pintype "bidirectional"))
      (node (ref "JP338") (pin "1") (pinfunction "1_1") (pintype "passive"))
    )
    (net (code "331") (name "IO310") (class "Default")
      (node (ref "IC1") (pin "AB17") (pinfunction "IO_310_AB17") (pintype "bidirectional"))
      (node (ref "JP340") (pin "1") (pinfunction "1_1") (pintype "passive"))
    )
    (net (code "332") (name "IO311") (class "Default")
      (node (ref "IC1") (pin "AB18") (pinfunction "IO_311_AB18") (pintype "bidirectional"))
      (node (ref "JP339") (pin "1") (pinfunction "1_1") (pintype "passive"))
    )
    (net (code "333") (name "IO312") (class "Default")
      (node (ref "IC1") (pin "AB19") (pinfunction "IO_312_AB19") (pintype "bidirectional"))
      (node (ref "JP341") (pin "1") (pinfunction "1_1") (pintype "passive"))
    )
    (net (code "334") (name "IO313") (class "Default")
      (node (ref "IC1") (pin "AB20") (pinfunction "IO_313_AB20") (pintype "bidirectional"))
      (node (ref "JP342") (pin "1") (pinfunction "1_1") (pintype "passive"))
    )
    (net (code "335") (name "MSEL0") (class "Default")
      (node (ref "IC1") (pin "M17") (pinfunction "MSEL0_M17") (pintype "bidirectional"))
      (node (ref "R6") (pin "P$1") (pinfunction "P$1_P$1") (pintype "bidirectional"))
    )
    (net (code "336") (name "MSEL1") (class "Default")
      (node (ref "IC1") (pin "L18") (pinfunction "MSEL1_L18") (pintype "bidirectional"))
      (node (ref "R7") (pin "P$1") (pinfunction "P$1_P$1") (pintype "bidirectional"))
    )
    (net (code "337") (name "MSEL2") (class "Default")
      (node (ref "IC1") (pin "L17") (pinfunction "MSEL2_L17") (pintype "bidirectional"))
      (node (ref "R8") (pin "P$1") (pinfunction "P$1_P$1") (pintype "bidirectional"))
    )
    (net (code "338") (name "MSEL3") (class "Default")
      (node (ref "IC1") (pin "K20") (pinfunction "MSEL3_K20") (pintype "bidirectional"))
      (node (ref "R9") (pin "P$1") (pinfunction "P$1_P$1") (pintype "bidirectional"))
    )
    (net (code "339") (name "NCE") (class "Default")
      (node (ref "IC1") (pin "L3") (pinfunction "NCE_L3") (pintype "bidirectional"))
      (node (ref "R4") (pin "P$1") (pinfunction "P$1_P$1") (pintype "bidirectional"))
    )
    (net (code "340") (name "NCONFIG") (class "Default")
      (node (ref "IC1") (pin "K5") (pinfunction "NCONFIG_K5") (pintype "bidirectional"))
      (node (ref "R2") (pin "P$1") (pinfunction "P$1_P$1") (pintype "bidirectional"))
      (node (ref "SW1") (pin "2") (pinfunction "A1_2") (pintype "bidirectional"))
    )
    (net (code "341") (name "NCSO") (class "Default")
      (node (ref "IC1") (pin "E2") (pinfunction "IO_65_E2") (pintype "bidirectional"))
      (node (ref "IC2") (pin "1") (pinfunction "NCS_1") (pintype "bidirectional"))
      (node (ref "JP54") (pin "1") (pinfunction "1_1") (pintype "passive"))
    )
    (net (code "342") (name "NSTATUS") (class "Default")
      (node (ref "IC1") (pin "K6") (pinfunction "NSTATUS_K6") (pintype "bidirectional"))
      (node (ref "R5") (pin "P$1") (pinfunction "P$1_P$1") (pintype "bidirectional"))
    )
    (net (code "343") (name "Net-(LED33-PadA)") (class "Default")
      (node (ref "LED33") (pin "A") (pinfunction "A_A") (pintype "passive"))
      (node (ref "R45") (pin "P$2") (pinfunction "P$2_P$2") (pintype "bidirectional"))
    )
    (net (code "344") (name "Net-(LED34-PadA)") (class "Default")
      (node (ref "LED34") (pin "A") (pinfunction "A_A") (pintype "passive"))
      (node (ref "R44") (pin "P$2") (pinfunction "P$2_P$2") (pintype "bidirectional"))
    )
    (net (code "345") (name "Net-(LED35-PadA)") (class "Default")
      (node (ref "LED35") (pin "A") (pinfunction "A_A") (pintype "passive"))
      (node (ref "R43") (pin "P$2") (pinfunction "P$2_P$2") (pintype "bidirectional"))
    )
    (net (code "346") (name "Net-(LED36-PadA)") (class "Default")
      (node (ref "LED36") (pin "A") (pinfunction "A_A") (pintype "passive"))
      (node (ref "R42") (pin "P$2") (pinfunction "P$2_P$2") (pintype "bidirectional"))
    )
    (net (code "347") (name "Net-(LED37-PadA)") (class "Default")
      (node (ref "LED37") (pin "A") (pinfunction "A_A") (pintype "passive"))
      (node (ref "R41") (pin "P$2") (pinfunction "P$2_P$2") (pintype "bidirectional"))
    )
    (net (code "348") (name "Net-(LED38-PadA)") (class "Default")
      (node (ref "LED38") (pin "A") (pinfunction "A_A") (pintype "passive"))
      (node (ref "R40") (pin "P$2") (pinfunction "P$2_P$2") (pintype "bidirectional"))
    )
    (net (code "349") (name "Net-(LED39-PadA)") (class "Default")
      (node (ref "LED39") (pin "A") (pinfunction "A_A") (pintype "passive"))
      (node (ref "R39") (pin "P$2") (pinfunction "P$2_P$2") (pintype "bidirectional"))
    )
    (net (code "350") (name "Net-(LED40-PadA)") (class "Default")
      (node (ref "LED40") (pin "A") (pinfunction "A_A") (pintype "passive"))
      (node (ref "R38") (pin "P$2") (pinfunction "P$2_P$2") (pintype "bidirectional"))
    )
    (net (code "351") (name "TCK") (class "Default")
      (node (ref "IC1") (pin "L2") (pinfunction "TCK_L2") (pintype "bidirectional"))
      (node (ref "J1") (pin "1") (pinfunction "1_1") (pintype "passive"))
    )
    (net (code "352") (name "TDI") (class "Default")
      (node (ref "IC1") (pin "L5") (pinfunction "TDI_L5") (pintype "bidirectional"))
      (node (ref "J1") (pin "9") (pinfunction "9_9") (pintype "passive"))
    )
    (net (code "353") (name "TDO") (class "Default")
      (node (ref "IC1") (pin "L4") (pinfunction "TDO_L4") (pintype "bidirectional"))
      (node (ref "J1") (pin "3") (pinfunction "3_3") (pintype "passive"))
    )
    (net (code "354") (name "TMS") (class "Default")
      (node (ref "IC1") (pin "L1") (pinfunction "TMS_L1") (pintype "bidirectional"))
      (node (ref "J1") (pin "5") (pinfunction "5_5") (pintype "passive"))
    )
    (net (code "355") (name "VCCA") (class "Default")
      (node (ref "C26") (pin "2") (pinfunction "2_2") (pintype "passive"))
      (node (ref "IC1") (pin "F18") (pinfunction "VCCA2_F18") (pintype "bidirectional"))
      (node (ref "IC1") (pin "G6") (pinfunction "VCCA3_G6") (pintype "bidirectional"))
      (node (ref "IC1") (pin "T6") (pinfunction "VCCA1_T6") (pintype "bidirectional"))
      (node (ref "IC1") (pin "U18") (pinfunction "VCCA4_U18") (pintype "bidirectional"))
      (node (ref "R20") (pin "P$2") (pinfunction "P$2_P$2") (pintype "bidirectional"))
    )
    (net (code "356") (name "VCCINT") (class "Default")
      (node (ref "C24") (pin "2") (pinfunction "2_2") (pintype "passive"))
      (node (ref "IC1") (pin "G12") (pinfunction "VCCINT_1_G12") (pintype "bidirectional"))
      (node (ref "IC1") (pin "H9") (pinfunction "VCCINT_2_H9") (pintype "bidirectional"))
      (node (ref "IC1") (pin "J10") (pinfunction "VCCINT_3_J10") (pintype "bidirectional"))
      (node (ref "IC1") (pin "J11") (pinfunction "VCCINT_4_J11") (pintype "bidirectional"))
      (node (ref "IC1") (pin "J12") (pinfunction "VCCINT_5_J12") (pintype "bidirectional"))
      (node (ref "IC1") (pin "J13") (pinfunction "VCCINT_6_J13") (pintype "bidirectional"))
      (node (ref "IC1") (pin "J14") (pinfunction "VCCINT_7_J14") (pintype "bidirectional"))
      (node (ref "IC1") (pin "J16") (pinfunction "VCCINT_8_J16") (pintype "bidirectional"))
      (node (ref "IC1") (pin "K14") (pinfunction "VCCINT_10_K14") (pintype "bidirectional"))
      (node (ref "IC1") (pin "K15") (pinfunction "VCCINT_11_K15") (pintype "bidirectional"))
      (node (ref "IC1") (pin "K9") (pinfunction "VCCINT_9_K9") (pintype "bidirectional"))
      (node (ref "IC1") (pin "L14") (pinfunction "VCCINT_13_L14") (pintype "bidirectional"))
      (node (ref "IC1") (pin "L16") (pinfunction "VCCINT_14_L16") (pintype "bidirectional"))
      (node (ref "IC1") (pin "L9") (pinfunction "VCCINT_12_L9") (pintype "bidirectional"))
      (node (ref "IC1") (pin "M14") (pinfunction "VCCINT_16_M14") (pintype "bidirectional"))
      (node (ref "IC1") (pin "M15") (pinfunction "VCCINT_17_M15") (pintype "bidirectional"))
      (node (ref "IC1") (pin "M9") (pinfunction "VCCINT_15_M9") (pintype "bidirectional"))
      (node (ref "IC1") (pin "N14") (pinfunction "VCCINT_19_N14") (pintype "bidirectional"))
      (node (ref "IC1") (pin "N9") (pinfunction "VCCINT_18_N9") (pintype "bidirectional"))
      (node (ref "IC1") (pin "P10") (pinfunction "VCCINT_21_P10") (pintype "bidirectional"))
      (node (ref "IC1") (pin "P11") (pinfunction "VCCINT_22_P11") (pintype "bidirectional"))
      (node (ref "IC1") (pin "P12") (pinfunction "VCCINT_23_P12") (pintype "bidirectional"))
      (node (ref "IC1") (pin "P13") (pinfunction "VCCINT_24_P13") (pintype "bidirectional"))
      (node (ref "IC1") (pin "P14") (pinfunction "VCCINT_25_P14") (pintype "bidirectional"))
      (node (ref "IC1") (pin "P9") (pinfunction "VCCINT_20_P9") (pintype "bidirectional"))
      (node (ref "IC1") (pin "R10") (pinfunction "VCCINT_27_R10") (pintype "bidirectional"))
      (node (ref "IC1") (pin "R12") (pinfunction "VCCINT_28_R12") (pintype "bidirectional"))
      (node (ref "IC1") (pin "R8") (pinfunction "VCCINT_26_R8") (pintype "bidirectional"))
      (node (ref "R18") (pin "P$2") (pinfunction "P$2_P$2") (pintype "bidirectional"))
    )
    (net (code "357") (name "VCCIO") (class "Default")
      (node (ref "C16") (pin "2") (pinfunction "2_2") (pintype "passive"))
      (node (ref "C17") (pin "2") (pinfunction "2_2") (pintype "passive"))
      (node (ref "C18") (pin "2") (pinfunction "2_2") (pintype "passive"))
      (node (ref "C19") (pin "2") (pinfunction "2_2") (pintype "passive"))
      (node (ref "C20") (pin "2") (pinfunction "2_2") (pintype "passive"))
      (node (ref "C21") (pin "2") (pinfunction "2_2") (pintype "passive"))
      (node (ref "C22") (pin "2") (pinfunction "2_2") (pintype "passive"))
      (node (ref "C23") (pin "2") (pinfunction "2_2") (pintype "passive"))
      (node (ref "IC1") (pin "A2") (pinfunction "VCCIO8_1_A2") (pintype "bidirectional"))
      (node (ref "IC1") (pin "A21") (pinfunction "VCCIO7_1_A21") (pintype "bidirectional"))
      (node (ref "IC1") (pin "AA6") (pinfunction "VCCIO3_4_AA6") (pintype "bidirectional"))
      (node (ref "IC1") (pin "AB2") (pinfunction "VCCIO3_5_AB2") (pintype "bidirectional"))
      (node (ref "IC1") (pin "AB21") (pinfunction "VCCIO4_5_AB21") (pintype "bidirectional"))
      (node (ref "IC1") (pin "D11") (pinfunction "VCCIO8_4_D11") (pintype "bidirectional"))
      (node (ref "IC1") (pin "D12") (pinfunction "VCCIO7_2_D12") (pintype "bidirectional"))
      (node (ref "IC1") (pin "D14") (pinfunction "VCCIO7_3_D14") (pintype "bidirectional"))
      (node (ref "IC1") (pin "D16") (pinfunction "VCCIO7_4_D16") (pintype "bidirectional"))
      (node (ref "IC1") (pin "D18") (pinfunction "VCCIO7_5_D18") (pintype "bidirectional"))
      (node (ref "IC1") (pin "D4") (pinfunction "VCCIO1_1_D4") (pintype "bidirectional"))
      (node (ref "IC1") (pin "D5") (pinfunction "VCCIO8_2_D5") (pintype "bidirectional"))
      (node (ref "IC1") (pin "D9") (pinfunction "VCCIO8_3_D9") (pintype "bidirectional"))
      (node (ref "IC1") (pin "E19") (pinfunction "VCCIO6_1_E19") (pintype "bidirectional"))
      (node (ref "IC1") (pin "E8") (pinfunction "VCCIO8_5_E8") (pintype "bidirectional"))
      (node (ref "IC1") (pin "F4") (pinfunction "VCCIO1_2_F4") (pintype "bidirectional"))
      (node (ref "IC1") (pin "G19") (pinfunction "VCCIO6_2_G19") (pintype "bidirectional"))
      (node (ref "IC1") (pin "H4") (pinfunction "VCCIO1_3_H4") (pintype "bidirectional"))
      (node (ref "IC1") (pin "J20") (pinfunction "VCCIO6_3_J20") (pintype "bidirectional"))
      (node (ref "IC1") (pin "K4") (pinfunction "VCCIO1_4_K4") (pintype "bidirectional"))
      (node (ref "IC1") (pin "L19") (pinfunction "VCCIO6_4_L19") (pintype "bidirectional"))
      (node (ref "IC1") (pin "N4") (pinfunction "VCCIO2_1_N4") (pintype "bidirectional"))
      (node (ref "IC1") (pin "P18") (pinfunction "VCCIO5_1_P18") (pintype "bidirectional"))
      (node (ref "IC1") (pin "R4") (pinfunction "VCCIO2_2_R4") (pintype "bidirectional"))
      (node (ref "IC1") (pin "T19") (pinfunction "VCCIO5_2_T19") (pintype "bidirectional"))
      (node (ref "IC1") (pin "U4") (pinfunction "VCCIO2_3_U4") (pintype "bidirectional"))
      (node (ref "IC1") (pin "V19") (pinfunction "VCCIO5_3_V19") (pintype "bidirectional"))
      (node (ref "IC1") (pin "W11") (pinfunction "VCCIO3_3_W11") (pintype "bidirectional"))
      (node (ref "IC1") (pin "W12") (pinfunction "VCCIO4_1_W12") (pintype "bidirectional"))
      (node (ref "IC1") (pin "W16") (pinfunction "VCCIO4_2_W16") (pintype "bidirectional"))
      (node (ref "IC1") (pin "W18") (pinfunction "VCCIO4_3_W18") (pintype "bidirectional"))
      (node (ref "IC1") (pin "W4") (pinfunction "VCCIO2_4_W4") (pintype "bidirectional"))
      (node (ref "IC1") (pin "W5") (pinfunction "VCCIO3_1_W5") (pintype "bidirectional"))
      (node (ref "IC1") (pin "W9") (pinfunction "VCCIO3_2_W9") (pintype "bidirectional"))
      (node (ref "IC1") (pin "Y14") (pinfunction "VCCIO4_4_Y14") (pintype "bidirectional"))
      (node (ref "IC1") (pin "Y19") (pinfunction "VCCIO5_4_Y19") (pintype "bidirectional"))
      (node (ref "R17") (pin "P$2") (pinfunction "P$2_P$2") (pintype "bidirectional"))
    )
    (net (code "358") (name "VCCPLL") (class "Default")
      (node (ref "C25") (pin "2") (pinfunction "2_2") (pintype "passive"))
      (node (ref "IC1") (pin "E17") (pinfunction "VCCD_PLL2_E17") (pintype "bidirectional"))
      (node (ref "IC1") (pin "F6") (pinfunction "VCCD_PLL3_F6") (pintype "bidirectional"))
      (node (ref "IC1") (pin "U6") (pinfunction "VCCD_PLL1_U6") (pintype "bidirectional"))
      (node (ref "IC1") (pin "V17") (pinfunction "VCCD_PLL4_V17") (pintype "bidirectional"))
      (node (ref "R19") (pin "P$2") (pinfunction "P$2_P$2") (pintype "bidirectional"))
    )
    (net (code "359") (name "unconnected-(J1-Pad6)") (class "Default")
      (node (ref "J1") (pin "6") (pinfunction "6_6") (pintype "passive"))
    )
    (net (code "360") (name "unconnected-(J1-Pad7)") (class "Default")
      (node (ref "J1") (pin "7") (pinfunction "7_7") (pintype "passive"))
    )
    (net (code "361") (name "unconnected-(J1-Pad8)") (class "Default")
      (node (ref "J1") (pin "8") (pinfunction "8_8") (pintype "passive"))
    )
    (net (code "362") (name "unconnected-(SW1-A0-Pad1)") (class "Default")
      (node (ref "SW1") (pin "1") (pinfunction "A0_1") (pintype "bidirectional"))
    )
    (net (code "363") (name "unconnected-(SW1-B0-Pad3)") (class "Default")
      (node (ref "SW1") (pin "3") (pinfunction "B0_3") (pintype "bidirectional"))
    )
    (net (code "364") (name "unconnected-(SW2-A0-Pad1)") (class "Default")
      (node (ref "SW2") (pin "1") (pinfunction "A0_1") (pintype "bidirectional"))
    )
    (net (code "365") (name "unconnected-(SW2-B0-Pad3)") (class "Default")
      (node (ref "SW2") (pin "3") (pinfunction "B0_3") (pintype "bidirectional"))
    )
    (net (code "366") (name "unconnected-(Y1-EN-Pad1)") (class "Default")
      (node (ref "Y1") (pin "1") (pinfunction "EN_1") (pintype "bidirectional"))
    )
  )
)
